# fmcboard_v1_7.net
KiCad netlist of a schematic drawn in EAGLE
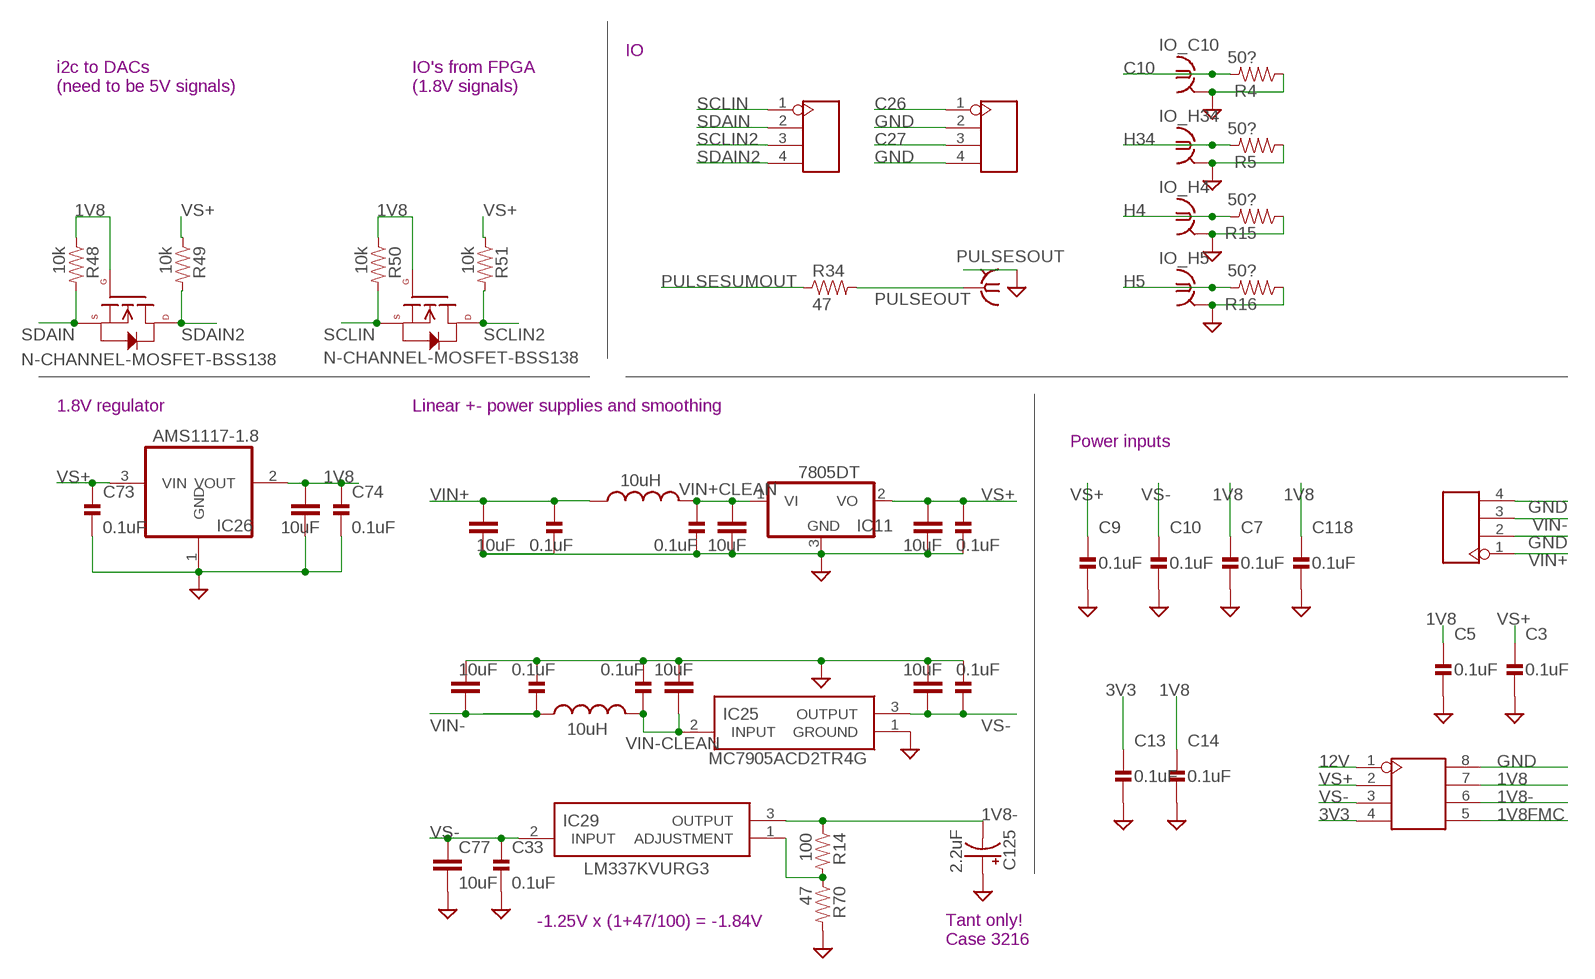
[diagram p0: schematic, sheet 1]
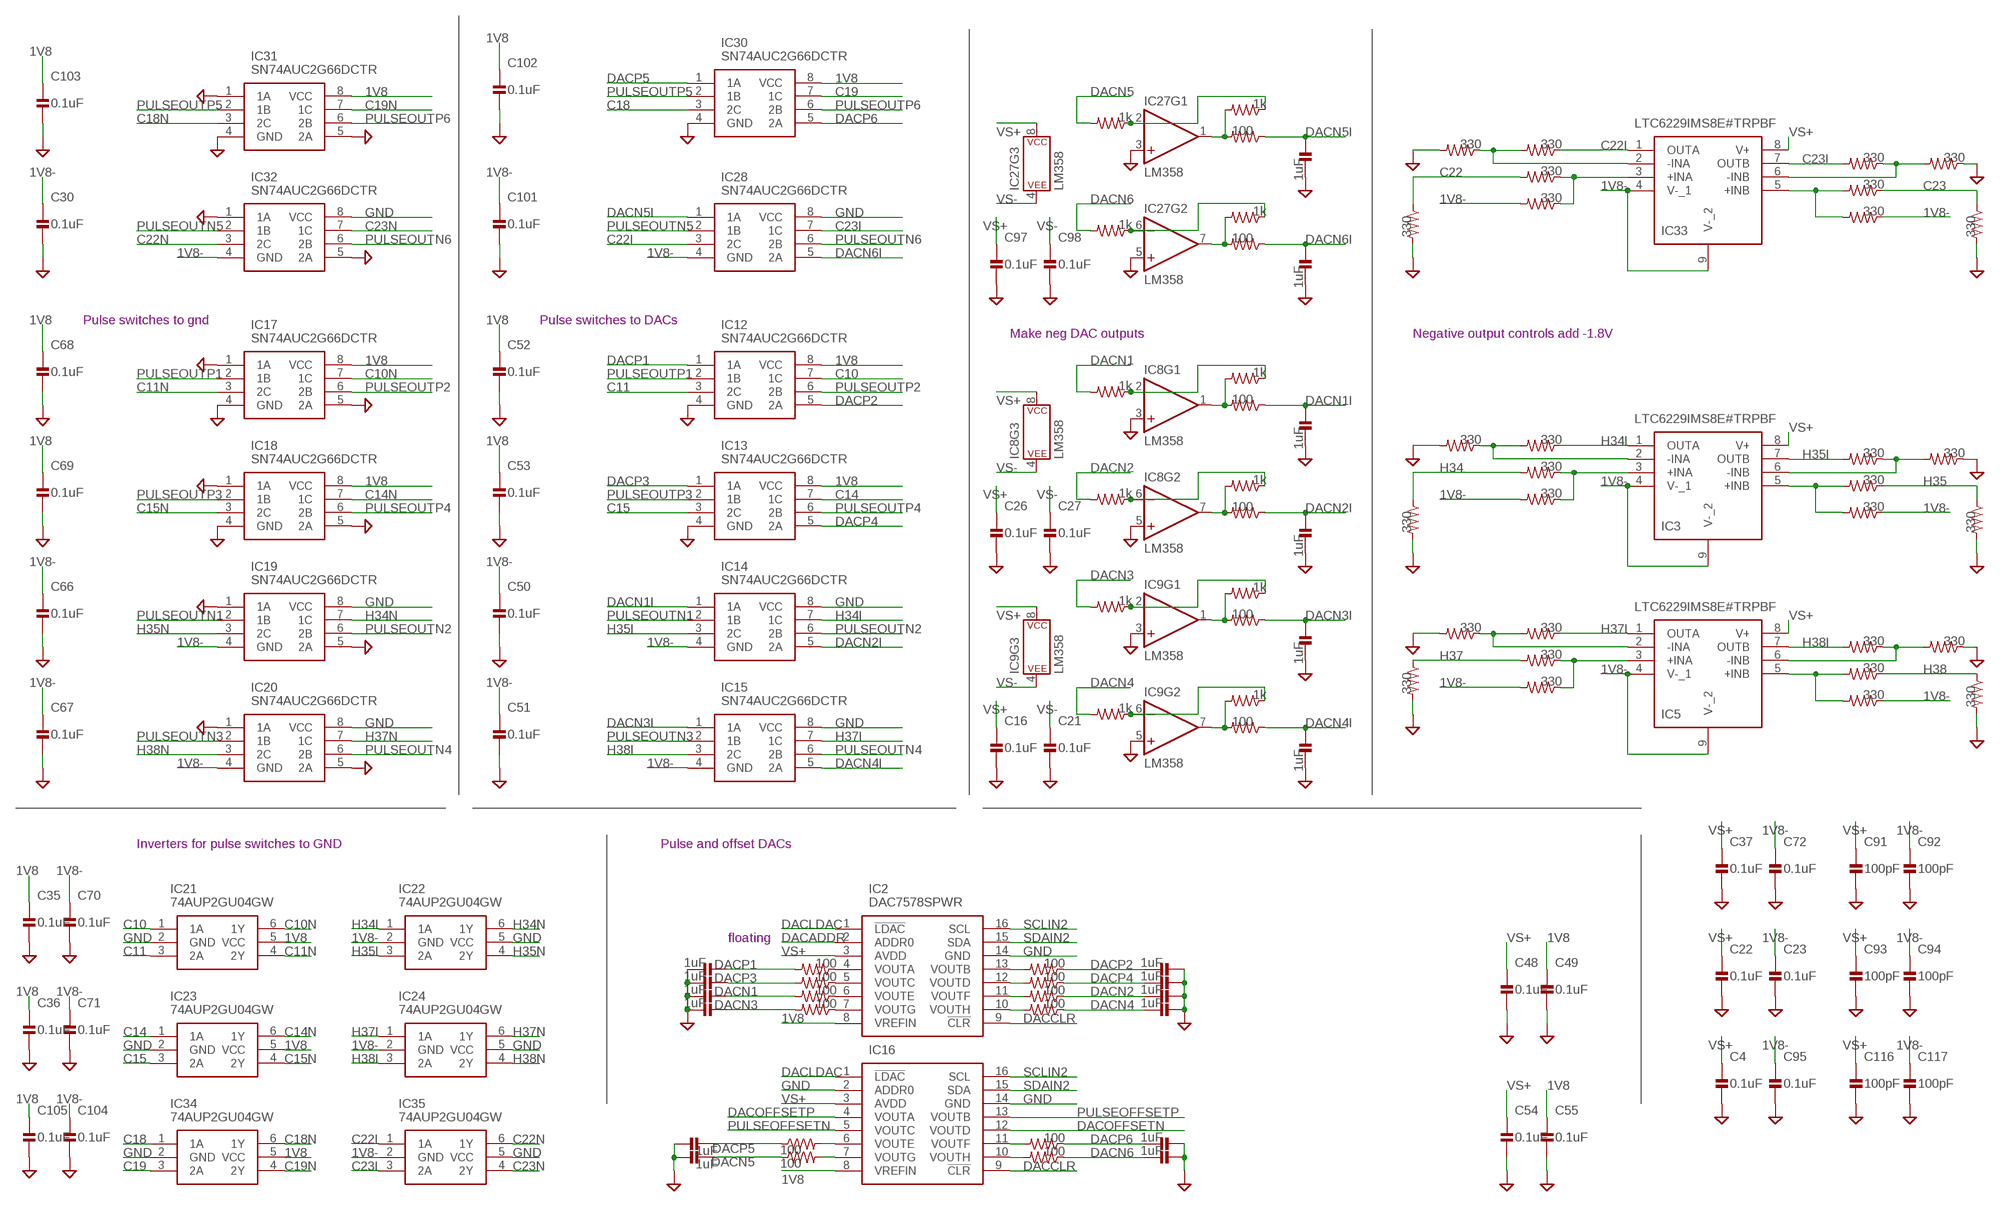
[diagram p1: schematic, sheet 2]
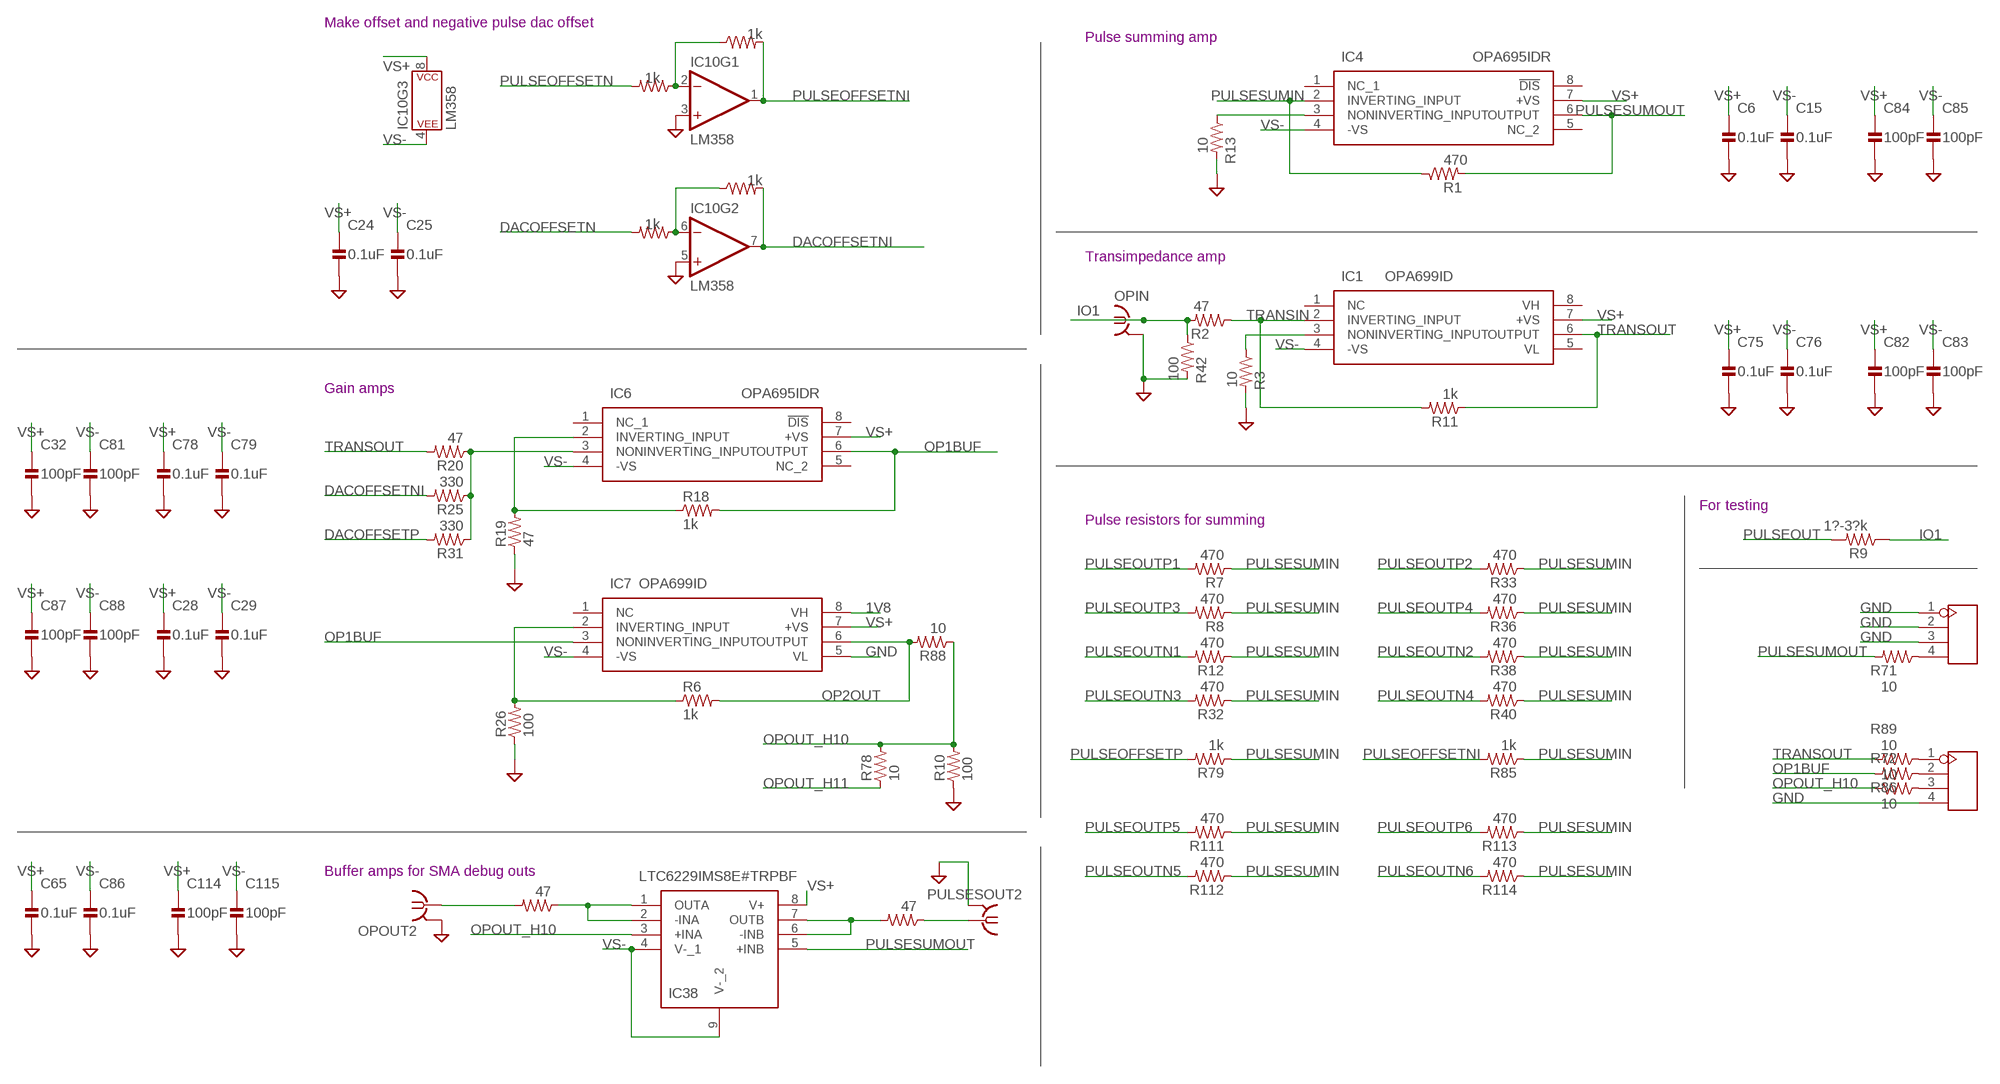
[diagram p2: schematic, sheet 3]
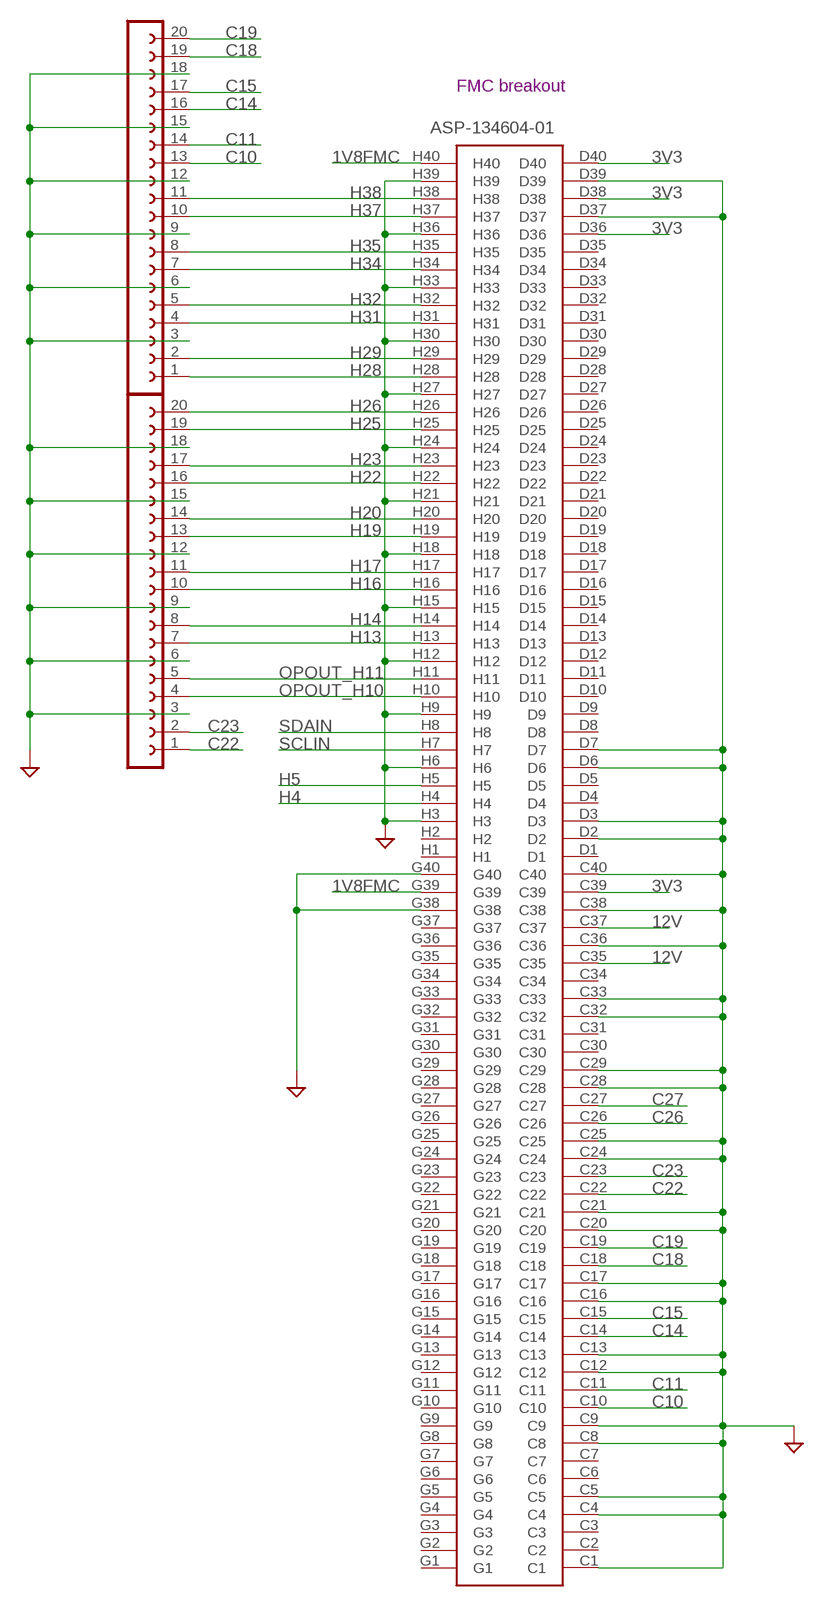
[diagram p3: schematic, sheet 4]
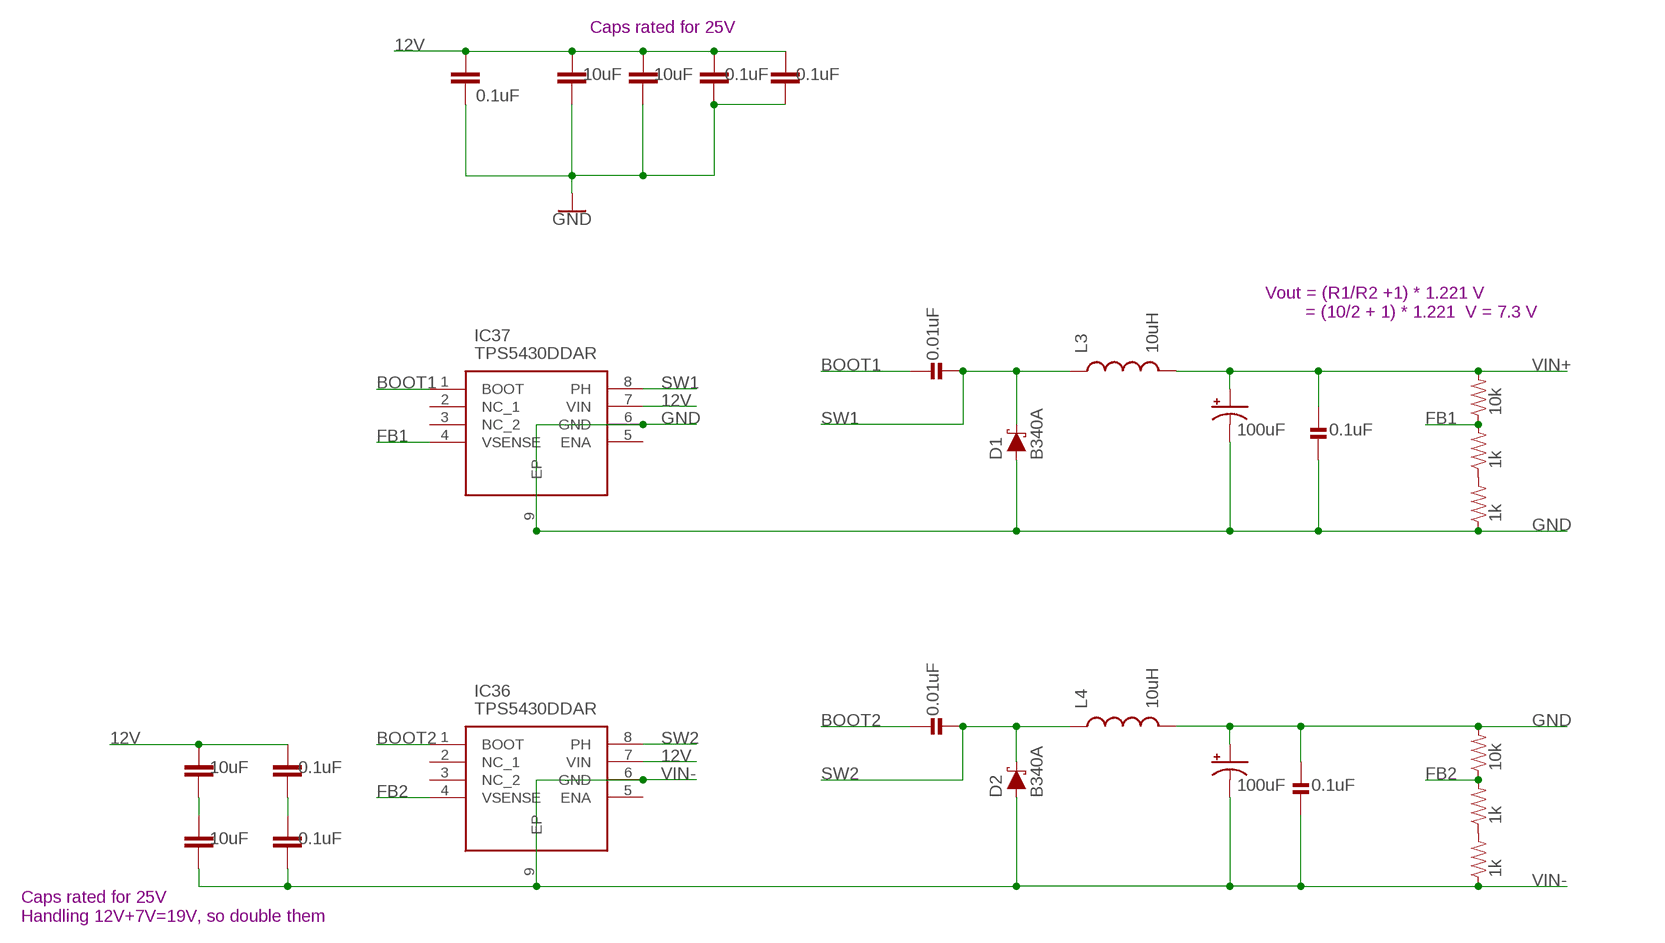
[diagram p4: schematic, sheet 5]

(export (version "E")
  (design (tool "Eeschema 10.0.6"))
  (components
    (comp (ref "J2")
      (value "ASP-134604-01")
      (footprint "eagle-import:ASP13460401")
      (fields (field (name "MOUSER_PART_NUMBER") "200-ASP-134604-01"))
      (libsource (lib "eagle-import") (part "ASP-134604-01"))
    )
    (comp (ref "SV1")
      (value "20")
      (footprint "eagle-import:FE20")
      (libsource (lib "eagle-import") (part "FE20-1"))
    )
    (comp (ref "SV2")
      (value "20")
      (footprint "eagle-import:FE20")
      (libsource (lib "eagle-import") (part "FE20-1"))
    )
    (comp (ref "C6")
      (value "0.1uF")
      (footprint "eagle-import:0402_CAP")
      (libsource (lib "eagle-import") (part "CAPACITOR0402_CAP"))
    )
    (comp (ref "C15")
      (value "0.1uF")
      (footprint "eagle-import:0402_CAP")
      (libsource (lib "eagle-import") (part "CAPACITOR0402_CAP"))
    )
    (comp (ref "C24")
      (value "0.1uF")
      (footprint "eagle-import:0402_CAP")
      (libsource (lib "eagle-import") (part "CAPACITOR0402_CAP"))
    )
    (comp (ref "C25")
      (value "0.1uF")
      (footprint "eagle-import:0402_CAP")
      (libsource (lib "eagle-import") (part "CAPACITOR0402_CAP"))
    )
    (comp (ref "C28")
      (value "0.1uF")
      (footprint "eagle-import:0402_CAP")
      (libsource (lib "eagle-import") (part "CAPACITOR0402_CAP"))
    )
    (comp (ref "C29")
      (value "0.1uF")
      (footprint "eagle-import:0402_CAP")
      (libsource (lib "eagle-import") (part "CAPACITOR0402_CAP"))
    )
    (comp (ref "C32")
      (value "100pF")
      (footprint "eagle-import:0402_CAP")
      (libsource (lib "eagle-import") (part "CAPACITOR0402_CAP"))
    )
    (comp (ref "C65")
      (value "0.1uF")
      (footprint "eagle-import:0402_CAP")
      (libsource (lib "eagle-import") (part "CAPACITOR0402_CAP"))
    )
    (comp (ref "C75")
      (value "0.1uF")
      (footprint "eagle-import:0402_CAP")
      (libsource (lib "eagle-import") (part "CAPACITOR0402_CAP"))
    )
    (comp (ref "C76")
      (value "0.1uF")
      (footprint "eagle-import:0402_CAP")
      (libsource (lib "eagle-import") (part "CAPACITOR0402_CAP"))
    )
    (comp (ref "C78")
      (value "0.1uF")
      (footprint "eagle-import:0402_CAP")
      (libsource (lib "eagle-import") (part "CAPACITOR0402_CAP"))
    )
    (comp (ref "C79")
      (value "0.1uF")
      (footprint "eagle-import:0402_CAP")
      (libsource (lib "eagle-import") (part "CAPACITOR0402_CAP"))
    )
    (comp (ref "C81")
      (value "100pF")
      (footprint "eagle-import:0402_CAP")
      (libsource (lib "eagle-import") (part "CAPACITOR0402_CAP"))
    )
    (comp (ref "C82")
      (value "100pF")
      (footprint "eagle-import:0402_CAP")
      (libsource (lib "eagle-import") (part "CAPACITOR0402_CAP"))
    )
    (comp (ref "C83")
      (value "100pF")
      (footprint "eagle-import:0402_CAP")
      (libsource (lib "eagle-import") (part "CAPACITOR0402_CAP"))
    )
    (comp (ref "C84")
      (value "100pF")
      (footprint "eagle-import:0402_CAP")
      (libsource (lib "eagle-import") (part "CAPACITOR0402_CAP"))
    )
    (comp (ref "C85")
      (value "100pF")
      (footprint "eagle-import:0402_CAP")
      (libsource (lib "eagle-import") (part "CAPACITOR0402_CAP"))
    )
    (comp (ref "C86")
      (value "0.1uF")
      (footprint "eagle-import:0402_CAP")
      (libsource (lib "eagle-import") (part "CAPACITOR0402_CAP"))
    )
    (comp (ref "C87")
      (value "100pF")
      (footprint "eagle-import:0402_CAP")
      (libsource (lib "eagle-import") (part "CAPACITOR0402_CAP"))
    )
    (comp (ref "C88")
      (value "100pF")
      (footprint "eagle-import:0402_CAP")
      (libsource (lib "eagle-import") (part "CAPACITOR0402_CAP"))
    )
    (comp (ref "C114")
      (value "100pF")
      (footprint "eagle-import:0402_CAP")
      (libsource (lib "eagle-import") (part "CAPACITOR0402_CAP"))
    )
    (comp (ref "C115")
      (value "100pF")
      (footprint "eagle-import:0402_CAP")
      (libsource (lib "eagle-import") (part "CAPACITOR0402_CAP"))
    )
    (comp (ref "IC1")
      (value "OPA699ID")
      (footprint "eagle-import:SOIC127P600X175-8N")
      (fields (field (name "MOUSER_PART_NUMBER") "595-OPA699ID"))
      (libsource (lib "eagle-import") (part "OPA699ID"))
    )
    (comp (ref "IC4")
      (value "OPA695IDR")
      (footprint "eagle-import:SOIC127P600X175-8N")
      (fields (field (name "MOUSER_PART_NUMBER") "595-OPA695IDR"))
      (libsource (lib "eagle-import") (part "OPA695IDR"))
    )
    (comp (ref "IC6")
      (value "OPA695IDR")
      (footprint "eagle-import:SOIC127P600X175-8N")
      (fields (field (name "MOUSER_PART_NUMBER") "595-OPA695IDR"))
      (libsource (lib "eagle-import") (part "OPA695IDR"))
    )
    (comp (ref "IC7")
      (value "OPA699ID")
      (footprint "eagle-import:SOIC127P600X175-8N")
      (fields (field (name "MOUSER_PART_NUMBER") "595-OPA699ID"))
      (libsource (lib "eagle-import") (part "OPA699ID"))
    )
    (comp (ref "IC10")
      (value "LM358")
      (footprint "eagle-import:SO08")
      (libsource (lib "eagle-import") (part "OPAMP-DUALU"))
    )
    (comp (ref "IC38")
      (value "LTC6229IMS8E#TRPBF")
      (footprint "eagle-import:SOP65P490X110-9N")
      (fields (field (name "MOUSER_PART_NUMBER") "584-LTC6229IMS8E#TR"))
      (libsource (lib "eagle-import") (part "LTC6229IMS8E#TRPBF"))
    )
    (comp (ref "J5")
      (value "4p-2.54")
      (footprint "eagle-import:H4-2.54")
      (fields (field (name "MPN") "F185-1104A1BSYA1"))
      (libsource (lib "eagle-import") (part "DIP-BLACK-FEMALE-HEADER-VERT(4P-2.54)"))
    )
    (comp (ref "J13")
      (value "4p-2.54")
      (footprint "eagle-import:H4-2.54")
      (fields (field (name "MPN") "F185-1104A1BSYA1"))
      (libsource (lib "eagle-import") (part "DIP-BLACK-FEMALE-HEADER-VERT(4P-2.54)"))
    )
    (comp (ref "OPIN")
      (value "BU-SMB-V")
      (footprint "eagle-import:BU-SMB-V")
      (libsource (lib "eagle-import") (part "BU-SMB-V"))
    )
    (comp (ref "OPOUT2")
      (value "BU-SMB-V")
      (footprint "eagle-import:BU-SMB-V")
      (libsource (lib "eagle-import") (part "BU-SMB-V"))
    )
    (comp (ref "PULSESOUT2")
      (value "BU-SMB-V")
      (footprint "eagle-import:BU-SMB-V")
      (libsource (lib "eagle-import") (part "BU-SMB-V"))
    )
    (comp (ref "R1")
      (value "470")
      (footprint "eagle-import:0402_RES")
      (libsource (lib "eagle-import") (part "RESISTOR0402_RES"))
    )
    (comp (ref "R2")
      (value "47")
      (footprint "eagle-import:0402_RES")
      (libsource (lib "eagle-import") (part "RESISTOR0402_RES"))
    )
    (comp (ref "R3")
      (value "10")
      (footprint "eagle-import:0402_RES")
      (libsource (lib "eagle-import") (part "RESISTOR0402_RES"))
    )
    (comp (ref "R6")
      (value "1k")
      (footprint "eagle-import:0402_RES")
      (libsource (lib "eagle-import") (part "RESISTOR0402_RES"))
    )
    (comp (ref "R7")
      (value "470")
      (footprint "eagle-import:0402_RES")
      (libsource (lib "eagle-import") (part "RESISTOR0402_RES"))
    )
    (comp (ref "R8")
      (value "470")
      (footprint "eagle-import:0402_RES")
      (libsource (lib "eagle-import") (part "RESISTOR0402_RES"))
    )
    (comp (ref "R9")
      (value "1?-3?k")
      (footprint "eagle-import:R0805")
      (libsource (lib "eagle-import") (part "R-US_R0805"))
    )
    (comp (ref "R10")
      (value "100")
      (footprint "eagle-import:0402_RES")
      (libsource (lib "eagle-import") (part "RESISTOR0402_RES"))
    )
    (comp (ref "R11")
      (value "1k")
      (footprint "eagle-import:0402_RES")
      (libsource (lib "eagle-import") (part "RESISTOR0402_RES"))
    )
    (comp (ref "R12")
      (value "470")
      (footprint "eagle-import:0402_RES")
      (libsource (lib "eagle-import") (part "RESISTOR0402_RES"))
    )
    (comp (ref "R13")
      (value "10")
      (footprint "eagle-import:0402_RES")
      (libsource (lib "eagle-import") (part "RESISTOR0402_RES"))
    )
    (comp (ref "R17")
      (value "1k")
      (footprint "eagle-import:0402_RES")
      (libsource (lib "eagle-import") (part "RESISTOR0402_RES"))
    )
    (comp (ref "R18")
      (value "1k")
      (footprint "eagle-import:0402_RES")
      (libsource (lib "eagle-import") (part "RESISTOR0402_RES"))
    )
    (comp (ref "R19")
      (value "47")
      (footprint "eagle-import:0402_RES")
      (libsource (lib "eagle-import") (part "RESISTOR0402_RES"))
    )
    (comp (ref "R20")
      (value "47")
      (footprint "eagle-import:0402_RES")
      (libsource (lib "eagle-import") (part "RESISTOR0402_RES"))
    )
    (comp (ref "R25")
      (value "330")
      (footprint "eagle-import:0402_RES")
      (libsource (lib "eagle-import") (part "RESISTOR0402_RES"))
    )
    (comp (ref "R26")
      (value "100")
      (footprint "eagle-import:0402_RES")
      (libsource (lib "eagle-import") (part "RESISTOR0402_RES"))
    )
    (comp (ref "R31")
      (value "330")
      (footprint "eagle-import:0402_RES")
      (libsource (lib "eagle-import") (part "RESISTOR0402_RES"))
    )
    (comp (ref "R32")
      (value "470")
      (footprint "eagle-import:0402_RES")
      (libsource (lib "eagle-import") (part "RESISTOR0402_RES"))
    )
    (comp (ref "R33")
      (value "470")
      (footprint "eagle-import:0402_RES")
      (libsource (lib "eagle-import") (part "RESISTOR0402_RES"))
    )
    (comp (ref "R35")
      (value "1k")
      (footprint "eagle-import:0402_RES")
      (libsource (lib "eagle-import") (part "RESISTOR0402_RES"))
    )
    (comp (ref "R36")
      (value "470")
      (footprint "eagle-import:0402_RES")
      (libsource (lib "eagle-import") (part "RESISTOR0402_RES"))
    )
    (comp (ref "R38")
      (value "470")
      (footprint "eagle-import:0402_RES")
      (libsource (lib "eagle-import") (part "RESISTOR0402_RES"))
    )
    (comp (ref "R40")
      (value "470")
      (footprint "eagle-import:0402_RES")
      (libsource (lib "eagle-import") (part "RESISTOR0402_RES"))
    )
    (comp (ref "R42")
      (value "100")
      (footprint "eagle-import:0402_RES")
      (libsource (lib "eagle-import") (part "RESISTOR0402_RES"))
    )
    (comp (ref "R61")
      (value "1k")
      (footprint "eagle-import:0402_RES")
      (libsource (lib "eagle-import") (part "RESISTOR0402_RES"))
    )
    (comp (ref "R71")
      (value "10")
      (footprint "eagle-import:0402_RES")
      (libsource (lib "eagle-import") (part "RESISTOR0402_RES"))
    )
    (comp (ref "R72")
      (value "10")
      (footprint "eagle-import:0402_RES")
      (libsource (lib "eagle-import") (part "RESISTOR0402_RES"))
    )
    (comp (ref "R78")
      (value "10")
      (footprint "eagle-import:0402_RES")
      (libsource (lib "eagle-import") (part "RESISTOR0402_RES"))
    )
    (comp (ref "R79")
      (value "1k")
      (footprint "eagle-import:0402_RES")
      (libsource (lib "eagle-import") (part "RESISTOR0402_RES"))
    )
    (comp (ref "R85")
      (value "1k")
      (footprint "eagle-import:0402_RES")
      (libsource (lib "eagle-import") (part "RESISTOR0402_RES"))
    )
    (comp (ref "R86")
      (value "10")
      (footprint "eagle-import:0402_RES")
      (libsource (lib "eagle-import") (part "RESISTOR0402_RES"))
    )
    (comp (ref "R88")
      (value "10")
      (footprint "eagle-import:0402_RES")
      (libsource (lib "eagle-import") (part "RESISTOR0402_RES"))
    )
    (comp (ref "R89")
      (value "10")
      (footprint "eagle-import:0402_RES")
      (libsource (lib "eagle-import") (part "RESISTOR0402_RES"))
    )
    (comp (ref "R111")
      (value "470")
      (footprint "eagle-import:0402_RES")
      (libsource (lib "eagle-import") (part "RESISTOR0402_RES"))
    )
    (comp (ref "R112")
      (value "470")
      (footprint "eagle-import:0402_RES")
      (libsource (lib "eagle-import") (part "RESISTOR0402_RES"))
    )
    (comp (ref "R113")
      (value "470")
      (footprint "eagle-import:0402_RES")
      (libsource (lib "eagle-import") (part "RESISTOR0402_RES"))
    )
    (comp (ref "R114")
      (value "470")
      (footprint "eagle-import:0402_RES")
      (libsource (lib "eagle-import") (part "RESISTOR0402_RES"))
    )
    (comp (ref "R115")
      (value "1k")
      (footprint "eagle-import:0402_RES")
      (libsource (lib "eagle-import") (part "RESISTOR0402_RES"))
    )
    (comp (ref "R119")
      (value "47")
      (footprint "eagle-import:0402_RES")
      (libsource (lib "eagle-import") (part "RESISTOR0402_RES"))
    )
    (comp (ref "R120")
      (value "47")
      (footprint "eagle-import:0402_RES")
      (libsource (lib "eagle-import") (part "RESISTOR0402_RES"))
    )
    (comp (ref "C2")
      (value "100uF")
      (footprint "eagle-import:VISHAY_C")
      (libsource (lib "eagle-import") (part "SparkFun-Passives_CAP_POLSMD"))
    )
    (comp (ref "C8")
      (value "0.1uF")
      (footprint "eagle-import:C0805K")
      (libsource (lib "eagle-import") (part "C-EUC0805K"))
    )
    (comp (ref "C11")
      (value "0.1uF")
      (footprint "eagle-import:C0805K")
      (libsource (lib "eagle-import") (part "C-EUC0805K"))
    )
    (comp (ref "C12")
      (value "0.1uF")
      (footprint "eagle-import:C0805K")
      (libsource (lib "eagle-import") (part "C-EUC0805K"))
    )
    (comp (ref "C40")
      (value "100uF")
      (footprint "eagle-import:VISHAY_C")
      (libsource (lib "eagle-import") (part "SparkFun-Passives_CAP_POLSMD"))
    )
    (comp (ref "C64")
      (value "10uF")
      (footprint "eagle-import:C0805")
      (libsource (lib "eagle-import") (part "C-EUC0805"))
    )
    (comp (ref "C80")
      (value "10uF")
      (footprint "eagle-import:C0805")
      (libsource (lib "eagle-import") (part "C-EUC0805"))
    )
    (comp (ref "C106")
      (value "0.1uF")
      (footprint "eagle-import:0402_CAP")
      (libsource (lib "eagle-import") (part "CAPACITOR0402_CAP"))
    )
    (comp (ref "C107")
      (value "0.01uF")
      (footprint "eagle-import:0402_CAP")
      (libsource (lib "eagle-import") (part "CAPACITOR0402_CAP"))
    )
    (comp (ref "C108")
      (value "0.1uF")
      (footprint "eagle-import:C0805K")
      (libsource (lib "eagle-import") (part "C-EUC0805K"))
    )
    (comp (ref "C109")
      (value "10uF")
      (footprint "eagle-import:C0805")
      (libsource (lib "eagle-import") (part "C-EUC0805"))
    )
    (comp (ref "C112")
      (value "10uF")
      (footprint "eagle-import:C0805")
      (libsource (lib "eagle-import") (part "C-EUC0805"))
    )
    (comp (ref "C113")
      (value "0.1uF")
      (footprint "eagle-import:C0805K")
      (libsource (lib "eagle-import") (part "C-EUC0805K"))
    )
    (comp (ref "C121")
      (value "0.1uF")
      (footprint "eagle-import:0402_CAP")
      (libsource (lib "eagle-import") (part "CAPACITOR0402_CAP"))
    )
    (comp (ref "C122")
      (value "0.01uF")
      (footprint "eagle-import:0402_CAP")
      (libsource (lib "eagle-import") (part "CAPACITOR0402_CAP"))
    )
    (comp (ref "D1")
      (value "B340A")
      (footprint "eagle-import:SMA-DIODE")
      (libsource (lib "eagle-import") (part "DIODE-SCHOTTKY-B340A"))
    )
    (comp (ref "D2")
      (value "B340A")
      (footprint "eagle-import:SMA-DIODE")
      (libsource (lib "eagle-import") (part "DIODE-SCHOTTKY-B340A"))
    )
    (comp (ref "IC36")
      (value "TPS5430DDAR")
      (footprint "eagle-import:SOIC127P600X170-9N")
      (fields (field (name "MOUSER_PART_NUMBER") "595-TPS5430DDAR"))
      (libsource (lib "eagle-import") (part "TPS5430DDAR"))
    )
    (comp (ref "IC37")
      (value "TPS5430DDAR")
      (footprint "eagle-import:SOIC127P600X170-9N")
      (fields (field (name "MOUSER_PART_NUMBER") "595-TPS5430DDAR"))
      (libsource (lib "eagle-import") (part "TPS5430DDAR"))
    )
    (comp (ref "L3")
      (value "10uH")
      (footprint "eagle-import:CDRH125")
      (libsource (lib "eagle-import") (part "INDUCTORPWR"))
    )
    (comp (ref "L4")
      (value "10uH")
      (footprint "eagle-import:CDRH125")
      (libsource (lib "eagle-import") (part "INDUCTORPWR"))
    )
    (comp (ref "R60")
      (value "1k")
      (footprint "eagle-import:0402_RES")
      (libsource (lib "eagle-import") (part "RESISTOR0402_RES"))
    )
    (comp (ref "R73")
      (value "10k")
      (footprint "eagle-import:0402_RES")
      (libsource (lib "eagle-import") (part "RESISTOR0402_RES"))
    )
    (comp (ref "R84")
      (value "1k")
      (footprint "eagle-import:0402_RES")
      (libsource (lib "eagle-import") (part "RESISTOR0402_RES"))
    )
    (comp (ref "R116")
      (value "1k")
      (footprint "eagle-import:0402_RES")
      (libsource (lib "eagle-import") (part "RESISTOR0402_RES"))
    )
    (comp (ref "R117")
      (value "1k")
      (footprint "eagle-import:0402_RES")
      (libsource (lib "eagle-import") (part "RESISTOR0402_RES"))
    )
    (comp (ref "R118")
      (value "10k")
      (footprint "eagle-import:0402_RES")
      (libsource (lib "eagle-import") (part "RESISTOR0402_RES"))
    )
    (comp (ref "C1")
      (value "10uF")
      (footprint "eagle-import:C0805")
      (libsource (lib "eagle-import") (part "C-EUC0805"))
    )
    (comp (ref "C3")
      (value "0.1uF")
      (footprint "eagle-import:0402_CAP")
      (libsource (lib "eagle-import") (part "CAPACITOR0402_CAP"))
    )
    (comp (ref "C5")
      (value "0.1uF")
      (footprint "eagle-import:0402_CAP")
      (libsource (lib "eagle-import") (part "CAPACITOR0402_CAP"))
    )
    (comp (ref "C7")
      (value "0.1uF")
      (footprint "eagle-import:0402_CAP")
      (libsource (lib "eagle-import") (part "CAPACITOR0402_CAP"))
    )
    (comp (ref "C9")
      (value "0.1uF")
      (footprint "eagle-import:0402_CAP")
      (libsource (lib "eagle-import") (part "CAPACITOR0402_CAP"))
    )
    (comp (ref "C10")
      (value "0.1uF")
      (footprint "eagle-import:0402_CAP")
      (libsource (lib "eagle-import") (part "CAPACITOR0402_CAP"))
    )
    (comp (ref "C13")
      (value "0.1uF")
      (footprint "eagle-import:0402_CAP")
      (libsource (lib "eagle-import") (part "CAPACITOR0402_CAP"))
    )
    (comp (ref "C14")
      (value "0.1uF")
      (footprint "eagle-import:0402_CAP")
      (libsource (lib "eagle-import") (part "CAPACITOR0402_CAP"))
    )
    (comp (ref "C33")
      (value "0.1uF")
      (footprint "eagle-import:0402_CAP")
      (libsource (lib "eagle-import") (part "CAPACITOR0402_CAP"))
    )
    (comp (ref "C34")
      (value "10uF")
      (footprint "eagle-import:C0805")
      (libsource (lib "eagle-import") (part "C-EUC0805"))
    )
    (comp (ref "C38")
      (value "10uF")
      (footprint "eagle-import:C0805")
      (libsource (lib "eagle-import") (part "C-EUC0805"))
    )
    (comp (ref "C39")
      (value "10uF")
      (footprint "eagle-import:C0805")
      (libsource (lib "eagle-import") (part "C-EUC0805"))
    )
    (comp (ref "C41")
      (value "10uF")
      (footprint "eagle-import:C0805")
      (libsource (lib "eagle-import") (part "C-EUC0805"))
    )
    (comp (ref "C42")
      (value "0.1uF")
      (footprint "eagle-import:0402_CAP")
      (libsource (lib "eagle-import") (part "CAPACITOR0402_CAP"))
    )
    (comp (ref "C43")
      (value "0.1uF")
      (footprint "eagle-import:0402_CAP")
      (libsource (lib "eagle-import") (part "CAPACITOR0402_CAP"))
    )
    (comp (ref "C44")
      (value "0.1uF")
      (footprint "eagle-import:0402_CAP")
      (libsource (lib "eagle-import") (part "CAPACITOR0402_CAP"))
    )
    (comp (ref "C45")
      (value "0.1uF")
      (footprint "eagle-import:0402_CAP")
      (libsource (lib "eagle-import") (part "CAPACITOR0402_CAP"))
    )
    (comp (ref "C46")
      (value "0.1uF")
      (footprint "eagle-import:0402_CAP")
      (libsource (lib "eagle-import") (part "CAPACITOR0402_CAP"))
    )
    (comp (ref "C47")
      (value "0.1uF")
      (footprint "eagle-import:0402_CAP")
      (libsource (lib "eagle-import") (part "CAPACITOR0402_CAP"))
    )
    (comp (ref "C73")
      (value "0.1uF")
      (footprint "eagle-import:0402_CAP")
      (libsource (lib "eagle-import") (part "CAPACITOR0402_CAP"))
    )
    (comp (ref "C74")
      (value "0.1uF")
      (footprint "eagle-import:0402_CAP")
      (libsource (lib "eagle-import") (part "CAPACITOR0402_CAP"))
    )
    (comp (ref "C77")
      (value "10uF")
      (footprint "eagle-import:C0805")
      (libsource (lib "eagle-import") (part "C-EUC0805"))
    )
    (comp (ref "C110")
      (value "10uF")
      (footprint "eagle-import:C0805")
      (libsource (lib "eagle-import") (part "C-EUC0805"))
    )
    (comp (ref "C111")
      (value "10uF")
      (footprint "eagle-import:C0805")
      (libsource (lib "eagle-import") (part "C-EUC0805"))
    )
    (comp (ref "C118")
      (value "0.1uF")
      (footprint "eagle-import:0402_CAP")
      (libsource (lib "eagle-import") (part "CAPACITOR0402_CAP"))
    )
    (comp (ref "C125")
      (value "2.2uF")
      (footprint "eagle-import:EIA3216")
      (libsource (lib "eagle-import") (part "CAP_POL1206"))
    )
    (comp (ref "IC11")
      (value "7805DT")
      (footprint "eagle-import:TO252")
      (libsource (lib "eagle-import") (part "78DT05"))
    )
    (comp (ref "IC25")
      (value "MC7905ACD2TR4G")
      (footprint "eagle-import:MC7905ACD2TR4G")
      (fields (field (name "MOUSER_PART_NUMBER") "863-MC7905ACD2TR4G"))
      (libsource (lib "eagle-import") (part "MC7905ACD2TR4G"))
    )
    (comp (ref "IC26")
      (value "AMS1117-1.8")
      (footprint "eagle-import:SOT223")
      (fields (field (name "MPN") "REG1117"))
      (libsource (lib "eagle-import") (part "REG1117"))
    )
    (comp (ref "IC29")
      (value "LM337KVURG3")
      (footprint "eagle-import:LM337KVURG3")
      (fields (field (name "MOUSER_PART_NUMBER") "595-LM337KVURG3"))
      (libsource (lib "eagle-import") (part "LM337KVURG3"))
    )
    (comp (ref "IO_C10")
      (value "BU-SMB-V")
      (footprint "eagle-import:BU-SMB-V")
      (libsource (lib "eagle-import") (part "BU-SMB-V"))
    )
    (comp (ref "IO_H4")
      (value "BU-SMB-V")
      (footprint "eagle-import:BU-SMB-V")
      (libsource (lib "eagle-import") (part "BU-SMB-V"))
    )
    (comp (ref "IO_H5")
      (value "BU-SMB-V")
      (footprint "eagle-import:BU-SMB-V")
      (libsource (lib "eagle-import") (part "BU-SMB-V"))
    )
    (comp (ref "IO_H34")
      (value "BU-SMB-V")
      (footprint "eagle-import:BU-SMB-V")
      (libsource (lib "eagle-import") (part "BU-SMB-V"))
    )
    (comp (ref "J1")
      (value "4p-2.54")
      (footprint "eagle-import:H4-2.54")
      (fields (field (name "MPN") "F185-1104A1BSYA1"))
      (libsource (lib "eagle-import") (part "DIP-BLACK-FEMALE-HEADER-VERT(4P-2.54)"))
    )
    (comp (ref "J3")
      (value "2X4P-2.54")
      (footprint "eagle-import:H2X4-2.54")
      (libsource (lib "eagle-import") (part "DIP-BLACK-FEMALE-HEADER(2X4P-2.54)"))
    )
    (comp (ref "J4")
      (value "4p-2.54")
      (footprint "eagle-import:H4-2.54")
      (fields (field (name "MPN") "F185-1104A1BSYA1"))
      (libsource (lib "eagle-import") (part "DIP-BLACK-FEMALE-HEADER-VERT(4P-2.54)"))
    )
    (comp (ref "J6")
      (value "4p-2.54")
      (footprint "eagle-import:H4-2.54")
      (fields (field (name "MPN") "F185-1104A1BSYA1"))
      (libsource (lib "eagle-import") (part "DIP-BLACK-FEMALE-HEADER-VERT(4P-2.54)"))
    )
    (comp (ref "L1")
      (value "10uH")
      (footprint "eagle-import:1210")
      (libsource (lib "eagle-import") (part "INDUCTOR1210"))
    )
    (comp (ref "L2")
      (value "10uH")
      (footprint "eagle-import:1210")
      (libsource (lib "eagle-import") (part "INDUCTOR1210"))
    )
    (comp (ref "PULSESOUT")
      (value "BU-SMB-V")
      (footprint "eagle-import:BU-SMB-V")
      (libsource (lib "eagle-import") (part "BU-SMB-V"))
    )
    (comp (ref "R4")
      (value "50?")
      (footprint "eagle-import:0402_RES")
      (libsource (lib "eagle-import") (part "RESISTOR0402_RES"))
    )
    (comp (ref "R5")
      (value "50?")
      (footprint "eagle-import:0402_RES")
      (libsource (lib "eagle-import") (part "RESISTOR0402_RES"))
    )
    (comp (ref "R14")
      (value "100")
      (footprint "eagle-import:0402_RES")
      (libsource (lib "eagle-import") (part "RESISTOR0402_RES"))
    )
    (comp (ref "R15")
      (value "50?")
      (footprint "eagle-import:0402_RES")
      (libsource (lib "eagle-import") (part "RESISTOR0402_RES"))
    )
    (comp (ref "R16")
      (value "50?")
      (footprint "eagle-import:0402_RES")
      (libsource (lib "eagle-import") (part "RESISTOR0402_RES"))
    )
    (comp (ref "R34")
      (value "47")
      (footprint "eagle-import:0402_RES")
      (libsource (lib "eagle-import") (part "RESISTOR0402_RES"))
    )
    (comp (ref "R48")
      (value "10k")
      (footprint "eagle-import:0402_RES")
      (libsource (lib "eagle-import") (part "RESISTOR0402_RES"))
    )
    (comp (ref "R49")
      (value "10k")
      (footprint "eagle-import:0402_RES")
      (libsource (lib "eagle-import") (part "RESISTOR0402_RES"))
    )
    (comp (ref "R50")
      (value "10k")
      (footprint "eagle-import:0402_RES")
      (libsource (lib "eagle-import") (part "RESISTOR0402_RES"))
    )
    (comp (ref "R51")
      (value "10k")
      (footprint "eagle-import:0402_RES")
      (libsource (lib "eagle-import") (part "RESISTOR0402_RES"))
    )
    (comp (ref "R70")
      (value "47")
      (footprint "eagle-import:0402_RES")
      (libsource (lib "eagle-import") (part "RESISTOR0402_RES"))
    )
    (comp (ref "U$1")
      (value "N-CHANNEL-MOSFET-BSS138")
      (footprint "eagle-import:SOT23-3")
      (libsource (lib "eagle-import") (part "N-CHANNEL-MOSFET-BSS138"))
    )
    (comp (ref "U$2")
      (value "N-CHANNEL-MOSFET-BSS138")
      (footprint "eagle-import:SOT23-3")
      (libsource (lib "eagle-import") (part "N-CHANNEL-MOSFET-BSS138"))
    )
    (comp (ref "C4")
      (value "0.1uF")
      (footprint "eagle-import:0402_CAP")
      (libsource (lib "eagle-import") (part "CAPACITOR0402_CAP"))
    )
    (comp (ref "C16")
      (value "0.1uF")
      (footprint "eagle-import:0402_CAP")
      (libsource (lib "eagle-import") (part "CAPACITOR0402_CAP"))
    )
    (comp (ref "C17")
      (value "1uF")
      (footprint "eagle-import:0402_CAP")
      (libsource (lib "eagle-import") (part "CAPACITOR0402_CAP"))
    )
    (comp (ref "C18")
      (value "1uF")
      (footprint "eagle-import:0402_CAP")
      (libsource (lib "eagle-import") (part "CAPACITOR0402_CAP"))
    )
    (comp (ref "C19")
      (value "1uF")
      (footprint "eagle-import:0402_CAP")
      (libsource (lib "eagle-import") (part "CAPACITOR0402_CAP"))
    )
    (comp (ref "C20")
      (value "1uF")
      (footprint "eagle-import:0402_CAP")
      (libsource (lib "eagle-import") (part "CAPACITOR0402_CAP"))
    )
    (comp (ref "C21")
      (value "0.1uF")
      (footprint "eagle-import:0402_CAP")
      (libsource (lib "eagle-import") (part "CAPACITOR0402_CAP"))
    )
    (comp (ref "C22")
      (value "0.1uF")
      (footprint "eagle-import:0402_CAP")
      (libsource (lib "eagle-import") (part "CAPACITOR0402_CAP"))
    )
    (comp (ref "C23")
      (value "0.1uF")
      (footprint "eagle-import:0402_CAP")
      (libsource (lib "eagle-import") (part "CAPACITOR0402_CAP"))
    )
    (comp (ref "C26")
      (value "0.1uF")
      (footprint "eagle-import:0402_CAP")
      (libsource (lib "eagle-import") (part "CAPACITOR0402_CAP"))
    )
    (comp (ref "C27")
      (value "0.1uF")
      (footprint "eagle-import:0402_CAP")
      (libsource (lib "eagle-import") (part "CAPACITOR0402_CAP"))
    )
    (comp (ref "C30")
      (value "0.1uF")
      (footprint "eagle-import:0402_CAP")
      (libsource (lib "eagle-import") (part "CAPACITOR0402_CAP"))
    )
    (comp (ref "C31")
      (value "1uF")
      (footprint "eagle-import:0402_CAP")
      (libsource (lib "eagle-import") (part "CAPACITOR0402_CAP"))
    )
    (comp (ref "C35")
      (value "0.1uF")
      (footprint "eagle-import:0402_CAP")
      (libsource (lib "eagle-import") (part "CAPACITOR0402_CAP"))
    )
    (comp (ref "C36")
      (value "0.1uF")
      (footprint "eagle-import:0402_CAP")
      (libsource (lib "eagle-import") (part "CAPACITOR0402_CAP"))
    )
    (comp (ref "C37")
      (value "0.1uF")
      (footprint "eagle-import:0402_CAP")
      (libsource (lib "eagle-import") (part "CAPACITOR0402_CAP"))
    )
    (comp (ref "C48")
      (value "0.1uF")
      (footprint "eagle-import:0402_CAP")
      (libsource (lib "eagle-import") (part "CAPACITOR0402_CAP"))
    )
    (comp (ref "C49")
      (value "0.1uF")
      (footprint "eagle-import:0402_CAP")
      (libsource (lib "eagle-import") (part "CAPACITOR0402_CAP"))
    )
    (comp (ref "C50")
      (value "0.1uF")
      (footprint "eagle-import:0402_CAP")
      (libsource (lib "eagle-import") (part "CAPACITOR0402_CAP"))
    )
    (comp (ref "C51")
      (value "0.1uF")
      (footprint "eagle-import:0402_CAP")
      (libsource (lib "eagle-import") (part "CAPACITOR0402_CAP"))
    )
    (comp (ref "C52")
      (value "0.1uF")
      (footprint "eagle-import:0402_CAP")
      (libsource (lib "eagle-import") (part "CAPACITOR0402_CAP"))
    )
    (comp (ref "C53")
      (value "0.1uF")
      (footprint "eagle-import:0402_CAP")
      (libsource (lib "eagle-import") (part "CAPACITOR0402_CAP"))
    )
    (comp (ref "C54")
      (value "0.1uF")
      (footprint "eagle-import:0402_CAP")
      (libsource (lib "eagle-import") (part "CAPACITOR0402_CAP"))
    )
    (comp (ref "C55")
      (value "0.1uF")
      (footprint "eagle-import:0402_CAP")
      (libsource (lib "eagle-import") (part "CAPACITOR0402_CAP"))
    )
    (comp (ref "C56")
      (value "1uF")
      (footprint "eagle-import:0402_CAP")
      (libsource (lib "eagle-import") (part "CAPACITOR0402_CAP"))
    )
    (comp (ref "C57")
      (value "1uF")
      (footprint "eagle-import:0402_CAP")
      (libsource (lib "eagle-import") (part "CAPACITOR0402_CAP"))
    )
    (comp (ref "C58")
      (value "1uF")
      (footprint "eagle-import:0402_CAP")
      (libsource (lib "eagle-import") (part "CAPACITOR0402_CAP"))
    )
    (comp (ref "C59")
      (value "1uF")
      (footprint "eagle-import:0402_CAP")
      (libsource (lib "eagle-import") (part "CAPACITOR0402_CAP"))
    )
    (comp (ref "C60")
      (value "1uF")
      (footprint "eagle-import:0402_CAP")
      (libsource (lib "eagle-import") (part "CAPACITOR0402_CAP"))
    )
    (comp (ref "C61")
      (value "1uF")
      (footprint "eagle-import:0402_CAP")
      (libsource (lib "eagle-import") (part "CAPACITOR0402_CAP"))
    )
    (comp (ref "C62")
      (value "1uF")
      (footprint "eagle-import:0402_CAP")
      (libsource (lib "eagle-import") (part "CAPACITOR0402_CAP"))
    )
    (comp (ref "C63")
      (value "1uF")
      (footprint "eagle-import:0402_CAP")
      (libsource (lib "eagle-import") (part "CAPACITOR0402_CAP"))
    )
    (comp (ref "C66")
      (value "0.1uF")
      (footprint "eagle-import:0402_CAP")
      (libsource (lib "eagle-import") (part "CAPACITOR0402_CAP"))
    )
    (comp (ref "C67")
      (value "0.1uF")
      (footprint "eagle-import:0402_CAP")
      (libsource (lib "eagle-import") (part "CAPACITOR0402_CAP"))
    )
    (comp (ref "C68")
      (value "0.1uF")
      (footprint "eagle-import:0402_CAP")
      (libsource (lib "eagle-import") (part "CAPACITOR0402_CAP"))
    )
    (comp (ref "C69")
      (value "0.1uF")
      (footprint "eagle-import:0402_CAP")
      (libsource (lib "eagle-import") (part "CAPACITOR0402_CAP"))
    )
    (comp (ref "C70")
      (value "0.1uF")
      (footprint "eagle-import:0402_CAP")
      (libsource (lib "eagle-import") (part "CAPACITOR0402_CAP"))
    )
    (comp (ref "C71")
      (value "0.1uF")
      (footprint "eagle-import:0402_CAP")
      (libsource (lib "eagle-import") (part "CAPACITOR0402_CAP"))
    )
    (comp (ref "C72")
      (value "0.1uF")
      (footprint "eagle-import:0402_CAP")
      (libsource (lib "eagle-import") (part "CAPACITOR0402_CAP"))
    )
    (comp (ref "C89")
      (value "1uF")
      (footprint "eagle-import:0402_CAP")
      (libsource (lib "eagle-import") (part "CAPACITOR0402_CAP"))
    )
    (comp (ref "C90")
      (value "1uF")
      (footprint "eagle-import:0402_CAP")
      (libsource (lib "eagle-import") (part "CAPACITOR0402_CAP"))
    )
    (comp (ref "C91")
      (value "100pF")
      (footprint "eagle-import:0402_CAP")
      (libsource (lib "eagle-import") (part "CAPACITOR0402_CAP"))
    )
    (comp (ref "C92")
      (value "100pF")
      (footprint "eagle-import:0402_CAP")
      (libsource (lib "eagle-import") (part "CAPACITOR0402_CAP"))
    )
    (comp (ref "C93")
      (value "100pF")
      (footprint "eagle-import:0402_CAP")
      (libsource (lib "eagle-import") (part "CAPACITOR0402_CAP"))
    )
    (comp (ref "C94")
      (value "100pF")
      (footprint "eagle-import:0402_CAP")
      (libsource (lib "eagle-import") (part "CAPACITOR0402_CAP"))
    )
    (comp (ref "C95")
      (value "0.1uF")
      (footprint "eagle-import:0402_CAP")
      (libsource (lib "eagle-import") (part "CAPACITOR0402_CAP"))
    )
    (comp (ref "C96")
      (value "1uF")
      (footprint "eagle-import:0402_CAP")
      (libsource (lib "eagle-import") (part "CAPACITOR0402_CAP"))
    )
    (comp (ref "C97")
      (value "0.1uF")
      (footprint "eagle-import:0402_CAP")
      (libsource (lib "eagle-import") (part "CAPACITOR0402_CAP"))
    )
    (comp (ref "C98")
      (value "0.1uF")
      (footprint "eagle-import:0402_CAP")
      (libsource (lib "eagle-import") (part "CAPACITOR0402_CAP"))
    )
    (comp (ref "C99")
      (value "1uF")
      (footprint "eagle-import:0402_CAP")
      (libsource (lib "eagle-import") (part "CAPACITOR0402_CAP"))
    )
    (comp (ref "C100")
      (value "1uF")
      (footprint "eagle-import:0402_CAP")
      (libsource (lib "eagle-import") (part "CAPACITOR0402_CAP"))
    )
    (comp (ref "C101")
      (value "0.1uF")
      (footprint "eagle-import:0402_CAP")
      (libsource (lib "eagle-import") (part "CAPACITOR0402_CAP"))
    )
    (comp (ref "C102")
      (value "0.1uF")
      (footprint "eagle-import:0402_CAP")
      (libsource (lib "eagle-import") (part "CAPACITOR0402_CAP"))
    )
    (comp (ref "C103")
      (value "0.1uF")
      (footprint "eagle-import:0402_CAP")
      (libsource (lib "eagle-import") (part "CAPACITOR0402_CAP"))
    )
    (comp (ref "C104")
      (value "0.1uF")
      (footprint "eagle-import:0402_CAP")
      (libsource (lib "eagle-import") (part "CAPACITOR0402_CAP"))
    )
    (comp (ref "C105")
      (value "0.1uF")
      (footprint "eagle-import:0402_CAP")
      (libsource (lib "eagle-import") (part "CAPACITOR0402_CAP"))
    )
    (comp (ref "C116")
      (value "100pF")
      (footprint "eagle-import:0402_CAP")
      (libsource (lib "eagle-import") (part "CAPACITOR0402_CAP"))
    )
    (comp (ref "C117")
      (value "100pF")
      (footprint "eagle-import:0402_CAP")
      (libsource (lib "eagle-import") (part "CAPACITOR0402_CAP"))
    )
    (comp (ref "IC2")
      (value "DAC7578SPWR")
      (footprint "eagle-import:SOP65P640X120-16N")
      (fields (field (name "MOUSER_PART_NUMBER") "595-DAC7578SPWR"))
      (libsource (lib "eagle-import") (part "DAC7578SPWR"))
    )
    (comp (ref "IC3")
      (value "LTC6229IMS8E#TRPBF")
      (footprint "eagle-import:SOP65P490X110-9N")
      (fields (field (name "MOUSER_PART_NUMBER") "584-LTC6229IMS8E#TR"))
      (libsource (lib "eagle-import") (part "LTC6229IMS8E#TRPBF"))
    )
    (comp (ref "IC5")
      (value "LTC6229IMS8E#TRPBF")
      (footprint "eagle-import:SOP65P490X110-9N")
      (fields (field (name "MOUSER_PART_NUMBER") "584-LTC6229IMS8E#TR"))
      (libsource (lib "eagle-import") (part "LTC6229IMS8E#TRPBF"))
    )
    (comp (ref "IC8")
      (value "LM358")
      (footprint "eagle-import:SO08")
      (libsource (lib "eagle-import") (part "OPAMP-DUALU"))
    )
    (comp (ref "IC9")
      (value "LM358")
      (footprint "eagle-import:SO08")
      (libsource (lib "eagle-import") (part "OPAMP-DUALU"))
    )
    (comp (ref "IC12")
      (value "SN74AUC2G66DCTR")
      (footprint "eagle-import:SOP65P400X130-8N")
      (fields (field (name "MOUSER_PART_NUMBER") "595-SN74AUC2G66DCTR"))
      (libsource (lib "eagle-import") (part "SN74AUC2G66DCTR"))
    )
    (comp (ref "IC13")
      (value "SN74AUC2G66DCTR")
      (footprint "eagle-import:SOP65P400X130-8N")
      (fields (field (name "MOUSER_PART_NUMBER") "595-SN74AUC2G66DCTR"))
      (libsource (lib "eagle-import") (part "SN74AUC2G66DCTR"))
    )
    (comp (ref "IC14")
      (value "SN74AUC2G66DCTR")
      (footprint "eagle-import:SOP65P400X130-8N")
      (fields (field (name "MOUSER_PART_NUMBER") "595-SN74AUC2G66DCTR"))
      (libsource (lib "eagle-import") (part "SN74AUC2G66DCTR"))
    )
    (comp (ref "IC15")
      (value "SN74AUC2G66DCTR")
      (footprint "eagle-import:SOP65P400X130-8N")
      (fields (field (name "MOUSER_PART_NUMBER") "595-SN74AUC2G66DCTR"))
      (libsource (lib "eagle-import") (part "SN74AUC2G66DCTR"))
    )
    (comp (ref "IC16")
      (value "DAC7578SPWR")
      (footprint "eagle-import:SOP65P640X120-16N")
      (fields (field (name "MOUSER_PART_NUMBER") "595-DAC7578SPWR"))
      (libsource (lib "eagle-import") (part "DAC7578SPWR"))
    )
    (comp (ref "IC17")
      (value "SN74AUC2G66DCTR")
      (footprint "eagle-import:SOP65P400X130-8N")
      (fields (field (name "MOUSER_PART_NUMBER") "595-SN74AUC2G66DCTR"))
      (libsource (lib "eagle-import") (part "SN74AUC2G66DCTR"))
    )
    (comp (ref "IC18")
      (value "SN74AUC2G66DCTR")
      (footprint "eagle-import:SOP65P400X130-8N")
      (fields (field (name "MOUSER_PART_NUMBER") "595-SN74AUC2G66DCTR"))
      (libsource (lib "eagle-import") (part "SN74AUC2G66DCTR"))
    )
    (comp (ref "IC19")
      (value "SN74AUC2G66DCTR")
      (footprint "eagle-import:SOP65P400X130-8N")
      (fields (field (name "MOUSER_PART_NUMBER") "595-SN74AUC2G66DCTR"))
      (libsource (lib "eagle-import") (part "SN74AUC2G66DCTR"))
    )
    (comp (ref "IC20")
      (value "SN74AUC2G66DCTR")
      (footprint "eagle-import:SOP65P400X130-8N")
      (fields (field (name "MOUSER_PART_NUMBER") "595-SN74AUC2G66DCTR"))
      (libsource (lib "eagle-import") (part "SN74AUC2G66DCTR"))
    )
    (comp (ref "IC21")
      (value "74AUP2GU04GW")
      (footprint "eagle-import:SOT65P210X110-6N")
      (fields
        (field (name "MANUFACTURER_PART_NUMBER") "74AUP2GU04GW,125")
        (field (name "MOUSER_PART_NUMBER") "771-74AUP2GU04GW-G")
      )
      (libsource (lib "eagle-import") (part "74AUP2GU04GW,125"))
    )
    (comp (ref "IC22")
      (value "74AUP2GU04GW")
      (footprint "eagle-import:SOT65P210X110-6N")
      (fields
        (field (name "MANUFACTURER_PART_NUMBER") "74AUP2GU04GW,125")
        (field (name "MOUSER_PART_NUMBER") "771-74AUP2GU04GW-G")
      )
      (libsource (lib "eagle-import") (part "74AUP2GU04GW,125"))
    )
    (comp (ref "IC23")
      (value "74AUP2GU04GW")
      (footprint "eagle-import:SOT65P210X110-6N")
      (fields
        (field (name "MANUFACTURER_PART_NUMBER") "74AUP2GU04GW,125")
        (field (name "MOUSER_PART_NUMBER") "771-74AUP2GU04GW-G")
      )
      (libsource (lib "eagle-import") (part "74AUP2GU04GW,125"))
    )
    (comp (ref "IC24")
      (value "74AUP2GU04GW")
      (footprint "eagle-import:SOT65P210X110-6N")
      (fields
        (field (name "MANUFACTURER_PART_NUMBER") "74AUP2GU04GW,125")
        (field (name "MOUSER_PART_NUMBER") "771-74AUP2GU04GW-G")
      )
      (libsource (lib "eagle-import") (part "74AUP2GU04GW,125"))
    )
    (comp (ref "IC27")
      (value "LM358")
      (footprint "eagle-import:SO08")
      (libsource (lib "eagle-import") (part "OPAMP-DUALU"))
    )
    (comp (ref "IC28")
      (value "SN74AUC2G66DCTR")
      (footprint "eagle-import:SOP65P400X130-8N")
      (fields (field (name "MOUSER_PART_NUMBER") "595-SN74AUC2G66DCTR"))
      (libsource (lib "eagle-import") (part "SN74AUC2G66DCTR"))
    )
    (comp (ref "IC30")
      (value "SN74AUC2G66DCTR")
      (footprint "eagle-import:SOP65P400X130-8N")
      (fields (field (name "MOUSER_PART_NUMBER") "595-SN74AUC2G66DCTR"))
      (libsource (lib "eagle-import") (part "SN74AUC2G66DCTR"))
    )
    (comp (ref "IC31")
      (value "SN74AUC2G66DCTR")
      (footprint "eagle-import:SOP65P400X130-8N")
      (fields (field (name "MOUSER_PART_NUMBER") "595-SN74AUC2G66DCTR"))
      (libsource (lib "eagle-import") (part "SN74AUC2G66DCTR"))
    )
    (comp (ref "IC32")
      (value "SN74AUC2G66DCTR")
      (footprint "eagle-import:SOP65P400X130-8N")
      (fields (field (name "MOUSER_PART_NUMBER") "595-SN74AUC2G66DCTR"))
      (libsource (lib "eagle-import") (part "SN74AUC2G66DCTR"))
    )
    (comp (ref "IC33")
      (value "LTC6229IMS8E#TRPBF")
      (footprint "eagle-import:SOP65P490X110-9N")
      (fields (field (name "MOUSER_PART_NUMBER") "584-LTC6229IMS8E#TR"))
      (libsource (lib "eagle-import") (part "LTC6229IMS8E#TRPBF"))
    )
    (comp (ref "IC34")
      (value "74AUP2GU04GW")
      (footprint "eagle-import:SOT65P210X110-6N")
      (fields
        (field (name "MANUFACTURER_PART_NUMBER") "74AUP2GU04GW,125")
        (field (name "MOUSER_PART_NUMBER") "771-74AUP2GU04GW-G")
      )
      (libsource (lib "eagle-import") (part "74AUP2GU04GW,125"))
    )
    (comp (ref "IC35")
      (value "74AUP2GU04GW")
      (footprint "eagle-import:SOT65P210X110-6N")
      (fields
        (field (name "MANUFACTURER_PART_NUMBER") "74AUP2GU04GW,125")
        (field (name "MOUSER_PART_NUMBER") "771-74AUP2GU04GW-G")
      )
      (libsource (lib "eagle-import") (part "74AUP2GU04GW,125"))
    )
    (comp (ref "R21")
      (value "330")
      (footprint "eagle-import:0402_RES")
      (libsource (lib "eagle-import") (part "RESISTOR0402_RES"))
    )
    (comp (ref "R22")
      (value "330")
      (footprint "eagle-import:0402_RES")
      (libsource (lib "eagle-import") (part "RESISTOR0402_RES"))
    )
    (comp (ref "R23")
      (value "330")
      (footprint "eagle-import:0402_RES")
      (libsource (lib "eagle-import") (part "RESISTOR0402_RES"))
    )
    (comp (ref "R24")
      (value "330")
      (footprint "eagle-import:0402_RES")
      (libsource (lib "eagle-import") (part "RESISTOR0402_RES"))
    )
    (comp (ref "R27")
      (value "330")
      (footprint "eagle-import:0402_RES")
      (libsource (lib "eagle-import") (part "RESISTOR0402_RES"))
    )
    (comp (ref "R28")
      (value "330")
      (footprint "eagle-import:0402_RES")
      (libsource (lib "eagle-import") (part "RESISTOR0402_RES"))
    )
    (comp (ref "R29")
      (value "330")
      (footprint "eagle-import:0402_RES")
      (libsource (lib "eagle-import") (part "RESISTOR0402_RES"))
    )
    (comp (ref "R30")
      (value "330")
      (footprint "eagle-import:0402_RES")
      (libsource (lib "eagle-import") (part "RESISTOR0402_RES"))
    )
    (comp (ref "R37")
      (value "330")
      (footprint "eagle-import:0402_RES")
      (libsource (lib "eagle-import") (part "RESISTOR0402_RES"))
    )
    (comp (ref "R39")
      (value "330")
      (footprint "eagle-import:0402_RES")
      (libsource (lib "eagle-import") (part "RESISTOR0402_RES"))
    )
    (comp (ref "R41")
      (value "330")
      (footprint "eagle-import:0402_RES")
      (libsource (lib "eagle-import") (part "RESISTOR0402_RES"))
    )
    (comp (ref "R43")
      (value "330")
      (footprint "eagle-import:0402_RES")
      (libsource (lib "eagle-import") (part "RESISTOR0402_RES"))
    )
    (comp (ref "R44")
      (value "330")
      (footprint "eagle-import:0402_RES")
      (libsource (lib "eagle-import") (part "RESISTOR0402_RES"))
    )
    (comp (ref "R45")
      (value "330")
      (footprint "eagle-import:0402_RES")
      (libsource (lib "eagle-import") (part "RESISTOR0402_RES"))
    )
    (comp (ref "R46")
      (value "330")
      (footprint "eagle-import:0402_RES")
      (libsource (lib "eagle-import") (part "RESISTOR0402_RES"))
    )
    (comp (ref "R47")
      (value "100")
      (footprint "eagle-import:0402_RES")
      (libsource (lib "eagle-import") (part "RESISTOR0402_RES"))
    )
    (comp (ref "R52")
      (value "330")
      (footprint "eagle-import:0402_RES")
      (libsource (lib "eagle-import") (part "RESISTOR0402_RES"))
    )
    (comp (ref "R53")
      (value "100")
      (footprint "eagle-import:0402_RES")
      (libsource (lib "eagle-import") (part "RESISTOR0402_RES"))
    )
    (comp (ref "R54")
      (value "100")
      (footprint "eagle-import:0402_RES")
      (libsource (lib "eagle-import") (part "RESISTOR0402_RES"))
    )
    (comp (ref "R55")
      (value "100")
      (footprint "eagle-import:0402_RES")
      (libsource (lib "eagle-import") (part "RESISTOR0402_RES"))
    )
    (comp (ref "R56")
      (value "100")
      (footprint "eagle-import:0402_RES")
      (libsource (lib "eagle-import") (part "RESISTOR0402_RES"))
    )
    (comp (ref "R57")
      (value "100")
      (footprint "eagle-import:0402_RES")
      (libsource (lib "eagle-import") (part "RESISTOR0402_RES"))
    )
    (comp (ref "R58")
      (value "100")
      (footprint "eagle-import:0402_RES")
      (libsource (lib "eagle-import") (part "RESISTOR0402_RES"))
    )
    (comp (ref "R59")
      (value "100")
      (footprint "eagle-import:0402_RES")
      (libsource (lib "eagle-import") (part "RESISTOR0402_RES"))
    )
    (comp (ref "R62")
      (value "1k")
      (footprint "eagle-import:0402_RES")
      (libsource (lib "eagle-import") (part "RESISTOR0402_RES"))
    )
    (comp (ref "R63")
      (value "1k")
      (footprint "eagle-import:0402_RES")
      (libsource (lib "eagle-import") (part "RESISTOR0402_RES"))
    )
    (comp (ref "R64")
      (value "1k")
      (footprint "eagle-import:0402_RES")
      (libsource (lib "eagle-import") (part "RESISTOR0402_RES"))
    )
    (comp (ref "R65")
      (value "1k")
      (footprint "eagle-import:0402_RES")
      (libsource (lib "eagle-import") (part "RESISTOR0402_RES"))
    )
    (comp (ref "R66")
      (value "1k")
      (footprint "eagle-import:0402_RES")
      (libsource (lib "eagle-import") (part "RESISTOR0402_RES"))
    )
    (comp (ref "R67")
      (value "1k")
      (footprint "eagle-import:0402_RES")
      (libsource (lib "eagle-import") (part "RESISTOR0402_RES"))
    )
    (comp (ref "R68")
      (value "1k")
      (footprint "eagle-import:0402_RES")
      (libsource (lib "eagle-import") (part "RESISTOR0402_RES"))
    )
    (comp (ref "R69")
      (value "1k")
      (footprint "eagle-import:0402_RES")
      (libsource (lib "eagle-import") (part "RESISTOR0402_RES"))
    )
    (comp (ref "R74")
      (value "100")
      (footprint "eagle-import:0402_RES")
      (libsource (lib "eagle-import") (part "RESISTOR0402_RES"))
    )
    (comp (ref "R75")
      (value "100")
      (footprint "eagle-import:0402_RES")
      (libsource (lib "eagle-import") (part "RESISTOR0402_RES"))
    )
    (comp (ref "R76")
      (value "100")
      (footprint "eagle-import:0402_RES")
      (libsource (lib "eagle-import") (part "RESISTOR0402_RES"))
    )
    (comp (ref "R77")
      (value "100")
      (footprint "eagle-import:0402_RES")
      (libsource (lib "eagle-import") (part "RESISTOR0402_RES"))
    )
    (comp (ref "R80")
      (value "330")
      (footprint "eagle-import:0402_RES")
      (libsource (lib "eagle-import") (part "RESISTOR0402_RES"))
    )
    (comp (ref "R81")
      (value "330")
      (footprint "eagle-import:0402_RES")
      (libsource (lib "eagle-import") (part "RESISTOR0402_RES"))
    )
    (comp (ref "R82")
      (value "330")
      (footprint "eagle-import:0402_RES")
      (libsource (lib "eagle-import") (part "RESISTOR0402_RES"))
    )
    (comp (ref "R83")
      (value "330")
      (footprint "eagle-import:0402_RES")
      (libsource (lib "eagle-import") (part "RESISTOR0402_RES"))
    )
    (comp (ref "R91")
      (value "330")
      (footprint "eagle-import:0402_RES")
      (libsource (lib "eagle-import") (part "RESISTOR0402_RES"))
    )
    (comp (ref "R92")
      (value "100")
      (footprint "eagle-import:0402_RES")
      (libsource (lib "eagle-import") (part "RESISTOR0402_RES"))
    )
    (comp (ref "R93")
      (value "100")
      (footprint "eagle-import:0402_RES")
      (libsource (lib "eagle-import") (part "RESISTOR0402_RES"))
    )
    (comp (ref "R94")
      (value "100")
      (footprint "eagle-import:0402_RES")
      (libsource (lib "eagle-import") (part "RESISTOR0402_RES"))
    )
    (comp (ref "R95")
      (value "100")
      (footprint "eagle-import:0402_RES")
      (libsource (lib "eagle-import") (part "RESISTOR0402_RES"))
    )
    (comp (ref "R96")
      (value "1k")
      (footprint "eagle-import:0402_RES")
      (libsource (lib "eagle-import") (part "RESISTOR0402_RES"))
    )
    (comp (ref "R97")
      (value "1k")
      (footprint "eagle-import:0402_RES")
      (libsource (lib "eagle-import") (part "RESISTOR0402_RES"))
    )
    (comp (ref "R98")
      (value "1k")
      (footprint "eagle-import:0402_RES")
      (libsource (lib "eagle-import") (part "RESISTOR0402_RES"))
    )
    (comp (ref "R99")
      (value "1k")
      (footprint "eagle-import:0402_RES")
      (libsource (lib "eagle-import") (part "RESISTOR0402_RES"))
    )
    (comp (ref "R100")
      (value "100")
      (footprint "eagle-import:0402_RES")
      (libsource (lib "eagle-import") (part "RESISTOR0402_RES"))
    )
    (comp (ref "R101")
      (value "100")
      (footprint "eagle-import:0402_RES")
      (libsource (lib "eagle-import") (part "RESISTOR0402_RES"))
    )
    (comp (ref "R102")
      (value "330")
      (footprint "eagle-import:0402_RES")
      (libsource (lib "eagle-import") (part "RESISTOR0402_RES"))
    )
    (comp (ref "R103")
      (value "330")
      (footprint "eagle-import:0402_RES")
      (libsource (lib "eagle-import") (part "RESISTOR0402_RES"))
    )
    (comp (ref "R104")
      (value "330")
      (footprint "eagle-import:0402_RES")
      (libsource (lib "eagle-import") (part "RESISTOR0402_RES"))
    )
    (comp (ref "R105")
      (value "330")
      (footprint "eagle-import:0402_RES")
      (libsource (lib "eagle-import") (part "RESISTOR0402_RES"))
    )
    (comp (ref "R106")
      (value "330")
      (footprint "eagle-import:0402_RES")
      (libsource (lib "eagle-import") (part "RESISTOR0402_RES"))
    )
    (comp (ref "R107")
      (value "330")
      (footprint "eagle-import:0402_RES")
      (libsource (lib "eagle-import") (part "RESISTOR0402_RES"))
    )
    (comp (ref "R108")
      (value "330")
      (footprint "eagle-import:0402_RES")
      (libsource (lib "eagle-import") (part "RESISTOR0402_RES"))
    )
    (comp (ref "R109")
      (value "330")
      (footprint "eagle-import:0402_RES")
      (libsource (lib "eagle-import") (part "RESISTOR0402_RES"))
    )
    (comp (ref "R110")
      (value "330")
      (footprint "eagle-import:0402_RES")
      (libsource (lib "eagle-import") (part "RESISTOR0402_RES"))
    )
  )
  (nets
    (net (code "1") (name "1V8") (class "Default")
      (node (ref "C102") (pin "1") (pinfunction "1_1") (pintype "bidirectional"))
      (node (ref "C103") (pin "1") (pinfunction "1_1") (pintype "bidirectional"))
      (node (ref "C105") (pin "1") (pinfunction "1_1") (pintype "bidirectional"))
      (node (ref "C118") (pin "1") (pinfunction "1_1") (pintype "bidirectional"))
      (node (ref "C14") (pin "1") (pinfunction "1_1") (pintype "bidirectional"))
      (node (ref "C34") (pin "1") (pinfunction "1_1") (pintype "passive"))
      (node (ref "C35") (pin "1") (pinfunction "1_1") (pintype "bidirectional"))
      (node (ref "C36") (pin "1") (pinfunction "1_1") (pintype "bidirectional"))
      (node (ref "C49") (pin "1") (pinfunction "1_1") (pintype "bidirectional"))
      (node (ref "C5") (pin "1") (pinfunction "1_1") (pintype "bidirectional"))
      (node (ref "C52") (pin "1") (pinfunction "1_1") (pintype "bidirectional"))
      (node (ref "C53") (pin "1") (pinfunction "1_1") (pintype "bidirectional"))
      (node (ref "C55") (pin "1") (pinfunction "1_1") (pintype "bidirectional"))
      (node (ref "C68") (pin "1") (pinfunction "1_1") (pintype "bidirectional"))
      (node (ref "C69") (pin "1") (pinfunction "1_1") (pintype "bidirectional"))
      (node (ref "C7") (pin "1") (pinfunction "1_1") (pintype "bidirectional"))
      (node (ref "C74") (pin "1") (pinfunction "1_1") (pintype "bidirectional"))
      (node (ref "IC12") (pin "8") (pinfunction "VCC_8") (pintype "bidirectional"))
      (node (ref "IC13") (pin "8") (pinfunction "VCC_8") (pintype "bidirectional"))
      (node (ref "IC16") (pin "8") (pinfunction "VREFIN_8") (pintype "bidirectional"))
      (node (ref "IC17") (pin "8") (pinfunction "VCC_8") (pintype "bidirectional"))
      (node (ref "IC18") (pin "8") (pinfunction "VCC_8") (pintype "bidirectional"))
      (node (ref "IC2") (pin "8") (pinfunction "VREFIN_8") (pintype "bidirectional"))
      (node (ref "IC21") (pin "5") (pinfunction "VCC_5") (pintype "bidirectional"))
      (node (ref "IC23") (pin "5") (pinfunction "VCC_5") (pintype "bidirectional"))
      (node (ref "IC26") (pin "2") (pinfunction "VOUT_2") (pintype "output"))
      (node (ref "IC30") (pin "8") (pinfunction "VCC_8") (pintype "bidirectional"))
      (node (ref "IC31") (pin "8") (pinfunction "VCC_8") (pintype "bidirectional"))
      (node (ref "IC34") (pin "5") (pinfunction "VCC_5") (pintype "bidirectional"))
      (node (ref "IC7") (pin "8") (pinfunction "VH_8") (pintype "bidirectional"))
      (node (ref "J3") (pin "7") (pinfunction "7_7") (pintype "bidirectional"))
      (node (ref "R48") (pin "1") (pinfunction "1_1") (pintype "passive"))
      (node (ref "R50") (pin "1") (pinfunction "1_1") (pintype "passive"))
      (node (ref "U$1") (pin "1") (pinfunction "G_1") (pintype "passive"))
      (node (ref "U$2") (pin "1") (pinfunction "G_1") (pintype "passive"))
    )
    (net (code "2") (name "1V8-") (class "Default")
      (node (ref "C101") (pin "1") (pinfunction "1_1") (pintype "bidirectional"))
      (node (ref "C104") (pin "1") (pinfunction "1_1") (pintype "bidirectional"))
      (node (ref "C117") (pin "1") (pinfunction "1_1") (pintype "bidirectional"))
      (node (ref "C125") (pin "C") (pinfunction "-_C") (pintype "passive"))
      (node (ref "C23") (pin "1") (pinfunction "1_1") (pintype "bidirectional"))
      (node (ref "C30") (pin "1") (pinfunction "1_1") (pintype "bidirectional"))
      (node (ref "C50") (pin "1") (pinfunction "1_1") (pintype "bidirectional"))
      (node (ref "C51") (pin "1") (pinfunction "1_1") (pintype "bidirectional"))
      (node (ref "C66") (pin "1") (pinfunction "1_1") (pintype "bidirectional"))
      (node (ref "C67") (pin "1") (pinfunction "1_1") (pintype "bidirectional"))
      (node (ref "C70") (pin "1") (pinfunction "1_1") (pintype "bidirectional"))
      (node (ref "C71") (pin "1") (pinfunction "1_1") (pintype "bidirectional"))
      (node (ref "C72") (pin "1") (pinfunction "1_1") (pintype "bidirectional"))
      (node (ref "C92") (pin "1") (pinfunction "1_1") (pintype "bidirectional"))
      (node (ref "C94") (pin "1") (pinfunction "1_1") (pintype "bidirectional"))
      (node (ref "C95") (pin "1") (pinfunction "1_1") (pintype "bidirectional"))
      (node (ref "IC14") (pin "4") (pinfunction "GND_4") (pintype "bidirectional"))
      (node (ref "IC15") (pin "4") (pinfunction "GND_4") (pintype "bidirectional"))
      (node (ref "IC19") (pin "4") (pinfunction "GND_4") (pintype "bidirectional"))
      (node (ref "IC20") (pin "4") (pinfunction "GND_4") (pintype "bidirectional"))
      (node (ref "IC22") (pin "2") (pinfunction "GND_2") (pintype "bidirectional"))
      (node (ref "IC24") (pin "2") (pinfunction "GND_2") (pintype "bidirectional"))
      (node (ref "IC28") (pin "4") (pinfunction "GND_4") (pintype "bidirectional"))
      (node (ref "IC29") (pin "3") (pinfunction "OUTPUT_3") (pintype "bidirectional"))
      (node (ref "IC3") (pin "4") (pinfunction "V-_1_4") (pintype "bidirectional"))
      (node (ref "IC3") (pin "9") (pinfunction "V-_2_9") (pintype "bidirectional"))
      (node (ref "IC32") (pin "4") (pinfunction "GND_4") (pintype "bidirectional"))
      (node (ref "IC33") (pin "4") (pinfunction "V-_1_4") (pintype "bidirectional"))
      (node (ref "IC33") (pin "9") (pinfunction "V-_2_9") (pintype "bidirectional"))
      (node (ref "IC35") (pin "2") (pinfunction "GND_2") (pintype "bidirectional"))
      (node (ref "IC5") (pin "4") (pinfunction "V-_1_4") (pintype "bidirectional"))
      (node (ref "IC5") (pin "9") (pinfunction "V-_2_9") (pintype "bidirectional"))
      (node (ref "J3") (pin "6") (pinfunction "6_6") (pintype "bidirectional"))
      (node (ref "R102") (pin "2") (pinfunction "2_2") (pintype "passive"))
      (node (ref "R106") (pin "1") (pinfunction "1_1") (pintype "passive"))
      (node (ref "R14") (pin "1") (pinfunction "1_1") (pintype "passive"))
      (node (ref "R22") (pin "2") (pinfunction "2_2") (pintype "passive"))
      (node (ref "R28") (pin "1") (pinfunction "1_1") (pintype "passive"))
      (node (ref "R39") (pin "2") (pinfunction "2_2") (pintype "passive"))
      (node (ref "R45") (pin "1") (pinfunction "1_1") (pintype "passive"))
    )
    (net (code "3") (name "1V8FMC") (class "Default")
      (node (ref "J2") (pin "G39") (pinfunction "G39_G39") (pintype "bidirectional"))
      (node (ref "J2") (pin "H40") (pinfunction "H40_H40") (pintype "bidirectional"))
      (node (ref "J3") (pin "5") (pinfunction "5_5") (pintype "bidirectional"))
    )
    (net (code "4") (name "3V3") (class "Default")
      (node (ref "C13") (pin "1") (pinfunction "1_1") (pintype "bidirectional"))
      (node (ref "J2") (pin "C39") (pinfunction "C39_C39") (pintype "bidirectional"))
      (node (ref "J2") (pin "D36") (pinfunction "D36_D36") (pintype "bidirectional"))
      (node (ref "J2") (pin "D38") (pinfunction "D38_D38") (pintype "bidirectional"))
      (node (ref "J2") (pin "D40") (pinfunction "D40_D40") (pintype "bidirectional"))
      (node (ref "J3") (pin "4") (pinfunction "4_4") (pintype "bidirectional"))
    )
    (net (code "5") (name "12V") (class "Default")
      (node (ref "C108") (pin "1") (pinfunction "1_1") (pintype "passive"))
      (node (ref "C11") (pin "1") (pinfunction "1_1") (pintype "passive"))
      (node (ref "C112") (pin "1") (pinfunction "1_1") (pintype "passive"))
      (node (ref "C12") (pin "1") (pinfunction "1_1") (pintype "passive"))
      (node (ref "C64") (pin "1") (pinfunction "1_1") (pintype "passive"))
      (node (ref "C8") (pin "1") (pinfunction "1_1") (pintype "passive"))
      (node (ref "C80") (pin "1") (pinfunction "1_1") (pintype "passive"))
      (node (ref "IC36") (pin "7") (pinfunction "VIN_7") (pintype "bidirectional"))
      (node (ref "IC37") (pin "7") (pinfunction "VIN_7") (pintype "bidirectional"))
      (node (ref "J2") (pin "C35") (pinfunction "C35_C35") (pintype "bidirectional"))
      (node (ref "J2") (pin "C37") (pinfunction "C37_C37") (pintype "bidirectional"))
      (node (ref "J3") (pin "1") (pinfunction "1_1") (pintype "bidirectional"))
    )
    (net (code "6") (name "BOOT1") (class "Default")
      (node (ref "C122") (pin "1") (pinfunction "1_1") (pintype "bidirectional"))
      (node (ref "IC37") (pin "1") (pinfunction "BOOT_1") (pintype "bidirectional"))
    )
    (net (code "7") (name "BOOT2") (class "Default")
      (node (ref "C107") (pin "1") (pinfunction "1_1") (pintype "bidirectional"))
      (node (ref "IC36") (pin "1") (pinfunction "BOOT_1") (pintype "bidirectional"))
    )
    (net (code "8") (name "C10") (class "Default")
      (node (ref "IC12") (pin "7") (pinfunction "1C_7") (pintype "bidirectional"))
      (node (ref "IC21") (pin "1") (pinfunction "1A_1") (pintype "bidirectional"))
      (node (ref "IO_C10") (pin "1") (pinfunction "1_1") (pintype "passive"))
      (node (ref "J2") (pin "C10") (pinfunction "C10_C10") (pintype "bidirectional"))
      (node (ref "R4") (pin "2") (pinfunction "2_2") (pintype "passive"))
      (node (ref "SV2") (pin "13") (pinfunction "13_13") (pintype "passive"))
    )
    (net (code "9") (name "C10N") (class "Default")
      (node (ref "IC17") (pin "7") (pinfunction "1C_7") (pintype "bidirectional"))
      (node (ref "IC21") (pin "6") (pinfunction "1Y_6") (pintype "bidirectional"))
    )
    (net (code "10") (name "C11") (class "Default")
      (node (ref "IC12") (pin "3") (pinfunction "2C_3") (pintype "bidirectional"))
      (node (ref "IC21") (pin "3") (pinfunction "2A_3") (pintype "bidirectional"))
      (node (ref "J2") (pin "C11") (pinfunction "C11_C11") (pintype "bidirectional"))
      (node (ref "SV2") (pin "14") (pinfunction "14_14") (pintype "passive"))
    )
    (net (code "11") (name "C11N") (class "Default")
      (node (ref "IC17") (pin "3") (pinfunction "2C_3") (pintype "bidirectional"))
      (node (ref "IC21") (pin "4") (pinfunction "2Y_4") (pintype "bidirectional"))
    )
    (net (code "12") (name "C14") (class "Default")
      (node (ref "IC13") (pin "7") (pinfunction "1C_7") (pintype "bidirectional"))
      (node (ref "IC23") (pin "1") (pinfunction "1A_1") (pintype "bidirectional"))
      (node (ref "J2") (pin "C14") (pinfunction "C14_C14") (pintype "bidirectional"))
      (node (ref "SV2") (pin "16") (pinfunction "16_16") (pintype "passive"))
    )
    (net (code "13") (name "C14N") (class "Default")
      (node (ref "IC18") (pin "7") (pinfunction "1C_7") (pintype "bidirectional"))
      (node (ref "IC23") (pin "6") (pinfunction "1Y_6") (pintype "bidirectional"))
    )
    (net (code "14") (name "C15") (class "Default")
      (node (ref "IC13") (pin "3") (pinfunction "2C_3") (pintype "bidirectional"))
      (node (ref "IC23") (pin "3") (pinfunction "2A_3") (pintype "bidirectional"))
      (node (ref "J2") (pin "C15") (pinfunction "C15_C15") (pintype "bidirectional"))
      (node (ref "SV2") (pin "17") (pinfunction "17_17") (pintype "passive"))
    )
    (net (code "15") (name "C15N") (class "Default")
      (node (ref "IC18") (pin "3") (pinfunction "2C_3") (pintype "bidirectional"))
      (node (ref "IC23") (pin "4") (pinfunction "2Y_4") (pintype "bidirectional"))
    )
    (net (code "16") (name "C18") (class "Default")
      (node (ref "IC30") (pin "3") (pinfunction "2C_3") (pintype "bidirectional"))
      (node (ref "IC34") (pin "1") (pinfunction "1A_1") (pintype "bidirectional"))
      (node (ref "J2") (pin "C18") (pinfunction "C18_C18") (pintype "bidirectional"))
      (node (ref "SV2") (pin "19") (pinfunction "19_19") (pintype "passive"))
    )
    (net (code "17") (name "C18N") (class "Default")
      (node (ref "IC31") (pin "3") (pinfunction "2C_3") (pintype "bidirectional"))
      (node (ref "IC34") (pin "6") (pinfunction "1Y_6") (pintype "bidirectional"))
    )
    (net (code "18") (name "C19") (class "Default")
      (node (ref "IC30") (pin "7") (pinfunction "1C_7") (pintype "bidirectional"))
      (node (ref "IC34") (pin "3") (pinfunction "2A_3") (pintype "bidirectional"))
      (node (ref "J2") (pin "C19") (pinfunction "C19_C19") (pintype "bidirectional"))
      (node (ref "SV2") (pin "20") (pinfunction "20_20") (pintype "passive"))
    )
    (net (code "19") (name "C19N") (class "Default")
      (node (ref "IC31") (pin "7") (pinfunction "1C_7") (pintype "bidirectional"))
      (node (ref "IC34") (pin "4") (pinfunction "2Y_4") (pintype "bidirectional"))
    )
    (net (code "20") (name "C22") (class "Default")
      (node (ref "J2") (pin "C22") (pinfunction "C22_C22") (pintype "bidirectional"))
      (node (ref "R109") (pin "1") (pinfunction "1_1") (pintype "passive"))
      (node (ref "R91") (pin "2") (pinfunction "2_2") (pintype "passive"))
      (node (ref "SV1") (pin "1") (pinfunction "1_1") (pintype "passive"))
    )
    (net (code "21") (name "C22I") (class "Default")
      (node (ref "IC28") (pin "3") (pinfunction "2C_3") (pintype "bidirectional"))
      (node (ref "IC33") (pin "1") (pinfunction "OUTA_1") (pintype "bidirectional"))
      (node (ref "IC35") (pin "1") (pinfunction "1A_1") (pintype "bidirectional"))
      (node (ref "R103") (pin "1") (pinfunction "1_1") (pintype "passive"))
    )
    (net (code "22") (name "C22N") (class "Default")
      (node (ref "IC32") (pin "3") (pinfunction "2C_3") (pintype "bidirectional"))
      (node (ref "IC35") (pin "6") (pinfunction "1Y_6") (pintype "bidirectional"))
    )
    (net (code "23") (name "C23") (class "Default")
      (node (ref "J2") (pin "C23") (pinfunction "C23_C23") (pintype "bidirectional"))
      (node (ref "R105") (pin "1") (pinfunction "1_1") (pintype "passive"))
      (node (ref "R110") (pin "1") (pinfunction "1_1") (pintype "passive"))
      (node (ref "SV1") (pin "2") (pinfunction "2_2") (pintype "passive"))
    )
    (net (code "24") (name "C23I") (class "Default")
      (node (ref "IC28") (pin "7") (pinfunction "1C_7") (pintype "bidirectional"))
      (node (ref "IC33") (pin "7") (pinfunction "OUTB_7") (pintype "bidirectional"))
      (node (ref "IC35") (pin "3") (pinfunction "2A_3") (pintype "bidirectional"))
      (node (ref "R107") (pin "2") (pinfunction "2_2") (pintype "passive"))
    )
    (net (code "25") (name "C23N") (class "Default")
      (node (ref "IC32") (pin "7") (pinfunction "1C_7") (pintype "bidirectional"))
      (node (ref "IC35") (pin "4") (pinfunction "2Y_4") (pintype "bidirectional"))
    )
    (net (code "26") (name "C26") (class "Default")
      (node (ref "J2") (pin "C26") (pinfunction "C26_C26") (pintype "bidirectional"))
      (node (ref "J4") (pin "1") (pinfunction "P$1_1") (pintype "bidirectional"))
    )
    (net (code "27") (name "C27") (class "Default")
      (node (ref "J2") (pin "C27") (pinfunction "C27_C27") (pintype "bidirectional"))
      (node (ref "J4") (pin "3") (pinfunction "P$3_3") (pintype "bidirectional"))
    )
    (net (code "28") (name "DACADDR") (class "Default")
      (node (ref "IC2") (pin "2") (pinfunction "ADDR0_2") (pintype "bidirectional"))
    )
    (net (code "29") (name "DACCLR") (class "Default")
      (node (ref "IC16") (pin "9") (pinfunction "~{CLR}_9") (pintype "bidirectional"))
      (node (ref "IC2") (pin "9") (pinfunction "~{CLR}_9") (pintype "bidirectional"))
    )
    (net (code "30") (name "DACLDAC") (class "Default")
      (node (ref "IC16") (pin "1") (pinfunction "~{LDAC}_1") (pintype "bidirectional"))
      (node (ref "IC2") (pin "1") (pinfunction "~{LDAC}_1") (pintype "bidirectional"))
    )
    (net (code "31") (name "DACN1") (class "Default")
      (node (ref "C57") (pin "2") (pinfunction "2_2") (pintype "bidirectional"))
      (node (ref "R54") (pin "2") (pinfunction "2_2") (pintype "passive"))
      (node (ref "R64") (pin "2") (pinfunction "2_2") (pintype "passive"))
    )
    (net (code "32") (name "DACN1I") (class "Default")
      (node (ref "C17") (pin "2") (pinfunction "2_2") (pintype "bidirectional"))
      (node (ref "IC14") (pin "1") (pinfunction "1A_1") (pintype "bidirectional"))
      (node (ref "R74") (pin "1") (pinfunction "1_1") (pintype "passive"))
    )
    (net (code "33") (name "DACN2") (class "Default")
      (node (ref "C61") (pin "1") (pinfunction "1_1") (pintype "bidirectional"))
      (node (ref "R58") (pin "1") (pinfunction "1_1") (pintype "passive"))
      (node (ref "R65") (pin "2") (pinfunction "2_2") (pintype "passive"))
    )
    (net (code "34") (name "DACN2I") (class "Default")
      (node (ref "C18") (pin "2") (pinfunction "2_2") (pintype "bidirectional"))
      (node (ref "IC14") (pin "5") (pinfunction "2A_5") (pintype "bidirectional"))
      (node (ref "R75") (pin "1") (pinfunction "1_1") (pintype "passive"))
    )
    (net (code "35") (name "DACN3") (class "Default")
      (node (ref "C56") (pin "2") (pinfunction "2_2") (pintype "bidirectional"))
      (node (ref "R55") (pin "2") (pinfunction "2_2") (pintype "passive"))
      (node (ref "R68") (pin "2") (pinfunction "2_2") (pintype "passive"))
    )
    (net (code "36") (name "DACN3I") (class "Default")
      (node (ref "C19") (pin "2") (pinfunction "2_2") (pintype "bidirectional"))
      (node (ref "IC15") (pin "1") (pinfunction "1A_1") (pintype "bidirectional"))
      (node (ref "R76") (pin "1") (pinfunction "1_1") (pintype "passive"))
    )
    (net (code "37") (name "DACN4") (class "Default")
      (node (ref "C60") (pin "1") (pinfunction "1_1") (pintype "bidirectional"))
      (node (ref "R59") (pin "1") (pinfunction "1_1") (pintype "passive"))
      (node (ref "R69") (pin "2") (pinfunction "2_2") (pintype "passive"))
    )
    (net (code "38") (name "DACN4I") (class "Default")
      (node (ref "C20") (pin "2") (pinfunction "2_2") (pintype "bidirectional"))
      (node (ref "IC15") (pin "5") (pinfunction "2A_5") (pintype "bidirectional"))
      (node (ref "R77") (pin "1") (pinfunction "1_1") (pintype "passive"))
    )
    (net (code "39") (name "DACN5") (class "Default")
      (node (ref "C96") (pin "1") (pinfunction "1_1") (pintype "bidirectional"))
      (node (ref "R95") (pin "1") (pinfunction "1_1") (pintype "passive"))
      (node (ref "R98") (pin "2") (pinfunction "2_2") (pintype "passive"))
    )
    (net (code "40") (name "DACN5I") (class "Default")
      (node (ref "C99") (pin "2") (pinfunction "2_2") (pintype "bidirectional"))
      (node (ref "IC28") (pin "1") (pinfunction "1A_1") (pintype "bidirectional"))
      (node (ref "R100") (pin "1") (pinfunction "1_1") (pintype "passive"))
    )
    (net (code "41") (name "DACN6") (class "Default")
      (node (ref "C89") (pin "1") (pinfunction "1_1") (pintype "bidirectional"))
      (node (ref "R93") (pin "1") (pinfunction "1_1") (pintype "passive"))
      (node (ref "R99") (pin "2") (pinfunction "2_2") (pintype "passive"))
    )
    (net (code "42") (name "DACN6I") (class "Default")
      (node (ref "C100") (pin "2") (pinfunction "2_2") (pintype "bidirectional"))
      (node (ref "IC28") (pin "5") (pinfunction "2A_5") (pintype "bidirectional"))
      (node (ref "R101") (pin "1") (pinfunction "1_1") (pintype "passive"))
    )
    (net (code "43") (name "DACOFFSETN") (class "Default")
      (node (ref "IC16") (pin "12") (pinfunction "VOUTD_12") (pintype "bidirectional"))
      (node (ref "R17") (pin "2") (pinfunction "2_2") (pintype "passive"))
    )
    (net (code "44") (name "DACOFFSETNI") (class "Default")
      (node (ref "IC10") (pin "7") (pinfunction "OUT_7") (pintype "output"))
      (node (ref "R115") (pin "2") (pinfunction "2_2") (pintype "passive"))
      (node (ref "R25") (pin "2") (pinfunction "2_2") (pintype "passive"))
    )
    (net (code "45") (name "DACOFFSETP") (class "Default")
      (node (ref "IC16") (pin "4") (pinfunction "VOUTA_4") (pintype "bidirectional"))
      (node (ref "R31") (pin "2") (pinfunction "2_2") (pintype "passive"))
    )
    (net (code "46") (name "DACP1") (class "Default")
      (node (ref "C59") (pin "2") (pinfunction "2_2") (pintype "bidirectional"))
      (node (ref "IC12") (pin "1") (pinfunction "1A_1") (pintype "bidirectional"))
      (node (ref "R47") (pin "2") (pinfunction "2_2") (pintype "passive"))
    )
    (net (code "47") (name "DACP2") (class "Default")
      (node (ref "C63") (pin "1") (pinfunction "1_1") (pintype "bidirectional"))
      (node (ref "IC12") (pin "5") (pinfunction "2A_5") (pintype "bidirectional"))
      (node (ref "R56") (pin "1") (pinfunction "1_1") (pintype "passive"))
    )
    (net (code "48") (name "DACP3") (class "Default")
      (node (ref "C58") (pin "2") (pinfunction "2_2") (pintype "bidirectional"))
      (node (ref "IC13") (pin "1") (pinfunction "1A_1") (pintype "bidirectional"))
      (node (ref "R53") (pin "2") (pinfunction "2_2") (pintype "passive"))
    )
    (net (code "49") (name "DACP4") (class "Default")
      (node (ref "C62") (pin "1") (pinfunction "1_1") (pintype "bidirectional"))
      (node (ref "IC13") (pin "5") (pinfunction "2A_5") (pintype "bidirectional"))
      (node (ref "R57") (pin "1") (pinfunction "1_1") (pintype "passive"))
    )
    (net (code "50") (name "DACP5") (class "Default")
      (node (ref "C90") (pin "1") (pinfunction "1_1") (pintype "bidirectional"))
      (node (ref "IC30") (pin "1") (pinfunction "1A_1") (pintype "bidirectional"))
      (node (ref "R94") (pin "1") (pinfunction "1_1") (pintype "passive"))
    )
    (net (code "51") (name "DACP6") (class "Default")
      (node (ref "C31") (pin "1") (pinfunction "1_1") (pintype "bidirectional"))
      (node (ref "IC30") (pin "5") (pinfunction "2A_5") (pintype "bidirectional"))
      (node (ref "R92") (pin "1") (pinfunction "1_1") (pintype "passive"))
    )
    (net (code "52") (name "FB1") (class "Default")
      (node (ref "IC37") (pin "4") (pinfunction "VSENSE_4") (pintype "bidirectional"))
      (node (ref "R60") (pin "2") (pinfunction "2_2") (pintype "passive"))
      (node (ref "R73") (pin "1") (pinfunction "1_1") (pintype "passive"))
    )
    (net (code "53") (name "FB2") (class "Default")
      (node (ref "IC36") (pin "4") (pinfunction "VSENSE_4") (pintype "bidirectional"))
      (node (ref "R116") (pin "2") (pinfunction "2_2") (pintype "passive"))
      (node (ref "R118") (pin "1") (pinfunction "1_1") (pintype "passive"))
    )
    (net (code "54") (name "GND") (class "Default")
      (node (ref "C1") (pin "2") (pinfunction "2_2") (pintype "passive"))
      (node (ref "C10") (pin "2") (pinfunction "2_2") (pintype "bidirectional"))
      (node (ref "C100") (pin "1") (pinfunction "1_1") (pintype "bidirectional"))
      (node (ref "C101") (pin "2") (pinfunction "2_2") (pintype "bidirectional"))
      (node (ref "C102") (pin "2") (pinfunction "2_2") (pintype "bidirectional"))
      (node (ref "C103") (pin "2") (pinfunction "2_2") (pintype "bidirectional"))
      (node (ref "C104") (pin "2") (pinfunction "2_2") (pintype "bidirectional"))
      (node (ref "C105") (pin "2") (pinfunction "2_2") (pintype "bidirectional"))
      (node (ref "C106") (pin "1") (pinfunction "1_1") (pintype "bidirectional"))
      (node (ref "C11") (pin "2") (pinfunction "2_2") (pintype "passive"))
      (node (ref "C110") (pin "2") (pinfunction "2_2") (pintype "passive"))
      (node (ref "C111") (pin "1") (pinfunction "1_1") (pintype "passive"))
      (node (ref "C114") (pin "2") (pinfunction "2_2") (pintype "bidirectional"))
      (node (ref "C115") (pin "2") (pinfunction "2_2") (pintype "bidirectional"))
      (node (ref "C116") (pin "2") (pinfunction "2_2") (pintype "bidirectional"))
      (node (ref "C117") (pin "2") (pinfunction "2_2") (pintype "bidirectional"))
      (node (ref "C118") (pin "2") (pinfunction "2_2") (pintype "bidirectional"))
      (node (ref "C12") (pin "2") (pinfunction "2_2") (pintype "passive"))
      (node (ref "C121") (pin "2") (pinfunction "2_2") (pintype "bidirectional"))
      (node (ref "C125") (pin "A") (pinfunction "+_A") (pintype "passive"))
      (node (ref "C13") (pin "2") (pinfunction "2_2") (pintype "bidirectional"))
      (node (ref "C14") (pin "2") (pinfunction "2_2") (pintype "bidirectional"))
      (node (ref "C15") (pin "2") (pinfunction "2_2") (pintype "bidirectional"))
      (node (ref "C16") (pin "2") (pinfunction "2_2") (pintype "bidirectional"))
      (node (ref "C17") (pin "1") (pinfunction "1_1") (pintype "bidirectional"))
      (node (ref "C18") (pin "1") (pinfunction "1_1") (pintype "bidirectional"))
      (node (ref "C19") (pin "1") (pinfunction "1_1") (pintype "bidirectional"))
      (node (ref "C2") (pin "-") (pinfunction "-_-") (pintype "passive"))
      (node (ref "C20") (pin "1") (pinfunction "1_1") (pintype "bidirectional"))
      (node (ref "C21") (pin "2") (pinfunction "2_2") (pintype "bidirectional"))
      (node (ref "C22") (pin "2") (pinfunction "2_2") (pintype "bidirectional"))
      (node (ref "C23") (pin "2") (pinfunction "2_2") (pintype "bidirectional"))
      (node (ref "C24") (pin "2") (pinfunction "2_2") (pintype "bidirectional"))
      (node (ref "C25") (pin "2") (pinfunction "2_2") (pintype "bidirectional"))
      (node (ref "C26") (pin "2") (pinfunction "2_2") (pintype "bidirectional"))
      (node (ref "C27") (pin "2") (pinfunction "2_2") (pintype "bidirectional"))
      (node (ref "C28") (pin "2") (pinfunction "2_2") (pintype "bidirectional"))
      (node (ref "C29") (pin "2") (pinfunction "2_2") (pintype "bidirectional"))
      (node (ref "C3") (pin "2") (pinfunction "2_2") (pintype "bidirectional"))
      (node (ref "C30") (pin "2") (pinfunction "2_2") (pintype "bidirectional"))
      (node (ref "C31") (pin "2") (pinfunction "2_2") (pintype "bidirectional"))
      (node (ref "C32") (pin "2") (pinfunction "2_2") (pintype "bidirectional"))
      (node (ref "C33") (pin "2") (pinfunction "2_2") (pintype "bidirectional"))
      (node (ref "C34") (pin "2") (pinfunction "2_2") (pintype "passive"))
      (node (ref "C35") (pin "2") (pinfunction "2_2") (pintype "bidirectional"))
      (node (ref "C36") (pin "2") (pinfunction "2_2") (pintype "bidirectional"))
      (node (ref "C37") (pin "2") (pinfunction "2_2") (pintype "bidirectional"))
      (node (ref "C38") (pin "2") (pinfunction "2_2") (pintype "passive"))
      (node (ref "C39") (pin "1") (pinfunction "1_1") (pintype "passive"))
      (node (ref "C4") (pin "2") (pinfunction "2_2") (pintype "bidirectional"))
      (node (ref "C40") (pin "+") (pinfunction "+_+") (pintype "passive"))
      (node (ref "C41") (pin "1") (pinfunction "1_1") (pintype "passive"))
      (node (ref "C42") (pin "2") (pinfunction "2_2") (pintype "bidirectional"))
      (node (ref "C43") (pin "2") (pinfunction "2_2") (pintype "bidirectional"))
      (node (ref "C44") (pin "1") (pinfunction "1_1") (pintype "bidirectional"))
      (node (ref "C45") (pin "1") (pinfunction "1_1") (pintype "bidirectional"))
      (node (ref "C46") (pin "1") (pinfunction "1_1") (pintype "bidirectional"))
      (node (ref "C47") (pin "2") (pinfunction "2_2") (pintype "bidirectional"))
      (node (ref "C48") (pin "2") (pinfunction "2_2") (pintype "bidirectional"))
      (node (ref "C49") (pin "2") (pinfunction "2_2") (pintype "bidirectional"))
      (node (ref "C5") (pin "2") (pinfunction "2_2") (pintype "bidirectional"))
      (node (ref "C50") (pin "2") (pinfunction "2_2") (pintype "bidirectional"))
      (node (ref "C51") (pin "2") (pinfunction "2_2") (pintype "bidirectional"))
      (node (ref "C52") (pin "2") (pinfunction "2_2") (pintype "bidirectional"))
      (node (ref "C53") (pin "2") (pinfunction "2_2") (pintype "bidirectional"))
      (node (ref "C54") (pin "2") (pinfunction "2_2") (pintype "bidirectional"))
      (node (ref "C55") (pin "2") (pinfunction "2_2") (pintype "bidirectional"))
      (node (ref "C56") (pin "1") (pinfunction "1_1") (pintype "bidirectional"))
      (node (ref "C57") (pin "1") (pinfunction "1_1") (pintype "bidirectional"))
      (node (ref "C58") (pin "1") (pinfunction "1_1") (pintype "bidirectional"))
      (node (ref "C59") (pin "1") (pinfunction "1_1") (pintype "bidirectional"))
      (node (ref "C6") (pin "2") (pinfunction "2_2") (pintype "bidirectional"))
      (node (ref "C60") (pin "2") (pinfunction "2_2") (pintype "bidirectional"))
      (node (ref "C61") (pin "2") (pinfunction "2_2") (pintype "bidirectional"))
      (node (ref "C62") (pin "2") (pinfunction "2_2") (pintype "bidirectional"))
      (node (ref "C63") (pin "2") (pinfunction "2_2") (pintype "bidirectional"))
      (node (ref "C64") (pin "2") (pinfunction "2_2") (pintype "passive"))
      (node (ref "C65") (pin "2") (pinfunction "2_2") (pintype "bidirectional"))
      (node (ref "C66") (pin "2") (pinfunction "2_2") (pintype "bidirectional"))
      (node (ref "C67") (pin "2") (pinfunction "2_2") (pintype "bidirectional"))
      (node (ref "C68") (pin "2") (pinfunction "2_2") (pintype "bidirectional"))
      (node (ref "C69") (pin "2") (pinfunction "2_2") (pintype "bidirectional"))
      (node (ref "C7") (pin "2") (pinfunction "2_2") (pintype "bidirectional"))
      (node (ref "C70") (pin "2") (pinfunction "2_2") (pintype "bidirectional"))
      (node (ref "C71") (pin "2") (pinfunction "2_2") (pintype "bidirectional"))
      (node (ref "C72") (pin "2") (pinfunction "2_2") (pintype "bidirectional"))
      (node (ref "C73") (pin "2") (pinfunction "2_2") (pintype "bidirectional"))
      (node (ref "C74") (pin "2") (pinfunction "2_2") (pintype "bidirectional"))
      (node (ref "C75") (pin "2") (pinfunction "2_2") (pintype "bidirectional"))
      (node (ref "C76") (pin "2") (pinfunction "2_2") (pintype "bidirectional"))
      (node (ref "C77") (pin "2") (pinfunction "2_2") (pintype "passive"))
      (node (ref "C78") (pin "2") (pinfunction "2_2") (pintype "bidirectional"))
      (node (ref "C79") (pin "2") (pinfunction "2_2") (pintype "bidirectional"))
      (node (ref "C8") (pin "2") (pinfunction "2_2") (pintype "passive"))
      (node (ref "C80") (pin "2") (pinfunction "2_2") (pintype "passive"))
      (node (ref "C81") (pin "2") (pinfunction "2_2") (pintype "bidirectional"))
      (node (ref "C82") (pin "2") (pinfunction "2_2") (pintype "bidirectional"))
      (node (ref "C83") (pin "2") (pinfunction "2_2") (pintype "bidirectional"))
      (node (ref "C84") (pin "2") (pinfunction "2_2") (pintype "bidirectional"))
      (node (ref "C85") (pin "2") (pinfunction "2_2") (pintype "bidirectional"))
      (node (ref "C86") (pin "2") (pinfunction "2_2") (pintype "bidirectional"))
      (node (ref "C87") (pin "2") (pinfunction "2_2") (pintype "bidirectional"))
      (node (ref "C88") (pin "2") (pinfunction "2_2") (pintype "bidirectional"))
      (node (ref "C89") (pin "2") (pinfunction "2_2") (pintype "bidirectional"))
      (node (ref "C9") (pin "2") (pinfunction "2_2") (pintype "bidirectional"))
      (node (ref "C90") (pin "2") (pinfunction "2_2") (pintype "bidirectional"))
      (node (ref "C91") (pin "2") (pinfunction "2_2") (pintype "bidirectional"))
      (node (ref "C92") (pin "2") (pinfunction "2_2") (pintype "bidirectional"))
      (node (ref "C93") (pin "2") (pinfunction "2_2") (pintype "bidirectional"))
      (node (ref "C94") (pin "2") (pinfunction "2_2") (pintype "bidirectional"))
      (node (ref "C95") (pin "2") (pinfunction "2_2") (pintype "bidirectional"))
      (node (ref "C96") (pin "2") (pinfunction "2_2") (pintype "bidirectional"))
      (node (ref "C97") (pin "2") (pinfunction "2_2") (pintype "bidirectional"))
      (node (ref "C98") (pin "2") (pinfunction "2_2") (pintype "bidirectional"))
      (node (ref "C99") (pin "1") (pinfunction "1_1") (pintype "bidirectional"))
      (node (ref "D1") (pin "A") (pinfunction "A_A") (pintype "passive"))
      (node (ref "IC10") (pin "3") (pinfunction "+IN_3") (pintype "input"))
      (node (ref "IC10") (pin "5") (pinfunction "+IN_5") (pintype "input"))
      (node (ref "IC11") (pin "3") (pinfunction "GND_3") (pintype "passive"))
      (node (ref "IC12") (pin "4") (pinfunction "GND_4") (pintype "bidirectional"))
      (node (ref "IC13") (pin "4") (pinfunction "GND_4") (pintype "bidirectional"))
      (node (ref "IC14") (pin "8") (pinfunction "VCC_8") (pintype "bidirectional"))
      (node (ref "IC15") (pin "8") (pinfunction "VCC_8") (pintype "bidirectional"))
      (node (ref "IC16") (pin "14") (pinfunction "GND_14") (pintype "bidirectional"))
      (node (ref "IC16") (pin "2") (pinfunction "ADDR0_2") (pintype "bidirectional"))
      (node (ref "IC17") (pin "1") (pinfunction "1A_1") (pintype "bidirectional"))
      (node (ref "IC17") (pin "4") (pinfunction "GND_4") (pintype "bidirectional"))
      (node (ref "IC17") (pin "5") (pinfunction "2A_5") (pintype "bidirectional"))
      (node (ref "IC18") (pin "1") (pinfunction "1A_1") (pintype "bidirectional"))
      (node (ref "IC18") (pin "4") (pinfunction "GND_4") (pintype "bidirectional"))
      (node (ref "IC18") (pin "5") (pinfunction "2A_5") (pintype "bidirectional"))
      (node (ref "IC19") (pin "1") (pinfunction "1A_1") (pintype "bidirectional"))
      (node (ref "IC19") (pin "5") (pinfunction "2A_5") (pintype "bidirectional"))
      (node (ref "IC19") (pin "8") (pinfunction "VCC_8") (pintype "bidirectional"))
      (node (ref "IC2") (pin "14") (pinfunction "GND_14") (pintype "bidirectional"))
      (node (ref "IC20") (pin "1") (pinfunction "1A_1") (pintype "bidirectional"))
      (node (ref "IC20") (pin "5") (pinfunction "2A_5") (pintype "bidirectional"))
      (node (ref "IC20") (pin "8") (pinfunction "VCC_8") (pintype "bidirectional"))
      (node (ref "IC21") (pin "2") (pinfunction "GND_2") (pintype "bidirectional"))
      (node (ref "IC22") (pin "5") (pinfunction "VCC_5") (pintype "bidirectional"))
      (node (ref "IC23") (pin "2") (pinfunction "GND_2") (pintype "bidirectional"))
      (node (ref "IC24") (pin "5") (pinfunction "VCC_5") (pintype "bidirectional"))
      (node (ref "IC25") (pin "1") (pinfunction "GROUND_1") (pintype "bidirectional"))
      (node (ref "IC26") (pin "1") (pinfunction "GND_1") (pintype "power_in"))
      (node (ref "IC27") (pin "3") (pinfunction "+IN_3") (pintype "input"))
      (node (ref "IC27") (pin "5") (pinfunction "+IN_5") (pintype "input"))
      (node (ref "IC28") (pin "8") (pinfunction "VCC_8") (pintype "bidirectional"))
      (node (ref "IC30") (pin "4") (pinfunction "GND_4") (pintype "bidirectional"))
      (node (ref "IC31") (pin "1") (pinfunction "1A_1") (pintype "bidirectional"))
      (node (ref "IC31") (pin "4") (pinfunction "GND_4") (pintype "bidirectional"))
      (node (ref "IC31") (pin "5") (pinfunction "2A_5") (pintype "bidirectional"))
      (node (ref "IC32") (pin "1") (pinfunction "1A_1") (pintype "bidirectional"))
      (node (ref "IC32") (pin "5") (pinfunction "2A_5") (pintype "bidirectional"))
      (node (ref "IC32") (pin "8") (pinfunction "VCC_8") (pintype "bidirectional"))
      (node (ref "IC34") (pin "2") (pinfunction "GND_2") (pintype "bidirectional"))
      (node (ref "IC35") (pin "5") (pinfunction "VCC_5") (pintype "bidirectional"))
      (node (ref "IC37") (pin "6") (pinfunction "GND_6") (pintype "bidirectional"))
      (node (ref "IC37") (pin "9") (pinfunction "EP_9") (pintype "bidirectional"))
      (node (ref "IC7") (pin "5") (pinfunction "VL_5") (pintype "bidirectional"))
      (node (ref "IC8") (pin "3") (pinfunction "+IN_3") (pintype "input"))
      (node (ref "IC8") (pin "5") (pinfunction "+IN_5") (pintype "input"))
      (node (ref "IC9") (pin "3") (pinfunction "+IN_3") (pintype "input"))
      (node (ref "IC9") (pin "5") (pinfunction "+IN_5") (pintype "input"))
      (node (ref "IO_C10") (pin "2") (pinfunction "2_2") (pintype "passive"))
      (node (ref "IO_C10") (pin "3") (pinfunction "2_3") (pintype "passive"))
      (node (ref "IO_C10") (pin "4") (pinfunction "2_4") (pintype "passive"))
      (node (ref "IO_C10") (pin "5") (pinfunction "2_5") (pintype "passive"))
      (node (ref "IO_H34") (pin "2") (pinfunction "2_2") (pintype "passive"))
      (node (ref "IO_H34") (pin "3") (pinfunction "2_3") (pintype "passive"))
      (node (ref "IO_H34") (pin "4") (pinfunction "2_4") (pintype "passive"))
      (node (ref "IO_H34") (pin "5") (pinfunction "2_5") (pintype "passive"))
      (node (ref "IO_H4") (pin "2") (pinfunction "2_2") (pintype "passive"))
      (node (ref "IO_H4") (pin "3") (pinfunction "2_3") (pintype "passive"))
      (node (ref "IO_H4") (pin "4") (pinfunction "2_4") (pintype "passive"))
      (node (ref "IO_H4") (pin "5") (pinfunction "2_5") (pintype "passive"))
      (node (ref "IO_H5") (pin "2") (pinfunction "2_2") (pintype "passive"))
      (node (ref "IO_H5") (pin "3") (pinfunction "2_3") (pintype "passive"))
      (node (ref "IO_H5") (pin "4") (pinfunction "2_4") (pintype "passive"))
      (node (ref "IO_H5") (pin "5") (pinfunction "2_5") (pintype "passive"))
      (node (ref "J1") (pin "2") (pinfunction "P$2_2") (pintype "bidirectional"))
      (node (ref "J1") (pin "4") (pinfunction "P$4_4") (pintype "bidirectional"))
      (node (ref "J13") (pin "1") (pinfunction "P$1_1") (pintype "bidirectional"))
      (node (ref "J13") (pin "2") (pinfunction "P$2_2") (pintype "bidirectional"))
      (node (ref "J13") (pin "3") (pinfunction "P$3_3") (pintype "bidirectional"))
      (node (ref "J2") (pin "C1") (pinfunction "C1_C1") (pintype "bidirectional"))
      (node (ref "J2") (pin "C12") (pinfunction "C12_C12") (pintype "bidirectional"))
      (node (ref "J2") (pin "C13") (pinfunction "C13_C13") (pintype "bidirectional"))
      (node (ref "J2") (pin "C16") (pinfunction "C16_C16") (pintype "bidirectional"))
      (node (ref "J2") (pin "C17") (pinfunction "C17_C17") (pintype "bidirectional"))
      (node (ref "J2") (pin "C20") (pinfunction "C20_C20") (pintype "bidirectional"))
      (node (ref "J2") (pin "C21") (pinfunction "C21_C21") (pintype "bidirectional"))
      (node (ref "J2") (pin "C24") (pinfunction "C24_C24") (pintype "bidirectional"))
      (node (ref "J2") (pin "C25") (pinfunction "C25_C25") (pintype "bidirectional"))
      (node (ref "J2") (pin "C28") (pinfunction "C28_C28") (pintype "bidirectional"))
      (node (ref "J2") (pin "C29") (pinfunction "C29_C29") (pintype "bidirectional"))
      (node (ref "J2") (pin "C32") (pinfunction "C32_C32") (pintype "bidirectional"))
      (node (ref "J2") (pin "C33") (pinfunction "C33_C33") (pintype "bidirectional"))
      (node (ref "J2") (pin "C36") (pinfunction "C36_C36") (pintype "bidirectional"))
      (node (ref "J2") (pin "C38") (pinfunction "C38_C38") (pintype "bidirectional"))
      (node (ref "J2") (pin "C4") (pinfunction "C4_C4") (pintype "bidirectional"))
      (node (ref "J2") (pin "C40") (pinfunction "C40_C40") (pintype "bidirectional"))
      (node (ref "J2") (pin "C5") (pinfunction "C5_C5") (pintype "bidirectional"))
      (node (ref "J2") (pin "C8") (pinfunction "C8_C8") (pintype "bidirectional"))
      (node (ref "J2") (pin "C9") (pinfunction "C9_C9") (pintype "bidirectional"))
      (node (ref "J2") (pin "D2") (pinfunction "D2_D2") (pintype "bidirectional"))
      (node (ref "J2") (pin "D3") (pinfunction "D3_D3") (pintype "bidirectional"))
      (node (ref "J2") (pin "D37") (pinfunction "D37_D37") (pintype "bidirectional"))
      (node (ref "J2") (pin "D39") (pinfunction "D39_D39") (pintype "bidirectional"))
      (node (ref "J2") (pin "D6") (pinfunction "D6_D6") (pintype "bidirectional"))
      (node (ref "J2") (pin "D7") (pinfunction "D7_D7") (pintype "bidirectional"))
      (node (ref "J2") (pin "G38") (pinfunction "G38_G38") (pintype "bidirectional"))
      (node (ref "J2") (pin "G40") (pinfunction "G40_G40") (pintype "bidirectional"))
      (node (ref "J2") (pin "H12") (pinfunction "H12_H12") (pintype "bidirectional"))
      (node (ref "J2") (pin "H15") (pinfunction "H15_H15") (pintype "bidirectional"))
      (node (ref "J2") (pin "H18") (pinfunction "H18_H18") (pintype "bidirectional"))
      (node (ref "J2") (pin "H21") (pinfunction "H21_H21") (pintype "bidirectional"))
      (node (ref "J2") (pin "H24") (pinfunction "H24_H24") (pintype "bidirectional"))
      (node (ref "J2") (pin "H27") (pinfunction "H27_H27") (pintype "bidirectional"))
      (node (ref "J2") (pin "H3") (pinfunction "H3_H3") (pintype "bidirectional"))
      (node (ref "J2") (pin "H30") (pinfunction "H30_H30") (pintype "bidirectional"))
      (node (ref "J2") (pin "H33") (pinfunction "H33_H33") (pintype "bidirectional"))
      (node (ref "J2") (pin "H36") (pinfunction "H36_H36") (pintype "bidirectional"))
      (node (ref "J2") (pin "H39") (pinfunction "H39_H39") (pintype "bidirectional"))
      (node (ref "J2") (pin "H6") (pinfunction "H6_H6") (pintype "bidirectional"))
      (node (ref "J2") (pin "H9") (pinfunction "H9_H9") (pintype "bidirectional"))
      (node (ref "J3") (pin "8") (pinfunction "8_8") (pintype "bidirectional"))
      (node (ref "J4") (pin "2") (pinfunction "P$2_2") (pintype "bidirectional"))
      (node (ref "J4") (pin "4") (pinfunction "P$4_4") (pintype "bidirectional"))
      (node (ref "J5") (pin "4") (pinfunction "P$4_4") (pintype "bidirectional"))
      (node (ref "L4") (pin "2") (pinfunction "2_2") (pintype "passive"))
      (node (ref "OPIN") (pin "2") (pinfunction "2_2") (pintype "passive"))
      (node (ref "OPIN") (pin "3") (pinfunction "2_3") (pintype "passive"))
      (node (ref "OPIN") (pin "4") (pinfunction "2_4") (pintype "passive"))
      (node (ref "OPIN") (pin "5") (pinfunction "2_5") (pintype "passive"))
      (node (ref "OPOUT2") (pin "2") (pinfunction "2_2") (pintype "passive"))
      (node (ref "OPOUT2") (pin "3") (pinfunction "2_3") (pintype "passive"))
      (node (ref "OPOUT2") (pin "4") (pinfunction "2_4") (pintype "passive"))
      (node (ref "OPOUT2") (pin "5") (pinfunction "2_5") (pintype "passive"))
      (node (ref "PULSESOUT") (pin "2") (pinfunction "2_2") (pintype "passive"))
      (node (ref "PULSESOUT") (pin "3") (pinfunction "2_3") (pintype "passive"))
      (node (ref "PULSESOUT") (pin "4") (pinfunction "2_4") (pintype "passive"))
      (node (ref "PULSESOUT") (pin "5") (pinfunction "2_5") (pintype "passive"))
      (node (ref "PULSESOUT2") (pin "2") (pinfunction "2_2") (pintype "passive"))
      (node (ref "PULSESOUT2") (pin "3") (pinfunction "2_3") (pintype "passive"))
      (node (ref "PULSESOUT2") (pin "4") (pinfunction "2_4") (pintype "passive"))
      (node (ref "PULSESOUT2") (pin "5") (pinfunction "2_5") (pintype "passive"))
      (node (ref "R10") (pin "1") (pinfunction "1_1") (pintype "passive"))
      (node (ref "R104") (pin "2") (pinfunction "2_2") (pintype "passive"))
      (node (ref "R108") (pin "1") (pinfunction "1_1") (pintype "passive"))
      (node (ref "R109") (pin "2") (pinfunction "2_2") (pintype "passive"))
      (node (ref "R110") (pin "2") (pinfunction "2_2") (pintype "passive"))
      (node (ref "R118") (pin "2") (pinfunction "2_2") (pintype "passive"))
      (node (ref "R13") (pin "2") (pinfunction "2_2") (pintype "passive"))
      (node (ref "R15") (pin "1") (pinfunction "1_1") (pintype "passive"))
      (node (ref "R16") (pin "1") (pinfunction "1_1") (pintype "passive"))
      (node (ref "R19") (pin "1") (pinfunction "1_1") (pintype "passive"))
      (node (ref "R24") (pin "2") (pinfunction "2_2") (pintype "passive"))
      (node (ref "R26") (pin "1") (pinfunction "1_1") (pintype "passive"))
      (node (ref "R3") (pin "2") (pinfunction "2_2") (pintype "passive"))
      (node (ref "R30") (pin "1") (pinfunction "1_1") (pintype "passive"))
      (node (ref "R4") (pin "1") (pinfunction "1_1") (pintype "passive"))
      (node (ref "R42") (pin "2") (pinfunction "2_2") (pintype "passive"))
      (node (ref "R43") (pin "2") (pinfunction "2_2") (pintype "passive"))
      (node (ref "R5") (pin "1") (pinfunction "1_1") (pintype "passive"))
      (node (ref "R52") (pin "1") (pinfunction "1_1") (pintype "passive"))
      (node (ref "R70") (pin "2") (pinfunction "2_2") (pintype "passive"))
      (node (ref "R80") (pin "2") (pinfunction "2_2") (pintype "passive"))
      (node (ref "R81") (pin "2") (pinfunction "2_2") (pintype "passive"))
      (node (ref "R82") (pin "2") (pinfunction "2_2") (pintype "passive"))
      (node (ref "R83") (pin "2") (pinfunction "2_2") (pintype "passive"))
      (node (ref "R84") (pin "1") (pinfunction "1_1") (pintype "passive"))
      (node (ref "SV1") (pin "12") (pinfunction "12_12") (pintype "passive"))
      (node (ref "SV1") (pin "15") (pinfunction "15_15") (pintype "passive"))
      (node (ref "SV1") (pin "18") (pinfunction "18_18") (pintype "passive"))
      (node (ref "SV1") (pin "3") (pinfunction "3_3") (pintype "passive"))
      (node (ref "SV1") (pin "6") (pinfunction "6_6") (pintype "passive"))
      (node (ref "SV1") (pin "9") (pinfunction "9_9") (pintype "passive"))
      (node (ref "SV2") (pin "12") (pinfunction "12_12") (pintype "passive"))
      (node (ref "SV2") (pin "15") (pinfunction "15_15") (pintype "passive"))
      (node (ref "SV2") (pin "18") (pinfunction "18_18") (pintype "passive"))
      (node (ref "SV2") (pin "3") (pinfunction "3_3") (pintype "passive"))
      (node (ref "SV2") (pin "6") (pinfunction "6_6") (pintype "passive"))
      (node (ref "SV2") (pin "9") (pinfunction "9_9") (pintype "passive"))
    )
    (net (code "55") (name "H4") (class "Default")
      (node (ref "IO_H4") (pin "1") (pinfunction "1_1") (pintype "passive"))
      (node (ref "J2") (pin "H4") (pinfunction "H4_H4") (pintype "bidirectional"))
      (node (ref "R15") (pin "2") (pinfunction "2_2") (pintype "passive"))
    )
    (net (code "56") (name "H5") (class "Default")
      (node (ref "IO_H5") (pin "1") (pinfunction "1_1") (pintype "passive"))
      (node (ref "J2") (pin "H5") (pinfunction "H5_H5") (pintype "bidirectional"))
      (node (ref "R16") (pin "2") (pinfunction "2_2") (pintype "passive"))
    )
    (net (code "57") (name "H13") (class "Default")
      (node (ref "J2") (pin "H13") (pinfunction "H13_H13") (pintype "bidirectional"))
      (node (ref "SV1") (pin "7") (pinfunction "7_7") (pintype "passive"))
    )
    (net (code "58") (name "H14") (class "Default")
      (node (ref "J2") (pin "H14") (pinfunction "H14_H14") (pintype "bidirectional"))
      (node (ref "SV1") (pin "8") (pinfunction "8_8") (pintype "passive"))
    )
    (net (code "59") (name "H16") (class "Default")
      (node (ref "J2") (pin "H16") (pinfunction "H16_H16") (pintype "bidirectional"))
      (node (ref "SV1") (pin "10") (pinfunction "10_10") (pintype "passive"))
    )
    (net (code "60") (name "H17") (class "Default")
      (node (ref "J2") (pin "H17") (pinfunction "H17_H17") (pintype "bidirectional"))
      (node (ref "SV1") (pin "11") (pinfunction "11_11") (pintype "passive"))
    )
    (net (code "61") (name "H19") (class "Default")
      (node (ref "J2") (pin "H19") (pinfunction "H19_H19") (pintype "bidirectional"))
      (node (ref "SV1") (pin "13") (pinfunction "13_13") (pintype "passive"))
    )
    (net (code "62") (name "H20") (class "Default")
      (node (ref "J2") (pin "H20") (pinfunction "H20_H20") (pintype "bidirectional"))
      (node (ref "SV1") (pin "14") (pinfunction "14_14") (pintype "passive"))
    )
    (net (code "63") (name "H22") (class "Default")
      (node (ref "J2") (pin "H22") (pinfunction "H22_H22") (pintype "bidirectional"))
      (node (ref "SV1") (pin "16") (pinfunction "16_16") (pintype "passive"))
    )
    (net (code "64") (name "H23") (class "Default")
      (node (ref "J2") (pin "H23") (pinfunction "H23_H23") (pintype "bidirectional"))
      (node (ref "SV1") (pin "17") (pinfunction "17_17") (pintype "passive"))
    )
    (net (code "65") (name "H25") (class "Default")
      (node (ref "J2") (pin "H25") (pinfunction "H25_H25") (pintype "bidirectional"))
      (node (ref "SV1") (pin "19") (pinfunction "19_19") (pintype "passive"))
    )
    (net (code "66") (name "H26") (class "Default")
      (node (ref "J2") (pin "H26") (pinfunction "H26_H26") (pintype "bidirectional"))
      (node (ref "SV1") (pin "20") (pinfunction "20_20") (pintype "passive"))
    )
    (net (code "67") (name "H28") (class "Default")
      (node (ref "J2") (pin "H28") (pinfunction "H28_H28") (pintype "bidirectional"))
      (node (ref "SV2") (pin "1") (pinfunction "1_1") (pintype "passive"))
    )
    (net (code "68") (name "H29") (class "Default")
      (node (ref "J2") (pin "H29") (pinfunction "H29_H29") (pintype "bidirectional"))
      (node (ref "SV2") (pin "2") (pinfunction "2_2") (pintype "passive"))
    )
    (net (code "69") (name "H31") (class "Default")
      (node (ref "J2") (pin "H31") (pinfunction "H31_H31") (pintype "bidirectional"))
      (node (ref "SV2") (pin "4") (pinfunction "4_4") (pintype "passive"))
    )
    (net (code "70") (name "H32") (class "Default")
      (node (ref "J2") (pin "H32") (pinfunction "H32_H32") (pintype "bidirectional"))
      (node (ref "SV2") (pin "5") (pinfunction "5_5") (pintype "passive"))
    )
    (net (code "71") (name "H34") (class "Default")
      (node (ref "IO_H34") (pin "1") (pinfunction "1_1") (pintype "passive"))
      (node (ref "J2") (pin "H34") (pinfunction "H34_H34") (pintype "bidirectional"))
      (node (ref "R21") (pin "2") (pinfunction "2_2") (pintype "passive"))
      (node (ref "R5") (pin "2") (pinfunction "2_2") (pintype "passive"))
      (node (ref "R80") (pin "1") (pinfunction "1_1") (pintype "passive"))
      (node (ref "SV2") (pin "7") (pinfunction "7_7") (pintype "passive"))
    )
    (net (code "72") (name "H34I") (class "Default")
      (node (ref "IC14") (pin "7") (pinfunction "1C_7") (pintype "bidirectional"))
      (node (ref "IC22") (pin "1") (pinfunction "1A_1") (pintype "bidirectional"))
      (node (ref "IC3") (pin "1") (pinfunction "OUTA_1") (pintype "bidirectional"))
      (node (ref "R23") (pin "1") (pinfunction "1_1") (pintype "passive"))
    )
    (net (code "73") (name "H34N") (class "Default")
      (node (ref "IC19") (pin "7") (pinfunction "1C_7") (pintype "bidirectional"))
      (node (ref "IC22") (pin "6") (pinfunction "1Y_6") (pintype "bidirectional"))
    )
    (net (code "74") (name "H35") (class "Default")
      (node (ref "J2") (pin "H35") (pinfunction "H35_H35") (pintype "bidirectional"))
      (node (ref "R27") (pin "1") (pinfunction "1_1") (pintype "passive"))
      (node (ref "R81") (pin "1") (pinfunction "1_1") (pintype "passive"))
      (node (ref "SV2") (pin "8") (pinfunction "8_8") (pintype "passive"))
    )
    (net (code "75") (name "H35I") (class "Default")
      (node (ref "IC14") (pin "3") (pinfunction "2C_3") (pintype "bidirectional"))
      (node (ref "IC22") (pin "3") (pinfunction "2A_3") (pintype "bidirectional"))
      (node (ref "IC3") (pin "7") (pinfunction "OUTB_7") (pintype "bidirectional"))
      (node (ref "R29") (pin "2") (pinfunction "2_2") (pintype "passive"))
    )
    (net (code "76") (name "H35N") (class "Default")
      (node (ref "IC19") (pin "3") (pinfunction "2C_3") (pintype "bidirectional"))
      (node (ref "IC22") (pin "4") (pinfunction "2Y_4") (pintype "bidirectional"))
    )
    (net (code "77") (name "H37") (class "Default")
      (node (ref "J2") (pin "H37") (pinfunction "H37_H37") (pintype "bidirectional"))
      (node (ref "R37") (pin "2") (pinfunction "2_2") (pintype "passive"))
      (node (ref "R83") (pin "1") (pinfunction "1_1") (pintype "passive"))
      (node (ref "SV2") (pin "10") (pinfunction "10_10") (pintype "passive"))
    )
    (net (code "78") (name "H37I") (class "Default")
      (node (ref "IC15") (pin "7") (pinfunction "1C_7") (pintype "bidirectional"))
      (node (ref "IC24") (pin "1") (pinfunction "1A_1") (pintype "bidirectional"))
      (node (ref "IC5") (pin "1") (pinfunction "OUTA_1") (pintype "bidirectional"))
      (node (ref "R41") (pin "1") (pinfunction "1_1") (pintype "passive"))
    )
    (net (code "79") (name "H37N") (class "Default")
      (node (ref "IC20") (pin "7") (pinfunction "1C_7") (pintype "bidirectional"))
      (node (ref "IC24") (pin "6") (pinfunction "1Y_6") (pintype "bidirectional"))
    )
    (net (code "80") (name "H38") (class "Default")
      (node (ref "J2") (pin "H38") (pinfunction "H38_H38") (pintype "bidirectional"))
      (node (ref "R44") (pin "1") (pinfunction "1_1") (pintype "passive"))
      (node (ref "R82") (pin "1") (pinfunction "1_1") (pintype "passive"))
      (node (ref "SV2") (pin "11") (pinfunction "11_11") (pintype "passive"))
    )
    (net (code "81") (name "H38I") (class "Default")
      (node (ref "IC15") (pin "3") (pinfunction "2C_3") (pintype "bidirectional"))
      (node (ref "IC24") (pin "3") (pinfunction "2A_3") (pintype "bidirectional"))
      (node (ref "IC5") (pin "7") (pinfunction "OUTB_7") (pintype "bidirectional"))
      (node (ref "R46") (pin "2") (pinfunction "2_2") (pintype "passive"))
    )
    (net (code "82") (name "H38N") (class "Default")
      (node (ref "IC20") (pin "3") (pinfunction "2C_3") (pintype "bidirectional"))
      (node (ref "IC24") (pin "4") (pinfunction "2Y_4") (pintype "bidirectional"))
    )
    (net (code "83") (name "IO1") (class "Default")
      (node (ref "OPIN") (pin "1") (pinfunction "1_1") (pintype "passive"))
      (node (ref "R2") (pin "2") (pinfunction "2_2") (pintype "passive"))
      (node (ref "R42") (pin "1") (pinfunction "1_1") (pintype "passive"))
      (node (ref "R9") (pin "1") (pinfunction "1_1") (pintype "passive"))
    )
    (net (code "84") (name "Net-(C108-Pad2)") (class "Default")
      (node (ref "C108") (pin "2") (pinfunction "2_2") (pintype "passive"))
      (node (ref "C113") (pin "1") (pinfunction "1_1") (pintype "passive"))
    )
    (net (code "85") (name "Net-(C109-Pad1)") (class "Default")
      (node (ref "C109") (pin "1") (pinfunction "1_1") (pintype "passive"))
      (node (ref "C112") (pin "2") (pinfunction "2_2") (pintype "passive"))
    )
    (net (code "86") (name "Net-(IC1-NONINVERTING_INPUT)") (class "Default")
      (node (ref "IC1") (pin "3") (pinfunction "NONINVERTING_INPUT_3") (pintype "bidirectional"))
      (node (ref "R3") (pin "1") (pinfunction "1_1") (pintype "passive"))
    )
    (net (code "87") (name "Net-(IC2-VOUTA)") (class "Default")
      (node (ref "IC2") (pin "4") (pinfunction "VOUTA_4") (pintype "bidirectional"))
      (node (ref "R47") (pin "1") (pinfunction "1_1") (pintype "passive"))
    )
    (net (code "88") (name "Net-(IC2-VOUTB)") (class "Default")
      (node (ref "IC2") (pin "13") (pinfunction "VOUTB_13") (pintype "bidirectional"))
      (node (ref "R56") (pin "2") (pinfunction "2_2") (pintype "passive"))
    )
    (net (code "89") (name "Net-(IC2-VOUTC)") (class "Default")
      (node (ref "IC2") (pin "5") (pinfunction "VOUTC_5") (pintype "bidirectional"))
      (node (ref "R53") (pin "1") (pinfunction "1_1") (pintype "passive"))
    )
    (net (code "90") (name "Net-(IC2-VOUTD)") (class "Default")
      (node (ref "IC2") (pin "12") (pinfunction "VOUTD_12") (pintype "bidirectional"))
      (node (ref "R57") (pin "2") (pinfunction "2_2") (pintype "passive"))
    )
    (net (code "91") (name "Net-(IC2-VOUTE)") (class "Default")
      (node (ref "IC2") (pin "6") (pinfunction "VOUTE_6") (pintype "bidirectional"))
      (node (ref "R54") (pin "1") (pinfunction "1_1") (pintype "passive"))
    )
    (net (code "92") (name "Net-(IC2-VOUTF)") (class "Default")
      (node (ref "IC2") (pin "11") (pinfunction "VOUTF_11") (pintype "bidirectional"))
      (node (ref "R58") (pin "2") (pinfunction "2_2") (pintype "passive"))
    )
    (net (code "93") (name "Net-(IC2-VOUTG)") (class "Default")
      (node (ref "IC2") (pin "7") (pinfunction "VOUTG_7") (pintype "bidirectional"))
      (node (ref "R55") (pin "1") (pinfunction "1_1") (pintype "passive"))
    )
    (net (code "94") (name "Net-(IC2-VOUTH)") (class "Default")
      (node (ref "IC2") (pin "10") (pinfunction "VOUTH_10") (pintype "bidirectional"))
      (node (ref "R59") (pin "2") (pinfunction "2_2") (pintype "passive"))
    )
    (net (code "95") (name "Net-(IC3-+INA)") (class "Default")
      (node (ref "IC3") (pin "3") (pinfunction "+INA_3") (pintype "bidirectional"))
      (node (ref "R21") (pin "1") (pinfunction "1_1") (pintype "passive"))
      (node (ref "R22") (pin "1") (pinfunction "1_1") (pintype "passive"))
    )
    (net (code "96") (name "Net-(IC3-+INB)") (class "Default")
      (node (ref "IC3") (pin "5") (pinfunction "+INB_5") (pintype "bidirectional"))
      (node (ref "R27") (pin "2") (pinfunction "2_2") (pintype "passive"))
      (node (ref "R28") (pin "2") (pinfunction "2_2") (pintype "passive"))
    )
    (net (code "97") (name "Net-(IC3--INA)") (class "Default")
      (node (ref "IC3") (pin "2") (pinfunction "-INA_2") (pintype "bidirectional"))
      (node (ref "R23") (pin "2") (pinfunction "2_2") (pintype "passive"))
      (node (ref "R24") (pin "1") (pinfunction "1_1") (pintype "passive"))
    )
    (net (code "98") (name "Net-(IC3--INB)") (class "Default")
      (node (ref "IC3") (pin "6") (pinfunction "-INB_6") (pintype "bidirectional"))
      (node (ref "R29") (pin "1") (pinfunction "1_1") (pintype "passive"))
      (node (ref "R30") (pin "2") (pinfunction "2_2") (pintype "passive"))
    )
    (net (code "99") (name "Net-(IC4-NONINVERTING_INPUT)") (class "Default")
      (node (ref "IC4") (pin "3") (pinfunction "NONINVERTING_INPUT_3") (pintype "bidirectional"))
      (node (ref "R13") (pin "1") (pinfunction "1_1") (pintype "passive"))
    )
    (net (code "100") (name "Net-(IC5-+INA)") (class "Default")
      (node (ref "IC5") (pin "3") (pinfunction "+INA_3") (pintype "bidirectional"))
      (node (ref "R37") (pin "1") (pinfunction "1_1") (pintype "passive"))
      (node (ref "R39") (pin "1") (pinfunction "1_1") (pintype "passive"))
    )
    (net (code "101") (name "Net-(IC5-+INB)") (class "Default")
      (node (ref "IC5") (pin "5") (pinfunction "+INB_5") (pintype "bidirectional"))
      (node (ref "R44") (pin "2") (pinfunction "2_2") (pintype "passive"))
      (node (ref "R45") (pin "2") (pinfunction "2_2") (pintype "passive"))
    )
    (net (code "102") (name "Net-(IC5--INA)") (class "Default")
      (node (ref "IC5") (pin "2") (pinfunction "-INA_2") (pintype "bidirectional"))
      (node (ref "R41") (pin "2") (pinfunction "2_2") (pintype "passive"))
      (node (ref "R43") (pin "1") (pinfunction "1_1") (pintype "passive"))
    )
    (net (code "103") (name "Net-(IC5--INB)") (class "Default")
      (node (ref "IC5") (pin "6") (pinfunction "-INB_6") (pintype "bidirectional"))
      (node (ref "R46") (pin "1") (pinfunction "1_1") (pintype "passive"))
      (node (ref "R52") (pin "2") (pinfunction "2_2") (pintype "passive"))
    )
    (net (code "104") (name "Net-(IC6-INVERTING_INPUT)") (class "Default")
      (node (ref "IC6") (pin "2") (pinfunction "INVERTING_INPUT_2") (pintype "bidirectional"))
      (node (ref "R18") (pin "1") (pinfunction "1_1") (pintype "passive"))
      (node (ref "R19") (pin "2") (pinfunction "2_2") (pintype "passive"))
    )
    (net (code "105") (name "Net-(IC6-NONINVERTING_INPUT)") (class "Default")
      (node (ref "IC6") (pin "3") (pinfunction "NONINVERTING_INPUT_3") (pintype "bidirectional"))
      (node (ref "R20") (pin "1") (pinfunction "1_1") (pintype "passive"))
      (node (ref "R25") (pin "1") (pinfunction "1_1") (pintype "passive"))
      (node (ref "R31") (pin "1") (pinfunction "1_1") (pintype "passive"))
    )
    (net (code "106") (name "Net-(IC7-INVERTING_INPUT)") (class "Default")
      (node (ref "IC7") (pin "2") (pinfunction "INVERTING_INPUT_2") (pintype "bidirectional"))
      (node (ref "R26") (pin "2") (pinfunction "2_2") (pintype "passive"))
      (node (ref "R6") (pin "1") (pinfunction "1_1") (pintype "passive"))
    )
    (net (code "107") (name "Net-(IC8A--IN)") (class "Default")
      (node (ref "IC8") (pin "2") (pinfunction "-IN_2") (pintype "input"))
      (node (ref "R63") (pin "1") (pinfunction "1_1") (pintype "passive"))
      (node (ref "R64") (pin "1") (pinfunction "1_1") (pintype "passive"))
    )
    (net (code "108") (name "Net-(IC8A-OUT)") (class "Default")
      (node (ref "IC8") (pin "1") (pinfunction "OUT_1") (pintype "output"))
      (node (ref "R63") (pin "2") (pinfunction "2_2") (pintype "passive"))
      (node (ref "R74") (pin "2") (pinfunction "2_2") (pintype "passive"))
    )
    (net (code "109") (name "Net-(IC8B--IN)") (class "Default")
      (node (ref "IC8") (pin "6") (pinfunction "-IN_6") (pintype "input"))
      (node (ref "R62") (pin "1") (pinfunction "1_1") (pintype "passive"))
      (node (ref "R65") (pin "1") (pinfunction "1_1") (pintype "passive"))
    )
    (net (code "110") (name "Net-(IC8B-OUT)") (class "Default")
      (node (ref "IC8") (pin "7") (pinfunction "OUT_7") (pintype "output"))
      (node (ref "R62") (pin "2") (pinfunction "2_2") (pintype "passive"))
      (node (ref "R75") (pin "2") (pinfunction "2_2") (pintype "passive"))
    )
    (net (code "111") (name "Net-(IC9A--IN)") (class "Default")
      (node (ref "IC9") (pin "2") (pinfunction "-IN_2") (pintype "input"))
      (node (ref "R67") (pin "1") (pinfunction "1_1") (pintype "passive"))
      (node (ref "R68") (pin "1") (pinfunction "1_1") (pintype "passive"))
    )
    (net (code "112") (name "Net-(IC9A-OUT)") (class "Default")
      (node (ref "IC9") (pin "1") (pinfunction "OUT_1") (pintype "output"))
      (node (ref "R67") (pin "2") (pinfunction "2_2") (pintype "passive"))
      (node (ref "R76") (pin "2") (pinfunction "2_2") (pintype "passive"))
    )
    (net (code "113") (name "Net-(IC9B--IN)") (class "Default")
      (node (ref "IC9") (pin "6") (pinfunction "-IN_6") (pintype "input"))
      (node (ref "R66") (pin "1") (pinfunction "1_1") (pintype "passive"))
      (node (ref "R69") (pin "1") (pinfunction "1_1") (pintype "passive"))
    )
    (net (code "114") (name "Net-(IC9B-OUT)") (class "Default")
      (node (ref "IC9") (pin "7") (pinfunction "OUT_7") (pintype "output"))
      (node (ref "R66") (pin "2") (pinfunction "2_2") (pintype "passive"))
      (node (ref "R77") (pin "2") (pinfunction "2_2") (pintype "passive"))
    )
    (net (code "115") (name "Net-(IC10A--IN)") (class "Default")
      (node (ref "IC10") (pin "2") (pinfunction "-IN_2") (pintype "input"))
      (node (ref "R35") (pin "1") (pinfunction "1_1") (pintype "passive"))
      (node (ref "R61") (pin "1") (pinfunction "1_1") (pintype "passive"))
    )
    (net (code "116") (name "Net-(IC10B--IN)") (class "Default")
      (node (ref "IC10") (pin "6") (pinfunction "-IN_6") (pintype "input"))
      (node (ref "R115") (pin "1") (pinfunction "1_1") (pintype "passive"))
      (node (ref "R17") (pin "1") (pinfunction "1_1") (pintype "passive"))
    )
    (net (code "117") (name "Net-(IC16-VOUTE)") (class "Default")
      (node (ref "IC16") (pin "6") (pinfunction "VOUTE_6") (pintype "bidirectional"))
      (node (ref "R94") (pin "2") (pinfunction "2_2") (pintype "passive"))
    )
    (net (code "118") (name "Net-(IC16-VOUTF)") (class "Default")
      (node (ref "IC16") (pin "11") (pinfunction "VOUTF_11") (pintype "bidirectional"))
      (node (ref "R92") (pin "2") (pinfunction "2_2") (pintype "passive"))
    )
    (net (code "119") (name "Net-(IC16-VOUTG)") (class "Default")
      (node (ref "IC16") (pin "7") (pinfunction "VOUTG_7") (pintype "bidirectional"))
      (node (ref "R95") (pin "2") (pinfunction "2_2") (pintype "passive"))
    )
    (net (code "120") (name "Net-(IC16-VOUTH)") (class "Default")
      (node (ref "IC16") (pin "10") (pinfunction "VOUTH_10") (pintype "bidirectional"))
      (node (ref "R93") (pin "2") (pinfunction "2_2") (pintype "passive"))
    )
    (net (code "121") (name "Net-(IC27A--IN)") (class "Default")
      (node (ref "IC27") (pin "2") (pinfunction "-IN_2") (pintype "input"))
      (node (ref "R97") (pin "1") (pinfunction "1_1") (pintype "passive"))
      (node (ref "R98") (pin "1") (pinfunction "1_1") (pintype "passive"))
    )
    (net (code "122") (name "Net-(IC27A-OUT)") (class "Default")
      (node (ref "IC27") (pin "1") (pinfunction "OUT_1") (pintype "output"))
      (node (ref "R100") (pin "2") (pinfunction "2_2") (pintype "passive"))
      (node (ref "R97") (pin "2") (pinfunction "2_2") (pintype "passive"))
    )
    (net (code "123") (name "Net-(IC27B--IN)") (class "Default")
      (node (ref "IC27") (pin "6") (pinfunction "-IN_6") (pintype "input"))
      (node (ref "R96") (pin "1") (pinfunction "1_1") (pintype "passive"))
      (node (ref "R99") (pin "1") (pinfunction "1_1") (pintype "passive"))
    )
    (net (code "124") (name "Net-(IC27B-OUT)") (class "Default")
      (node (ref "IC27") (pin "7") (pinfunction "OUT_7") (pintype "output"))
      (node (ref "R101") (pin "2") (pinfunction "2_2") (pintype "passive"))
      (node (ref "R96") (pin "2") (pinfunction "2_2") (pintype "passive"))
    )
    (net (code "125") (name "Net-(IC29-ADJUSTMENT)") (class "Default")
      (node (ref "IC29") (pin "1") (pinfunction "ADJUSTMENT_1") (pintype "bidirectional"))
      (node (ref "R14") (pin "2") (pinfunction "2_2") (pintype "passive"))
      (node (ref "R70") (pin "1") (pinfunction "1_1") (pintype "passive"))
    )
    (net (code "126") (name "Net-(IC33-+INA)") (class "Default")
      (node (ref "IC33") (pin "3") (pinfunction "+INA_3") (pintype "bidirectional"))
      (node (ref "R102") (pin "1") (pinfunction "1_1") (pintype "passive"))
      (node (ref "R91") (pin "1") (pinfunction "1_1") (pintype "passive"))
    )
    (net (code "127") (name "Net-(IC33-+INB)") (class "Default")
      (node (ref "IC33") (pin "5") (pinfunction "+INB_5") (pintype "bidirectional"))
      (node (ref "R105") (pin "2") (pinfunction "2_2") (pintype "passive"))
      (node (ref "R106") (pin "2") (pinfunction "2_2") (pintype "passive"))
    )
    (net (code "128") (name "Net-(IC33--INA)") (class "Default")
      (node (ref "IC33") (pin "2") (pinfunction "-INA_2") (pintype "bidirectional"))
      (node (ref "R103") (pin "2") (pinfunction "2_2") (pintype "passive"))
      (node (ref "R104") (pin "1") (pinfunction "1_1") (pintype "passive"))
    )
    (net (code "129") (name "Net-(IC33--INB)") (class "Default")
      (node (ref "IC33") (pin "6") (pinfunction "-INB_6") (pintype "bidirectional"))
      (node (ref "R107") (pin "1") (pinfunction "1_1") (pintype "passive"))
      (node (ref "R108") (pin "2") (pinfunction "2_2") (pintype "passive"))
    )
    (net (code "130") (name "Net-(IC38--INA)") (class "Default")
      (node (ref "IC38") (pin "1") (pinfunction "OUTA_1") (pintype "bidirectional"))
      (node (ref "IC38") (pin "2") (pinfunction "-INA_2") (pintype "bidirectional"))
      (node (ref "R119") (pin "1") (pinfunction "1_1") (pintype "passive"))
    )
    (net (code "131") (name "Net-(IC38--INB)") (class "Default")
      (node (ref "IC38") (pin "6") (pinfunction "-INB_6") (pintype "bidirectional"))
      (node (ref "IC38") (pin "7") (pinfunction "OUTB_7") (pintype "bidirectional"))
      (node (ref "R120") (pin "2") (pinfunction "2_2") (pintype "passive"))
    )
    (net (code "132") (name "Net-(J5-P$1)") (class "Default")
      (node (ref "J5") (pin "1") (pinfunction "P$1_1") (pintype "bidirectional"))
      (node (ref "R89") (pin "1") (pinfunction "1_1") (pintype "passive"))
    )
    (net (code "133") (name "Net-(J5-P$2)") (class "Default")
      (node (ref "J5") (pin "2") (pinfunction "P$2_2") (pintype "bidirectional"))
      (node (ref "R72") (pin "1") (pinfunction "1_1") (pintype "passive"))
    )
    (net (code "134") (name "Net-(J5-P$3)") (class "Default")
      (node (ref "J5") (pin "3") (pinfunction "P$3_3") (pintype "bidirectional"))
      (node (ref "R86") (pin "1") (pinfunction "1_1") (pintype "passive"))
    )
    (net (code "135") (name "Net-(J13-P$4)") (class "Default")
      (node (ref "J13") (pin "4") (pinfunction "P$4_4") (pintype "bidirectional"))
      (node (ref "R71") (pin "1") (pinfunction "1_1") (pintype "passive"))
    )
    (net (code "136") (name "Net-(OPOUT2-Pad1)") (class "Default")
      (node (ref "OPOUT2") (pin "1") (pinfunction "1_1") (pintype "passive"))
      (node (ref "R119") (pin "2") (pinfunction "2_2") (pintype "passive"))
    )
    (net (code "137") (name "Net-(PULSESOUT2-Pad1)") (class "Default")
      (node (ref "PULSESOUT2") (pin "1") (pinfunction "1_1") (pintype "passive"))
      (node (ref "R120") (pin "1") (pinfunction "1_1") (pintype "passive"))
    )
    (net (code "138") (name "Net-(R60-Pad1)") (class "Default")
      (node (ref "R60") (pin "1") (pinfunction "1_1") (pintype "passive"))
      (node (ref "R84") (pin "2") (pinfunction "2_2") (pintype "passive"))
    )
    (net (code "139") (name "Net-(R116-Pad1)") (class "Default")
      (node (ref "R116") (pin "1") (pinfunction "1_1") (pintype "passive"))
      (node (ref "R117") (pin "2") (pinfunction "2_2") (pintype "passive"))
    )
    (net (code "140") (name "OP1BUF") (class "Default")
      (node (ref "IC6") (pin "6") (pinfunction "OUTPUT_6") (pintype "bidirectional"))
      (node (ref "IC7") (pin "3") (pinfunction "NONINVERTING_INPUT_3") (pintype "bidirectional"))
      (node (ref "R18") (pin "2") (pinfunction "2_2") (pintype "passive"))
      (node (ref "R72") (pin "2") (pinfunction "2_2") (pintype "passive"))
    )
    (net (code "141") (name "OP2OUT") (class "Default")
      (node (ref "IC7") (pin "6") (pinfunction "OUTPUT_6") (pintype "bidirectional"))
      (node (ref "R6") (pin "2") (pinfunction "2_2") (pintype "passive"))
      (node (ref "R88") (pin "2") (pinfunction "2_2") (pintype "passive"))
    )
    (net (code "142") (name "OPOUT_H10") (class "Default")
      (node (ref "IC38") (pin "3") (pinfunction "+INA_3") (pintype "bidirectional"))
      (node (ref "J2") (pin "H10") (pinfunction "H10_H10") (pintype "bidirectional"))
      (node (ref "R10") (pin "2") (pinfunction "2_2") (pintype "passive"))
      (node (ref "R78") (pin "2") (pinfunction "2_2") (pintype "passive"))
      (node (ref "R86") (pin "2") (pinfunction "2_2") (pintype "passive"))
      (node (ref "R88") (pin "1") (pinfunction "1_1") (pintype "passive"))
      (node (ref "SV1") (pin "4") (pinfunction "4_4") (pintype "passive"))
    )
    (net (code "143") (name "OPOUT_H11") (class "Default")
      (node (ref "J2") (pin "H11") (pinfunction "H11_H11") (pintype "bidirectional"))
      (node (ref "R78") (pin "1") (pinfunction "1_1") (pintype "passive"))
      (node (ref "SV1") (pin "5") (pinfunction "5_5") (pintype "passive"))
    )
    (net (code "144") (name "PULSEOFFSETN") (class "Default")
      (node (ref "IC16") (pin "5") (pinfunction "VOUTC_5") (pintype "bidirectional"))
      (node (ref "R61") (pin "2") (pinfunction "2_2") (pintype "passive"))
    )
    (net (code "145") (name "PULSEOFFSETNI") (class "Default")
      (node (ref "IC10") (pin "1") (pinfunction "OUT_1") (pintype "output"))
      (node (ref "R35") (pin "2") (pinfunction "2_2") (pintype "passive"))
      (node (ref "R85") (pin "2") (pinfunction "2_2") (pintype "passive"))
    )
    (net (code "146") (name "PULSEOFFSETP") (class "Default")
      (node (ref "IC16") (pin "13") (pinfunction "VOUTB_13") (pintype "bidirectional"))
      (node (ref "R79") (pin "2") (pinfunction "2_2") (pintype "passive"))
    )
    (net (code "147") (name "PULSEOUT") (class "Default")
      (node (ref "PULSESOUT") (pin "1") (pinfunction "1_1") (pintype "passive"))
      (node (ref "R34") (pin "2") (pinfunction "2_2") (pintype "passive"))
      (node (ref "R9") (pin "2") (pinfunction "2_2") (pintype "passive"))
    )
    (net (code "148") (name "PULSEOUTN1") (class "Default")
      (node (ref "IC14") (pin "2") (pinfunction "1B_2") (pintype "bidirectional"))
      (node (ref "IC19") (pin "2") (pinfunction "1B_2") (pintype "bidirectional"))
      (node (ref "R12") (pin "2") (pinfunction "2_2") (pintype "passive"))
    )
    (net (code "149") (name "PULSEOUTN2") (class "Default")
      (node (ref "IC14") (pin "6") (pinfunction "2B_6") (pintype "bidirectional"))
      (node (ref "IC19") (pin "6") (pinfunction "2B_6") (pintype "bidirectional"))
      (node (ref "R38") (pin "2") (pinfunction "2_2") (pintype "passive"))
    )
    (net (code "150") (name "PULSEOUTN3") (class "Default")
      (node (ref "IC15") (pin "2") (pinfunction "1B_2") (pintype "bidirectional"))
      (node (ref "IC20") (pin "2") (pinfunction "1B_2") (pintype "bidirectional"))
      (node (ref "R32") (pin "2") (pinfunction "2_2") (pintype "passive"))
    )
    (net (code "151") (name "PULSEOUTN4") (class "Default")
      (node (ref "IC15") (pin "6") (pinfunction "2B_6") (pintype "bidirectional"))
      (node (ref "IC20") (pin "6") (pinfunction "2B_6") (pintype "bidirectional"))
      (node (ref "R40") (pin "2") (pinfunction "2_2") (pintype "passive"))
    )
    (net (code "152") (name "PULSEOUTN5") (class "Default")
      (node (ref "IC28") (pin "2") (pinfunction "1B_2") (pintype "bidirectional"))
      (node (ref "IC32") (pin "2") (pinfunction "1B_2") (pintype "bidirectional"))
      (node (ref "R112") (pin "2") (pinfunction "2_2") (pintype "passive"))
    )
    (net (code "153") (name "PULSEOUTN6") (class "Default")
      (node (ref "IC28") (pin "6") (pinfunction "2B_6") (pintype "bidirectional"))
      (node (ref "IC32") (pin "6") (pinfunction "2B_6") (pintype "bidirectional"))
      (node (ref "R114") (pin "2") (pinfunction "2_2") (pintype "passive"))
    )
    (net (code "154") (name "PULSEOUTP1") (class "Default")
      (node (ref "IC12") (pin "2") (pinfunction "1B_2") (pintype "bidirectional"))
      (node (ref "IC17") (pin "2") (pinfunction "1B_2") (pintype "bidirectional"))
      (node (ref "R7") (pin "2") (pinfunction "2_2") (pintype "passive"))
    )
    (net (code "155") (name "PULSEOUTP2") (class "Default")
      (node (ref "IC12") (pin "6") (pinfunction "2B_6") (pintype "bidirectional"))
      (node (ref "IC17") (pin "6") (pinfunction "2B_6") (pintype "bidirectional"))
      (node (ref "R33") (pin "2") (pinfunction "2_2") (pintype "passive"))
    )
    (net (code "156") (name "PULSEOUTP3") (class "Default")
      (node (ref "IC13") (pin "2") (pinfunction "1B_2") (pintype "bidirectional"))
      (node (ref "IC18") (pin "2") (pinfunction "1B_2") (pintype "bidirectional"))
      (node (ref "R8") (pin "2") (pinfunction "2_2") (pintype "passive"))
    )
    (net (code "157") (name "PULSEOUTP4") (class "Default")
      (node (ref "IC13") (pin "6") (pinfunction "2B_6") (pintype "bidirectional"))
      (node (ref "IC18") (pin "6") (pinfunction "2B_6") (pintype "bidirectional"))
      (node (ref "R36") (pin "2") (pinfunction "2_2") (pintype "passive"))
    )
    (net (code "158") (name "PULSEOUTP5") (class "Default")
      (node (ref "IC30") (pin "2") (pinfunction "1B_2") (pintype "bidirectional"))
      (node (ref "IC31") (pin "2") (pinfunction "1B_2") (pintype "bidirectional"))
      (node (ref "R111") (pin "2") (pinfunction "2_2") (pintype "passive"))
    )
    (net (code "159") (name "PULSEOUTP6") (class "Default")
      (node (ref "IC30") (pin "6") (pinfunction "2B_6") (pintype "bidirectional"))
      (node (ref "IC31") (pin "6") (pinfunction "2B_6") (pintype "bidirectional"))
      (node (ref "R113") (pin "2") (pinfunction "2_2") (pintype "passive"))
    )
    (net (code "160") (name "PULSESUMIN") (class "Default")
      (node (ref "IC4") (pin "2") (pinfunction "INVERTING_INPUT_2") (pintype "bidirectional"))
      (node (ref "R1") (pin "1") (pinfunction "1_1") (pintype "passive"))
      (node (ref "R111") (pin "1") (pinfunction "1_1") (pintype "passive"))
      (node (ref "R112") (pin "1") (pinfunction "1_1") (pintype "passive"))
      (node (ref "R113") (pin "1") (pinfunction "1_1") (pintype "passive"))
      (node (ref "R114") (pin "1") (pinfunction "1_1") (pintype "passive"))
      (node (ref "R12") (pin "1") (pinfunction "1_1") (pintype "passive"))
      (node (ref "R32") (pin "1") (pinfunction "1_1") (pintype "passive"))
      (node (ref "R33") (pin "1") (pinfunction "1_1") (pintype "passive"))
      (node (ref "R36") (pin "1") (pinfunction "1_1") (pintype "passive"))
      (node (ref "R38") (pin "1") (pinfunction "1_1") (pintype "passive"))
      (node (ref "R40") (pin "1") (pinfunction "1_1") (pintype "passive"))
      (node (ref "R7") (pin "1") (pinfunction "1_1") (pintype "passive"))
      (node (ref "R79") (pin "1") (pinfunction "1_1") (pintype "passive"))
      (node (ref "R8") (pin "1") (pinfunction "1_1") (pintype "passive"))
      (node (ref "R85") (pin "1") (pinfunction "1_1") (pintype "passive"))
    )
    (net (code "161") (name "PULSESUMOUT") (class "Default")
      (node (ref "IC38") (pin "5") (pinfunction "+INB_5") (pintype "bidirectional"))
      (node (ref "IC4") (pin "6") (pinfunction "OUTPUT_6") (pintype "bidirectional"))
      (node (ref "R1") (pin "2") (pinfunction "2_2") (pintype "passive"))
      (node (ref "R34") (pin "1") (pinfunction "1_1") (pintype "passive"))
      (node (ref "R71") (pin "2") (pinfunction "2_2") (pintype "passive"))
    )
    (net (code "162") (name "SCLIN") (class "Default")
      (node (ref "J2") (pin "H7") (pinfunction "H7_H7") (pintype "bidirectional"))
      (node (ref "J6") (pin "1") (pinfunction "P$1_1") (pintype "bidirectional"))
      (node (ref "R50") (pin "2") (pinfunction "2_2") (pintype "passive"))
      (node (ref "U$2") (pin "2") (pinfunction "S_2") (pintype "passive"))
    )
    (net (code "163") (name "SCLIN2") (class "Default")
      (node (ref "IC16") (pin "16") (pinfunction "SCL_16") (pintype "bidirectional"))
      (node (ref "IC2") (pin "16") (pinfunction "SCL_16") (pintype "bidirectional"))
      (node (ref "J6") (pin "3") (pinfunction "P$3_3") (pintype "bidirectional"))
      (node (ref "R51") (pin "2") (pinfunction "2_2") (pintype "passive"))
      (node (ref "U$2") (pin "3") (pinfunction "D_3") (pintype "passive"))
    )
    (net (code "164") (name "SDAIN") (class "Default")
      (node (ref "J2") (pin "H8") (pinfunction "H8_H8") (pintype "bidirectional"))
      (node (ref "J6") (pin "2") (pinfunction "P$2_2") (pintype "bidirectional"))
      (node (ref "R48") (pin "2") (pinfunction "2_2") (pintype "passive"))
      (node (ref "U$1") (pin "2") (pinfunction "S_2") (pintype "passive"))
    )
    (net (code "165") (name "SDAIN2") (class "Default")
      (node (ref "IC16") (pin "15") (pinfunction "SDA_15") (pintype "bidirectional"))
      (node (ref "IC2") (pin "15") (pinfunction "SDA_15") (pintype "bidirectional"))
      (node (ref "J6") (pin "4") (pinfunction "P$4_4") (pintype "bidirectional"))
      (node (ref "R49") (pin "2") (pinfunction "2_2") (pintype "passive"))
      (node (ref "U$1") (pin "3") (pinfunction "D_3") (pintype "passive"))
    )
    (net (code "166") (name "SW1") (class "Default")
      (node (ref "C122") (pin "2") (pinfunction "2_2") (pintype "bidirectional"))
      (node (ref "D1") (pin "C") (pinfunction "C_C") (pintype "passive"))
      (node (ref "IC37") (pin "8") (pinfunction "PH_8") (pintype "bidirectional"))
      (node (ref "L3") (pin "1") (pinfunction "1_1") (pintype "passive"))
    )
    (net (code "167") (name "SW2") (class "Default")
      (node (ref "C107") (pin "2") (pinfunction "2_2") (pintype "bidirectional"))
      (node (ref "D2") (pin "C") (pinfunction "C_C") (pintype "passive"))
      (node (ref "IC36") (pin "8") (pinfunction "PH_8") (pintype "bidirectional"))
      (node (ref "L4") (pin "1") (pinfunction "1_1") (pintype "passive"))
    )
    (net (code "168") (name "TRANSIN") (class "Default")
      (node (ref "IC1") (pin "2") (pinfunction "INVERTING_INPUT_2") (pintype "bidirectional"))
      (node (ref "R11") (pin "2") (pinfunction "2_2") (pintype "passive"))
      (node (ref "R2") (pin "1") (pinfunction "1_1") (pintype "passive"))
    )
    (net (code "169") (name "TRANSOUT") (class "Default")
      (node (ref "IC1") (pin "6") (pinfunction "OUTPUT_6") (pintype "bidirectional"))
      (node (ref "R11") (pin "1") (pinfunction "1_1") (pintype "passive"))
      (node (ref "R20") (pin "2") (pinfunction "2_2") (pintype "passive"))
      (node (ref "R89") (pin "2") (pinfunction "2_2") (pintype "passive"))
    )
    (net (code "170") (name "VIN+") (class "Default")
      (node (ref "C1") (pin "1") (pinfunction "1_1") (pintype "passive"))
      (node (ref "C121") (pin "1") (pinfunction "1_1") (pintype "bidirectional"))
      (node (ref "C2") (pin "+") (pinfunction "+_+") (pintype "passive"))
      (node (ref "C42") (pin "1") (pinfunction "1_1") (pintype "bidirectional"))
      (node (ref "J1") (pin "1") (pinfunction "P$1_1") (pintype "bidirectional"))
      (node (ref "L1") (pin "1") (pinfunction "1_1") (pintype "passive"))
      (node (ref "L3") (pin "2") (pinfunction "2_2") (pintype "passive"))
      (node (ref "R73") (pin "2") (pinfunction "2_2") (pintype "passive"))
    )
    (net (code "171") (name "VIN+CLEAN") (class "Default")
      (node (ref "C110") (pin "1") (pinfunction "1_1") (pintype "passive"))
      (node (ref "C43") (pin "1") (pinfunction "1_1") (pintype "bidirectional"))
      (node (ref "IC11") (pin "1") (pinfunction "VI_1") (pintype "input"))
      (node (ref "L1") (pin "2") (pinfunction "2_2") (pintype "passive"))
    )
    (net (code "172") (name "VIN-") (class "Default")
      (node (ref "C106") (pin "2") (pinfunction "2_2") (pintype "bidirectional"))
      (node (ref "C109") (pin "2") (pinfunction "2_2") (pintype "passive"))
      (node (ref "C113") (pin "2") (pinfunction "2_2") (pintype "passive"))
      (node (ref "C40") (pin "-") (pinfunction "-_-") (pintype "passive"))
      (node (ref "C41") (pin "2") (pinfunction "2_2") (pintype "passive"))
      (node (ref "C44") (pin "2") (pinfunction "2_2") (pintype "bidirectional"))
      (node (ref "D2") (pin "A") (pinfunction "A_A") (pintype "passive"))
      (node (ref "IC36") (pin "6") (pinfunction "GND_6") (pintype "bidirectional"))
      (node (ref "IC36") (pin "9") (pinfunction "EP_9") (pintype "bidirectional"))
      (node (ref "J1") (pin "3") (pinfunction "P$3_3") (pintype "bidirectional"))
      (node (ref "L2") (pin "1") (pinfunction "1_1") (pintype "passive"))
      (node (ref "R117") (pin "1") (pinfunction "1_1") (pintype "passive"))
    )
    (net (code "173") (name "VIN-CLEAN") (class "Default")
      (node (ref "C111") (pin "2") (pinfunction "2_2") (pintype "passive"))
      (node (ref "C45") (pin "2") (pinfunction "2_2") (pintype "bidirectional"))
      (node (ref "IC25") (pin "2") (pinfunction "INPUT_2") (pintype "bidirectional"))
      (node (ref "L2") (pin "2") (pinfunction "2_2") (pintype "passive"))
    )
    (net (code "174") (name "VS+") (class "Default")
      (node (ref "C114") (pin "1") (pinfunction "1_1") (pintype "bidirectional"))
      (node (ref "C116") (pin "1") (pinfunction "1_1") (pintype "bidirectional"))
      (node (ref "C16") (pin "1") (pinfunction "1_1") (pintype "bidirectional"))
      (node (ref "C22") (pin "1") (pinfunction "1_1") (pintype "bidirectional"))
      (node (ref "C24") (pin "1") (pinfunction "1_1") (pintype "bidirectional"))
      (node (ref "C26") (pin "1") (pinfunction "1_1") (pintype "bidirectional"))
      (node (ref "C28") (pin "1") (pinfunction "1_1") (pintype "bidirectional"))
      (node (ref "C3") (pin "1") (pinfunction "1_1") (pintype "bidirectional"))
      (node (ref "C32") (pin "1") (pinfunction "1_1") (pintype "bidirectional"))
      (node (ref "C37") (pin "1") (pinfunction "1_1") (pintype "bidirectional"))
      (node (ref "C38") (pin "1") (pinfunction "1_1") (pintype "passive"))
      (node (ref "C4") (pin "1") (pinfunction "1_1") (pintype "bidirectional"))
      (node (ref "C47") (pin "1") (pinfunction "1_1") (pintype "bidirectional"))
      (node (ref "C48") (pin "1") (pinfunction "1_1") (pintype "bidirectional"))
      (node (ref "C54") (pin "1") (pinfunction "1_1") (pintype "bidirectional"))
      (node (ref "C6") (pin "1") (pinfunction "1_1") (pintype "bidirectional"))
      (node (ref "C65") (pin "1") (pinfunction "1_1") (pintype "bidirectional"))
      (node (ref "C73") (pin "1") (pinfunction "1_1") (pintype "bidirectional"))
      (node (ref "C75") (pin "1") (pinfunction "1_1") (pintype "bidirectional"))
      (node (ref "C78") (pin "1") (pinfunction "1_1") (pintype "bidirectional"))
      (node (ref "C82") (pin "1") (pinfunction "1_1") (pintype "bidirectional"))
      (node (ref "C84") (pin "1") (pinfunction "1_1") (pintype "bidirectional"))
      (node (ref "C87") (pin "1") (pinfunction "1_1") (pintype "bidirectional"))
      (node (ref "C9") (pin "1") (pinfunction "1_1") (pintype "bidirectional"))
      (node (ref "C91") (pin "1") (pinfunction "1_1") (pintype "bidirectional"))
      (node (ref "C93") (pin "1") (pinfunction "1_1") (pintype "bidirectional"))
      (node (ref "C97") (pin "1") (pinfunction "1_1") (pintype "bidirectional"))
      (node (ref "IC1") (pin "7") (pinfunction "+VS_7") (pintype "bidirectional"))
      (node (ref "IC10") (pin "8") (pinfunction "P$V+_8") (pintype "bidirectional"))
      (node (ref "IC11") (pin "2") (pinfunction "VO_2") (pintype "passive"))
      (node (ref "IC16") (pin "3") (pinfunction "AVDD_3") (pintype "bidirectional"))
      (node (ref "IC2") (pin "3") (pinfunction "AVDD_3") (pintype "bidirectional"))
      (node (ref "IC26") (pin "3") (pinfunction "VIN_3") (pintype "input"))
      (node (ref "IC27") (pin "8") (pinfunction "P$V+_8") (pintype "bidirectional"))
      (node (ref "IC3") (pin "8") (pinfunction "V+_8") (pintype "bidirectional"))
      (node (ref "IC33") (pin "8") (pinfunction "V+_8") (pintype "bidirectional"))
      (node (ref "IC38") (pin "8") (pinfunction "V+_8") (pintype "bidirectional"))
      (node (ref "IC4") (pin "7") (pinfunction "+VS_7") (pintype "bidirectional"))
      (node (ref "IC5") (pin "8") (pinfunction "V+_8") (pintype "bidirectional"))
      (node (ref "IC6") (pin "7") (pinfunction "+VS_7") (pintype "bidirectional"))
      (node (ref "IC7") (pin "7") (pinfunction "+VS_7") (pintype "bidirectional"))
      (node (ref "IC8") (pin "8") (pinfunction "P$V+_8") (pintype "bidirectional"))
      (node (ref "IC9") (pin "8") (pinfunction "P$V+_8") (pintype "bidirectional"))
      (node (ref "J3") (pin "2") (pinfunction "2_2") (pintype "bidirectional"))
      (node (ref "R49") (pin "1") (pinfunction "1_1") (pintype "passive"))
      (node (ref "R51") (pin "1") (pinfunction "1_1") (pintype "passive"))
    )
    (net (code "175") (name "VS-") (class "Default")
      (node (ref "C10") (pin "1") (pinfunction "1_1") (pintype "bidirectional"))
      (node (ref "C115") (pin "1") (pinfunction "1_1") (pintype "bidirectional"))
      (node (ref "C15") (pin "1") (pinfunction "1_1") (pintype "bidirectional"))
      (node (ref "C21") (pin "1") (pinfunction "1_1") (pintype "bidirectional"))
      (node (ref "C25") (pin "1") (pinfunction "1_1") (pintype "bidirectional"))
      (node (ref "C27") (pin "1") (pinfunction "1_1") (pintype "bidirectional"))
      (node (ref "C29") (pin "1") (pinfunction "1_1") (pintype "bidirectional"))
      (node (ref "C33") (pin "1") (pinfunction "1_1") (pintype "bidirectional"))
      (node (ref "C39") (pin "2") (pinfunction "2_2") (pintype "passive"))
      (node (ref "C46") (pin "2") (pinfunction "2_2") (pintype "bidirectional"))
      (node (ref "C76") (pin "1") (pinfunction "1_1") (pintype "bidirectional"))
      (node (ref "C77") (pin "1") (pinfunction "1_1") (pintype "passive"))
      (node (ref "C79") (pin "1") (pinfunction "1_1") (pintype "bidirectional"))
      (node (ref "C81") (pin "1") (pinfunction "1_1") (pintype "bidirectional"))
      (node (ref "C83") (pin "1") (pinfunction "1_1") (pintype "bidirectional"))
      (node (ref "C85") (pin "1") (pinfunction "1_1") (pintype "bidirectional"))
      (node (ref "C86") (pin "1") (pinfunction "1_1") (pintype "bidirectional"))
      (node (ref "C88") (pin "1") (pinfunction "1_1") (pintype "bidirectional"))
      (node (ref "C98") (pin "1") (pinfunction "1_1") (pintype "bidirectional"))
      (node (ref "IC1") (pin "4") (pinfunction "-VS_4") (pintype "bidirectional"))
      (node (ref "IC10") (pin "4") (pinfunction "P$V-_4") (pintype "bidirectional"))
      (node (ref "IC25") (pin "3") (pinfunction "OUTPUT_3") (pintype "bidirectional"))
      (node (ref "IC27") (pin "4") (pinfunction "P$V-_4") (pintype "bidirectional"))
      (node (ref "IC29") (pin "2") (pinfunction "INPUT_2") (pintype "bidirectional"))
      (node (ref "IC38") (pin "4") (pinfunction "V-_1_4") (pintype "bidirectional"))
      (node (ref "IC38") (pin "9") (pinfunction "V-_2_9") (pintype "bidirectional"))
      (node (ref "IC4") (pin "4") (pinfunction "-VS_4") (pintype "bidirectional"))
      (node (ref "IC6") (pin "4") (pinfunction "-VS_4") (pintype "bidirectional"))
      (node (ref "IC7") (pin "4") (pinfunction "-VS_4") (pintype "bidirectional"))
      (node (ref "IC8") (pin "4") (pinfunction "P$V-_4") (pintype "bidirectional"))
      (node (ref "IC9") (pin "4") (pinfunction "P$V-_4") (pintype "bidirectional"))
      (node (ref "J3") (pin "3") (pinfunction "3_3") (pintype "bidirectional"))
    )
    (net (code "176") (name "unconnected-(IC1-NC-Pad1)") (class "Default")
      (node (ref "IC1") (pin "1") (pinfunction "NC_1") (pintype "no_connect"))
    )
    (net (code "177") (name "unconnected-(IC1-VH-Pad8)") (class "Default")
      (node (ref "IC1") (pin "8") (pinfunction "VH_8") (pintype "bidirectional"))
    )
    (net (code "178") (name "unconnected-(IC1-VL-Pad5)") (class "Default")
      (node (ref "IC1") (pin "5") (pinfunction "VL_5") (pintype "bidirectional"))
    )
    (net (code "179") (name "unconnected-(IC4-NC_1-Pad1)") (class "Default")
      (node (ref "IC4") (pin "1") (pinfunction "NC_1_1") (pintype "bidirectional"))
    )
    (net (code "180") (name "unconnected-(IC4-NC_2-Pad5)") (class "Default")
      (node (ref "IC4") (pin "5") (pinfunction "NC_2_5") (pintype "bidirectional"))
    )
    (net (code "181") (name "unconnected-(IC4-~{DIS}-Pad8)") (class "Default")
      (node (ref "IC4") (pin "8") (pinfunction "~{DIS}_8") (pintype "bidirectional"))
    )
    (net (code "182") (name "unconnected-(IC6-NC_1-Pad1)") (class "Default")
      (node (ref "IC6") (pin "1") (pinfunction "NC_1_1") (pintype "bidirectional"))
    )
    (net (code "183") (name "unconnected-(IC6-NC_2-Pad5)") (class "Default")
      (node (ref "IC6") (pin "5") (pinfunction "NC_2_5") (pintype "bidirectional"))
    )
    (net (code "184") (name "unconnected-(IC6-~{DIS}-Pad8)") (class "Default")
      (node (ref "IC6") (pin "8") (pinfunction "~{DIS}_8") (pintype "bidirectional"))
    )
    (net (code "185") (name "unconnected-(IC7-NC-Pad1)") (class "Default")
      (node (ref "IC7") (pin "1") (pinfunction "NC_1") (pintype "no_connect"))
    )
    (net (code "186") (name "unconnected-(IC36-ENA-Pad5)") (class "Default")
      (node (ref "IC36") (pin "5") (pinfunction "ENA_5") (pintype "bidirectional"))
    )
    (net (code "187") (name "unconnected-(IC36-NC_1-Pad2)") (class "Default")
      (node (ref "IC36") (pin "2") (pinfunction "NC_1_2") (pintype "bidirectional"))
    )
    (net (code "188") (name "unconnected-(IC36-NC_2-Pad3)") (class "Default")
      (node (ref "IC36") (pin "3") (pinfunction "NC_2_3") (pintype "bidirectional"))
    )
    (net (code "189") (name "unconnected-(IC37-ENA-Pad5)") (class "Default")
      (node (ref "IC37") (pin "5") (pinfunction "ENA_5") (pintype "bidirectional"))
    )
    (net (code "190") (name "unconnected-(IC37-NC_1-Pad2)") (class "Default")
      (node (ref "IC37") (pin "2") (pinfunction "NC_1_2") (pintype "bidirectional"))
    )
    (net (code "191") (name "unconnected-(IC37-NC_2-Pad3)") (class "Default")
      (node (ref "IC37") (pin "3") (pinfunction "NC_2_3") (pintype "bidirectional"))
    )
    (net (code "192") (name "unconnected-(J2-PadC2)") (class "Default")
      (node (ref "J2") (pin "C2") (pinfunction "C2_C2") (pintype "bidirectional"))
    )
    (net (code "193") (name "unconnected-(J2-PadC3)") (class "Default")
      (node (ref "J2") (pin "C3") (pinfunction "C3_C3") (pintype "bidirectional"))
    )
    (net (code "194") (name "unconnected-(J2-PadC6)") (class "Default")
      (node (ref "J2") (pin "C6") (pinfunction "C6_C6") (pintype "bidirectional"))
    )
    (net (code "195") (name "unconnected-(J2-PadC7)") (class "Default")
      (node (ref "J2") (pin "C7") (pinfunction "C7_C7") (pintype "bidirectional"))
    )
    (net (code "196") (name "unconnected-(J2-PadC30)") (class "Default")
      (node (ref "J2") (pin "C30") (pinfunction "C30_C30") (pintype "bidirectional"))
    )
    (net (code "197") (name "unconnected-(J2-PadC31)") (class "Default")
      (node (ref "J2") (pin "C31") (pinfunction "C31_C31") (pintype "bidirectional"))
    )
    (net (code "198") (name "unconnected-(J2-PadC34)") (class "Default")
      (node (ref "J2") (pin "C34") (pinfunction "C34_C34") (pintype "bidirectional"))
    )
    (net (code "199") (name "unconnected-(J2-PadD1)") (class "Default")
      (node (ref "J2") (pin "D1") (pinfunction "D1_D1") (pintype "bidirectional"))
    )
    (net (code "200") (name "unconnected-(J2-PadD4)") (class "Default")
      (node (ref "J2") (pin "D4") (pinfunction "D4_D4") (pintype "bidirectional"))
    )
    (net (code "201") (name "unconnected-(J2-PadD5)") (class "Default")
      (node (ref "J2") (pin "D5") (pinfunction "D5_D5") (pintype "bidirectional"))
    )
    (net (code "202") (name "unconnected-(J2-PadD8)") (class "Default")
      (node (ref "J2") (pin "D8") (pinfunction "D8_D8") (pintype "bidirectional"))
    )
    (net (code "203") (name "unconnected-(J2-PadD9)") (class "Default")
      (node (ref "J2") (pin "D9") (pinfunction "D9_D9") (pintype "bidirectional"))
    )
    (net (code "204") (name "unconnected-(J2-PadD10)") (class "Default")
      (node (ref "J2") (pin "D10") (pinfunction "D10_D10") (pintype "bidirectional"))
    )
    (net (code "205") (name "unconnected-(J2-PadD11)") (class "Default")
      (node (ref "J2") (pin "D11") (pinfunction "D11_D11") (pintype "bidirectional"))
    )
    (net (code "206") (name "unconnected-(J2-PadD12)") (class "Default")
      (node (ref "J2") (pin "D12") (pinfunction "D12_D12") (pintype "bidirectional"))
    )
    (net (code "207") (name "unconnected-(J2-PadD13)") (class "Default")
      (node (ref "J2") (pin "D13") (pinfunction "D13_D13") (pintype "bidirectional"))
    )
    (net (code "208") (name "unconnected-(J2-PadD14)") (class "Default")
      (node (ref "J2") (pin "D14") (pinfunction "D14_D14") (pintype "bidirectional"))
    )
    (net (code "209") (name "unconnected-(J2-PadD15)") (class "Default")
      (node (ref "J2") (pin "D15") (pinfunction "D15_D15") (pintype "bidirectional"))
    )
    (net (code "210") (name "unconnected-(J2-PadD16)") (class "Default")
      (node (ref "J2") (pin "D16") (pinfunction "D16_D16") (pintype "bidirectional"))
    )
    (net (code "211") (name "unconnected-(J2-PadD17)") (class "Default")
      (node (ref "J2") (pin "D17") (pinfunction "D17_D17") (pintype "bidirectional"))
    )
    (net (code "212") (name "unconnected-(J2-PadD18)") (class "Default")
      (node (ref "J2") (pin "D18") (pinfunction "D18_D18") (pintype "bidirectional"))
    )
    (net (code "213") (name "unconnected-(J2-PadD19)") (class "Default")
      (node (ref "J2") (pin "D19") (pinfunction "D19_D19") (pintype "bidirectional"))
    )
    (net (code "214") (name "unconnected-(J2-PadD20)") (class "Default")
      (node (ref "J2") (pin "D20") (pinfunction "D20_D20") (pintype "bidirectional"))
    )
    (net (code "215") (name "unconnected-(J2-PadD21)") (class "Default")
      (node (ref "J2") (pin "D21") (pinfunction "D21_D21") (pintype "bidirectional"))
    )
    (net (code "216") (name "unconnected-(J2-PadD22)") (class "Default")
      (node (ref "J2") (pin "D22") (pinfunction "D22_D22") (pintype "bidirectional"))
    )
    (net (code "217") (name "unconnected-(J2-PadD23)") (class "Default")
      (node (ref "J2") (pin "D23") (pinfunction "D23_D23") (pintype "bidirectional"))
    )
    (net (code "218") (name "unconnected-(J2-PadD24)") (class "Default")
      (node (ref "J2") (pin "D24") (pinfunction "D24_D24") (pintype "bidirectional"))
    )
    (net (code "219") (name "unconnected-(J2-PadD25)") (class "Default")
      (node (ref "J2") (pin "D25") (pinfunction "D25_D25") (pintype "bidirectional"))
    )
    (net (code "220") (name "unconnected-(J2-PadD26)") (class "Default")
      (node (ref "J2") (pin "D26") (pinfunction "D26_D26") (pintype "bidirectional"))
    )
    (net (code "221") (name "unconnected-(J2-PadD27)") (class "Default")
      (node (ref "J2") (pin "D27") (pinfunction "D27_D27") (pintype "bidirectional"))
    )
    (net (code "222") (name "unconnected-(J2-PadD28)") (class "Default")
      (node (ref "J2") (pin "D28") (pinfunction "D28_D28") (pintype "bidirectional"))
    )
    (net (code "223") (name "unconnected-(J2-PadD29)") (class "Default")
      (node (ref "J2") (pin "D29") (pinfunction "D29_D29") (pintype "bidirectional"))
    )
    (net (code "224") (name "unconnected-(J2-PadD30)") (class "Default")
      (node (ref "J2") (pin "D30") (pinfunction "D30_D30") (pintype "bidirectional"))
    )
    (net (code "225") (name "unconnected-(J2-PadD31)") (class "Default")
      (node (ref "J2") (pin "D31") (pinfunction "D31_D31") (pintype "bidirectional"))
    )
    (net (code "226") (name "unconnected-(J2-PadD32)") (class "Default")
      (node (ref "J2") (pin "D32") (pinfunction "D32_D32") (pintype "bidirectional"))
    )
    (net (code "227") (name "unconnected-(J2-PadD33)") (class "Default")
      (node (ref "J2") (pin "D33") (pinfunction "D33_D33") (pintype "bidirectional"))
    )
    (net (code "228") (name "unconnected-(J2-PadD34)") (class "Default")
      (node (ref "J2") (pin "D34") (pinfunction "D34_D34") (pintype "bidirectional"))
    )
    (net (code "229") (name "unconnected-(J2-PadD35)") (class "Default")
      (node (ref "J2") (pin "D35") (pinfunction "D35_D35") (pintype "bidirectional"))
    )
    (net (code "230") (name "unconnected-(J2-PadG1)") (class "Default")
      (node (ref "J2") (pin "G1") (pinfunction "G1_G1") (pintype "bidirectional"))
    )
    (net (code "231") (name "unconnected-(J2-PadG2)") (class "Default")
      (node (ref "J2") (pin "G2") (pinfunction "G2_G2") (pintype "bidirectional"))
    )
    (net (code "232") (name "unconnected-(J2-PadG3)") (class "Default")
      (node (ref "J2") (pin "G3") (pinfunction "G3_G3") (pintype "bidirectional"))
    )
    (net (code "233") (name "unconnected-(J2-PadG4)") (class "Default")
      (node (ref "J2") (pin "G4") (pinfunction "G4_G4") (pintype "bidirectional"))
    )
    (net (code "234") (name "unconnected-(J2-PadG5)") (class "Default")
      (node (ref "J2") (pin "G5") (pinfunction "G5_G5") (pintype "bidirectional"))
    )
    (net (code "235") (name "unconnected-(J2-PadG6)") (class "Default")
      (node (ref "J2") (pin "G6") (pinfunction "G6_G6") (pintype "bidirectional"))
    )
    (net (code "236") (name "unconnected-(J2-PadG7)") (class "Default")
      (node (ref "J2") (pin "G7") (pinfunction "G7_G7") (pintype "bidirectional"))
    )
    (net (code "237") (name "unconnected-(J2-PadG8)") (class "Default")
      (node (ref "J2") (pin "G8") (pinfunction "G8_G8") (pintype "bidirectional"))
    )
    (net (code "238") (name "unconnected-(J2-PadG9)") (class "Default")
      (node (ref "J2") (pin "G9") (pinfunction "G9_G9") (pintype "bidirectional"))
    )
    (net (code "239") (name "unconnected-(J2-PadG10)") (class "Default")
      (node (ref "J2") (pin "G10") (pinfunction "G10_G10") (pintype "bidirectional"))
    )
    (net (code "240") (name "unconnected-(J2-PadG11)") (class "Default")
      (node (ref "J2") (pin "G11") (pinfunction "G11_G11") (pintype "bidirectional"))
    )
    (net (code "241") (name "unconnected-(J2-PadG12)") (class "Default")
      (node (ref "J2") (pin "G12") (pinfunction "G12_G12") (pintype "bidirectional"))
    )
    (net (code "242") (name "unconnected-(J2-PadG13)") (class "Default")
      (node (ref "J2") (pin "G13") (pinfunction "G13_G13") (pintype "bidirectional"))
    )
    (net (code "243") (name "unconnected-(J2-PadG14)") (class "Default")
      (node (ref "J2") (pin "G14") (pinfunction "G14_G14") (pintype "bidirectional"))
    )
    (net (code "244") (name "unconnected-(J2-PadG15)") (class "Default")
      (node (ref "J2") (pin "G15") (pinfunction "G15_G15") (pintype "bidirectional"))
    )
    (net (code "245") (name "unconnected-(J2-PadG16)") (class "Default")
      (node (ref "J2") (pin "G16") (pinfunction "G16_G16") (pintype "bidirectional"))
    )
    (net (code "246") (name "unconnected-(J2-PadG17)") (class "Default")
      (node (ref "J2") (pin "G17") (pinfunction "G17_G17") (pintype "bidirectional"))
    )
    (net (code "247") (name "unconnected-(J2-PadG18)") (class "Default")
      (node (ref "J2") (pin "G18") (pinfunction "G18_G18") (pintype "bidirectional"))
    )
    (net (code "248") (name "unconnected-(J2-PadG19)") (class "Default")
      (node (ref "J2") (pin "G19") (pinfunction "G19_G19") (pintype "bidirectional"))
    )
    (net (code "249") (name "unconnected-(J2-PadG20)") (class "Default")
      (node (ref "J2") (pin "G20") (pinfunction "G20_G20") (pintype "bidirectional"))
    )
    (net (code "250") (name "unconnected-(J2-PadG21)") (class "Default")
      (node (ref "J2") (pin "G21") (pinfunction "G21_G21") (pintype "bidirectional"))
    )
    (net (code "251") (name "unconnected-(J2-PadG22)") (class "Default")
      (node (ref "J2") (pin "G22") (pinfunction "G22_G22") (pintype "bidirectional"))
    )
    (net (code "252") (name "unconnected-(J2-PadG23)") (class "Default")
      (node (ref "J2") (pin "G23") (pinfunction "G23_G23") (pintype "bidirectional"))
    )
    (net (code "253") (name "unconnected-(J2-PadG24)") (class "Default")
      (node (ref "J2") (pin "G24") (pinfunction "G24_G24") (pintype "bidirectional"))
    )
    (net (code "254") (name "unconnected-(J2-PadG25)") (class "Default")
      (node (ref "J2") (pin "G25") (pinfunction "G25_G25") (pintype "bidirectional"))
    )
    (net (code "255") (name "unconnected-(J2-PadG26)") (class "Default")
      (node (ref "J2") (pin "G26") (pinfunction "G26_G26") (pintype "bidirectional"))
    )
    (net (code "256") (name "unconnected-(J2-PadG27)") (class "Default")
      (node (ref "J2") (pin "G27") (pinfunction "G27_G27") (pintype "bidirectional"))
    )
    (net (code "257") (name "unconnected-(J2-PadG28)") (class "Default")
      (node (ref "J2") (pin "G28") (pinfunction "G28_G28") (pintype "bidirectional"))
    )
    (net (code "258") (name "unconnected-(J2-PadG29)") (class "Default")
      (node (ref "J2") (pin "G29") (pinfunction "G29_G29") (pintype "bidirectional"))
    )
    (net (code "259") (name "unconnected-(J2-PadG30)") (class "Default")
      (node (ref "J2") (pin "G30") (pinfunction "G30_G30") (pintype "bidirectional"))
    )
    (net (code "260") (name "unconnected-(J2-PadG31)") (class "Default")
      (node (ref "J2") (pin "G31") (pinfunction "G31_G31") (pintype "bidirectional"))
    )
    (net (code "261") (name "unconnected-(J2-PadG32)") (class "Default")
      (node (ref "J2") (pin "G32") (pinfunction "G32_G32") (pintype "bidirectional"))
    )
    (net (code "262") (name "unconnected-(J2-PadG33)") (class "Default")
      (node (ref "J2") (pin "G33") (pinfunction "G33_G33") (pintype "bidirectional"))
    )
    (net (code "263") (name "unconnected-(J2-PadG34)") (class "Default")
      (node (ref "J2") (pin "G34") (pinfunction "G34_G34") (pintype "bidirectional"))
    )
    (net (code "264") (name "unconnected-(J2-PadG35)") (class "Default")
      (node (ref "J2") (pin "G35") (pinfunction "G35_G35") (pintype "bidirectional"))
    )
    (net (code "265") (name "unconnected-(J2-PadG36)") (class "Default")
      (node (ref "J2") (pin "G36") (pinfunction "G36_G36") (pintype "bidirectional"))
    )
    (net (code "266") (name "unconnected-(J2-PadG37)") (class "Default")
      (node (ref "J2") (pin "G37") (pinfunction "G37_G37") (pintype "bidirectional"))
    )
    (net (code "267") (name "unconnected-(J2-PadH1)") (class "Default")
      (node (ref "J2") (pin "H1") (pinfunction "H1_H1") (pintype "bidirectional"))
    )
    (net (code "268") (name "unconnected-(J2-PadH2)") (class "Default")
      (node (ref "J2") (pin "H2") (pinfunction "H2_H2") (pintype "bidirectional"))
    )
  )
)
